# SPU_Rev_2_0.net
KiCad netlist of a schematic drawn in EAGLE
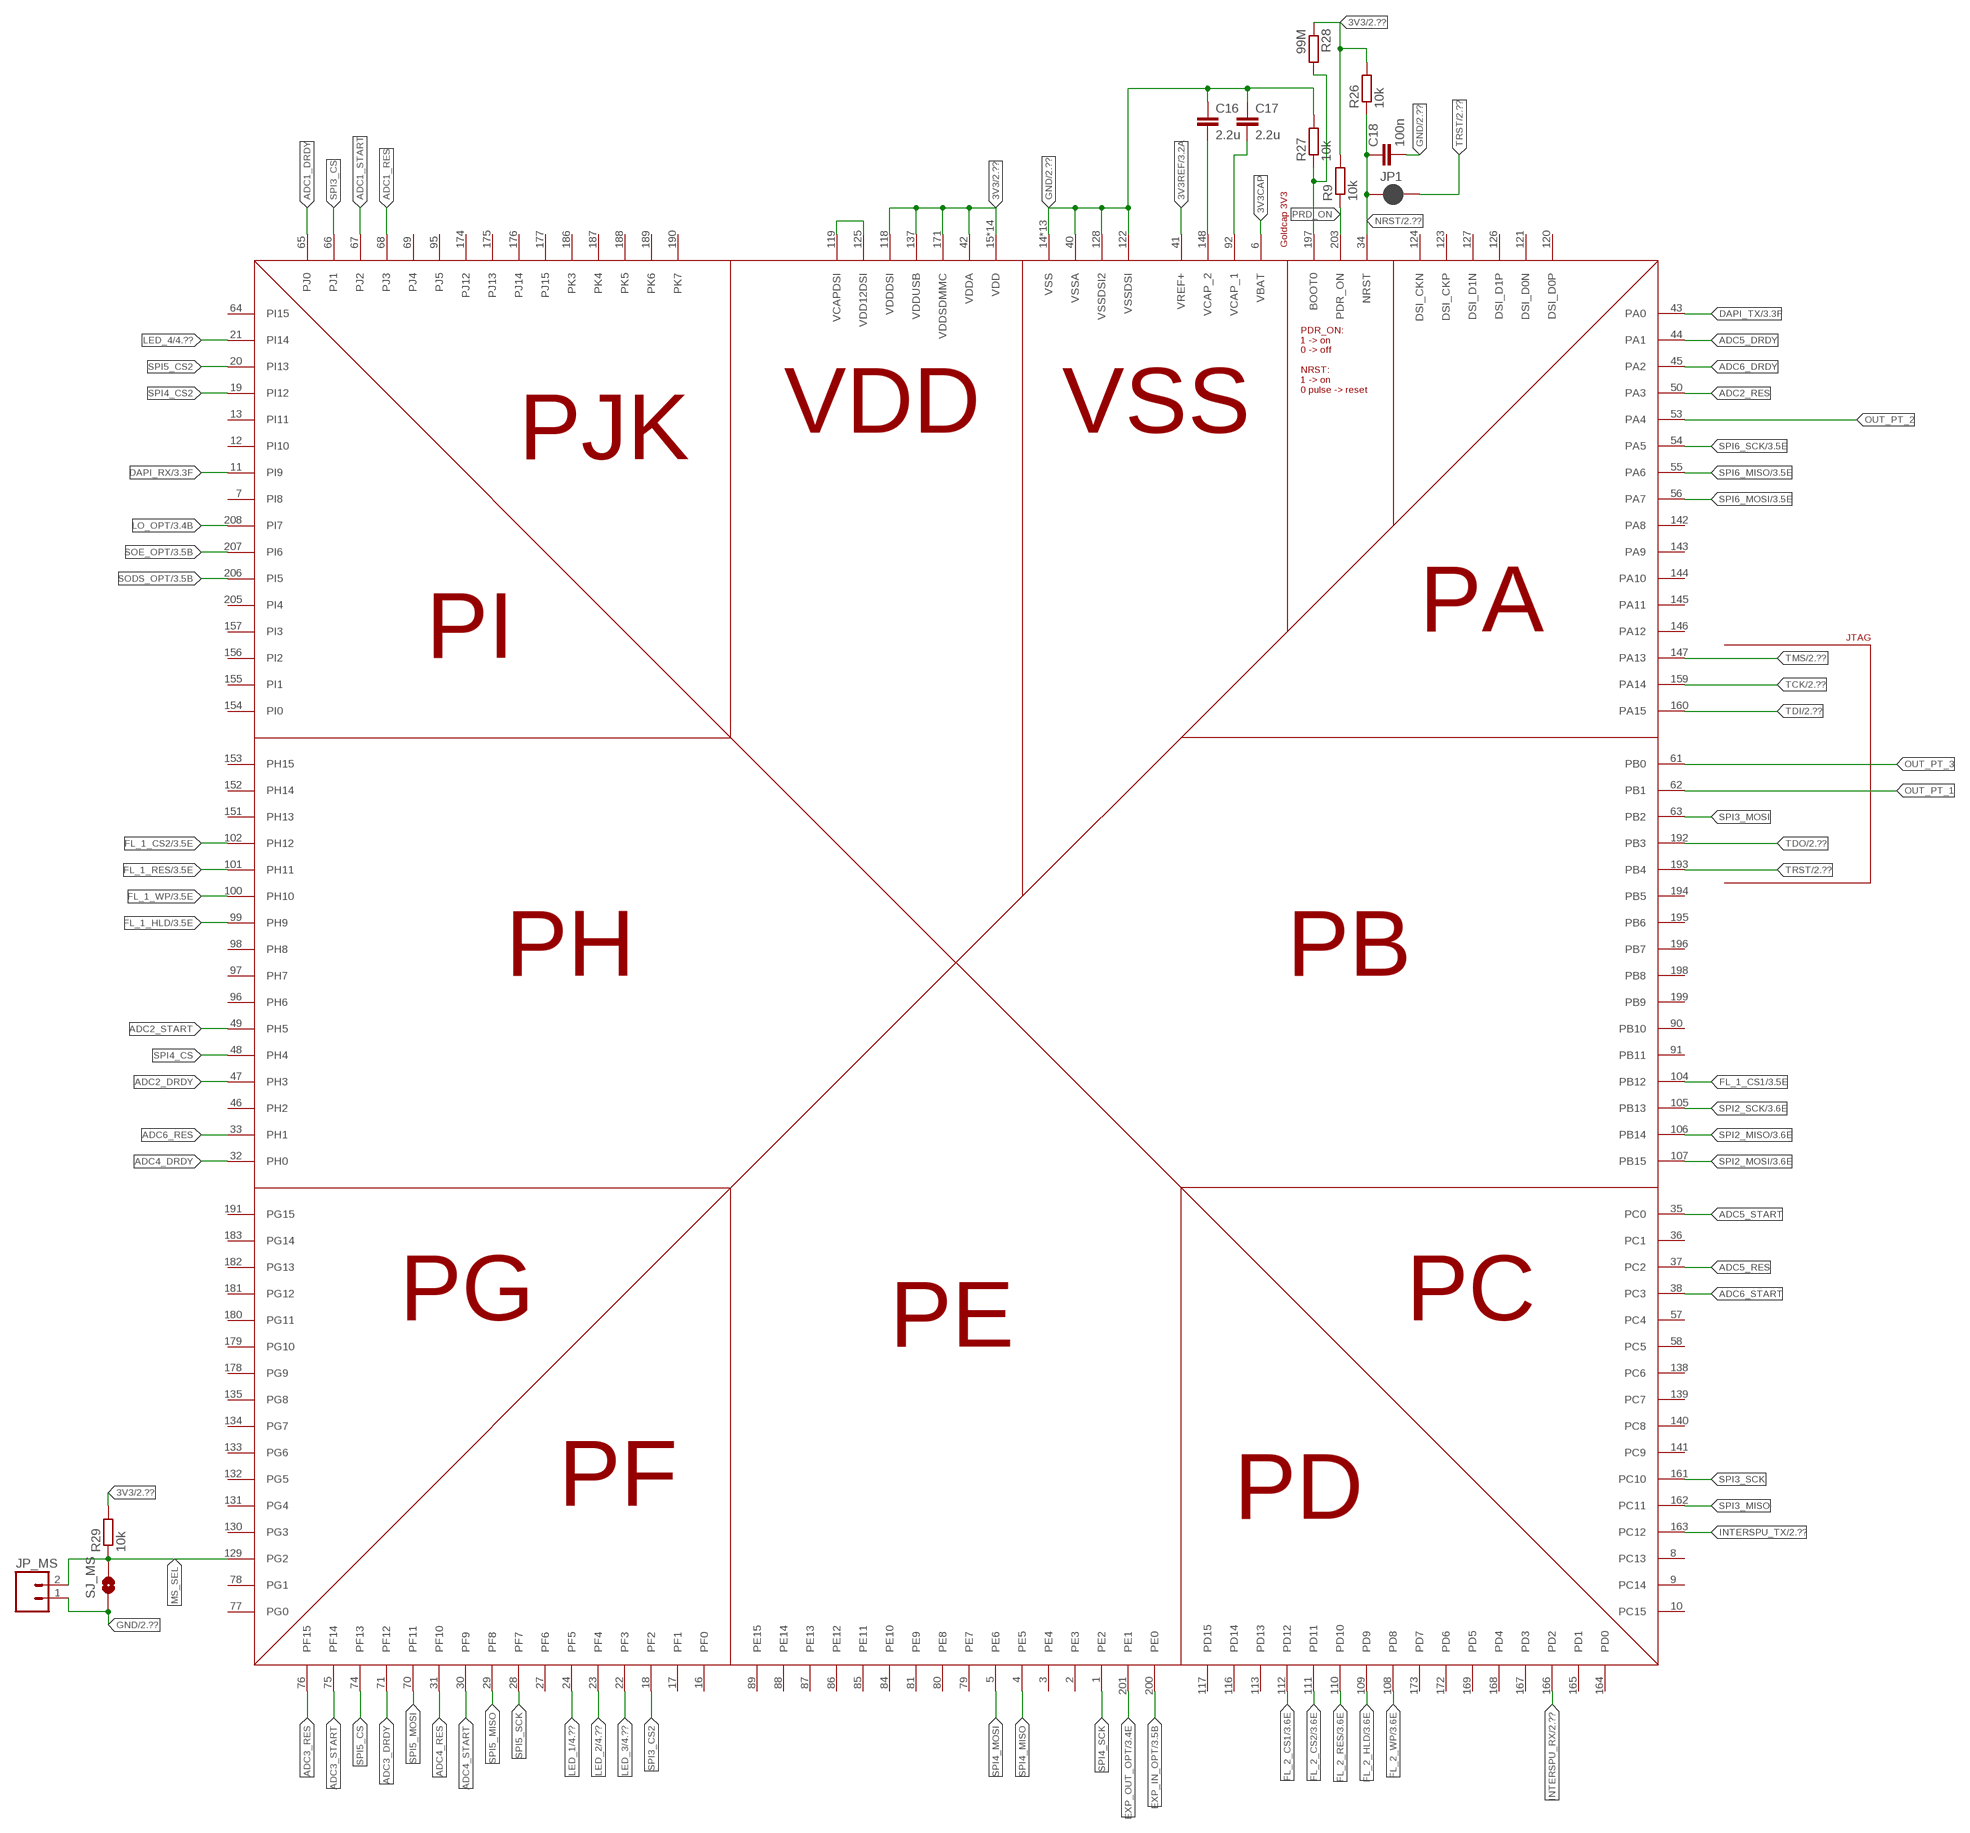
[diagram p0: schematic, sheet 1]
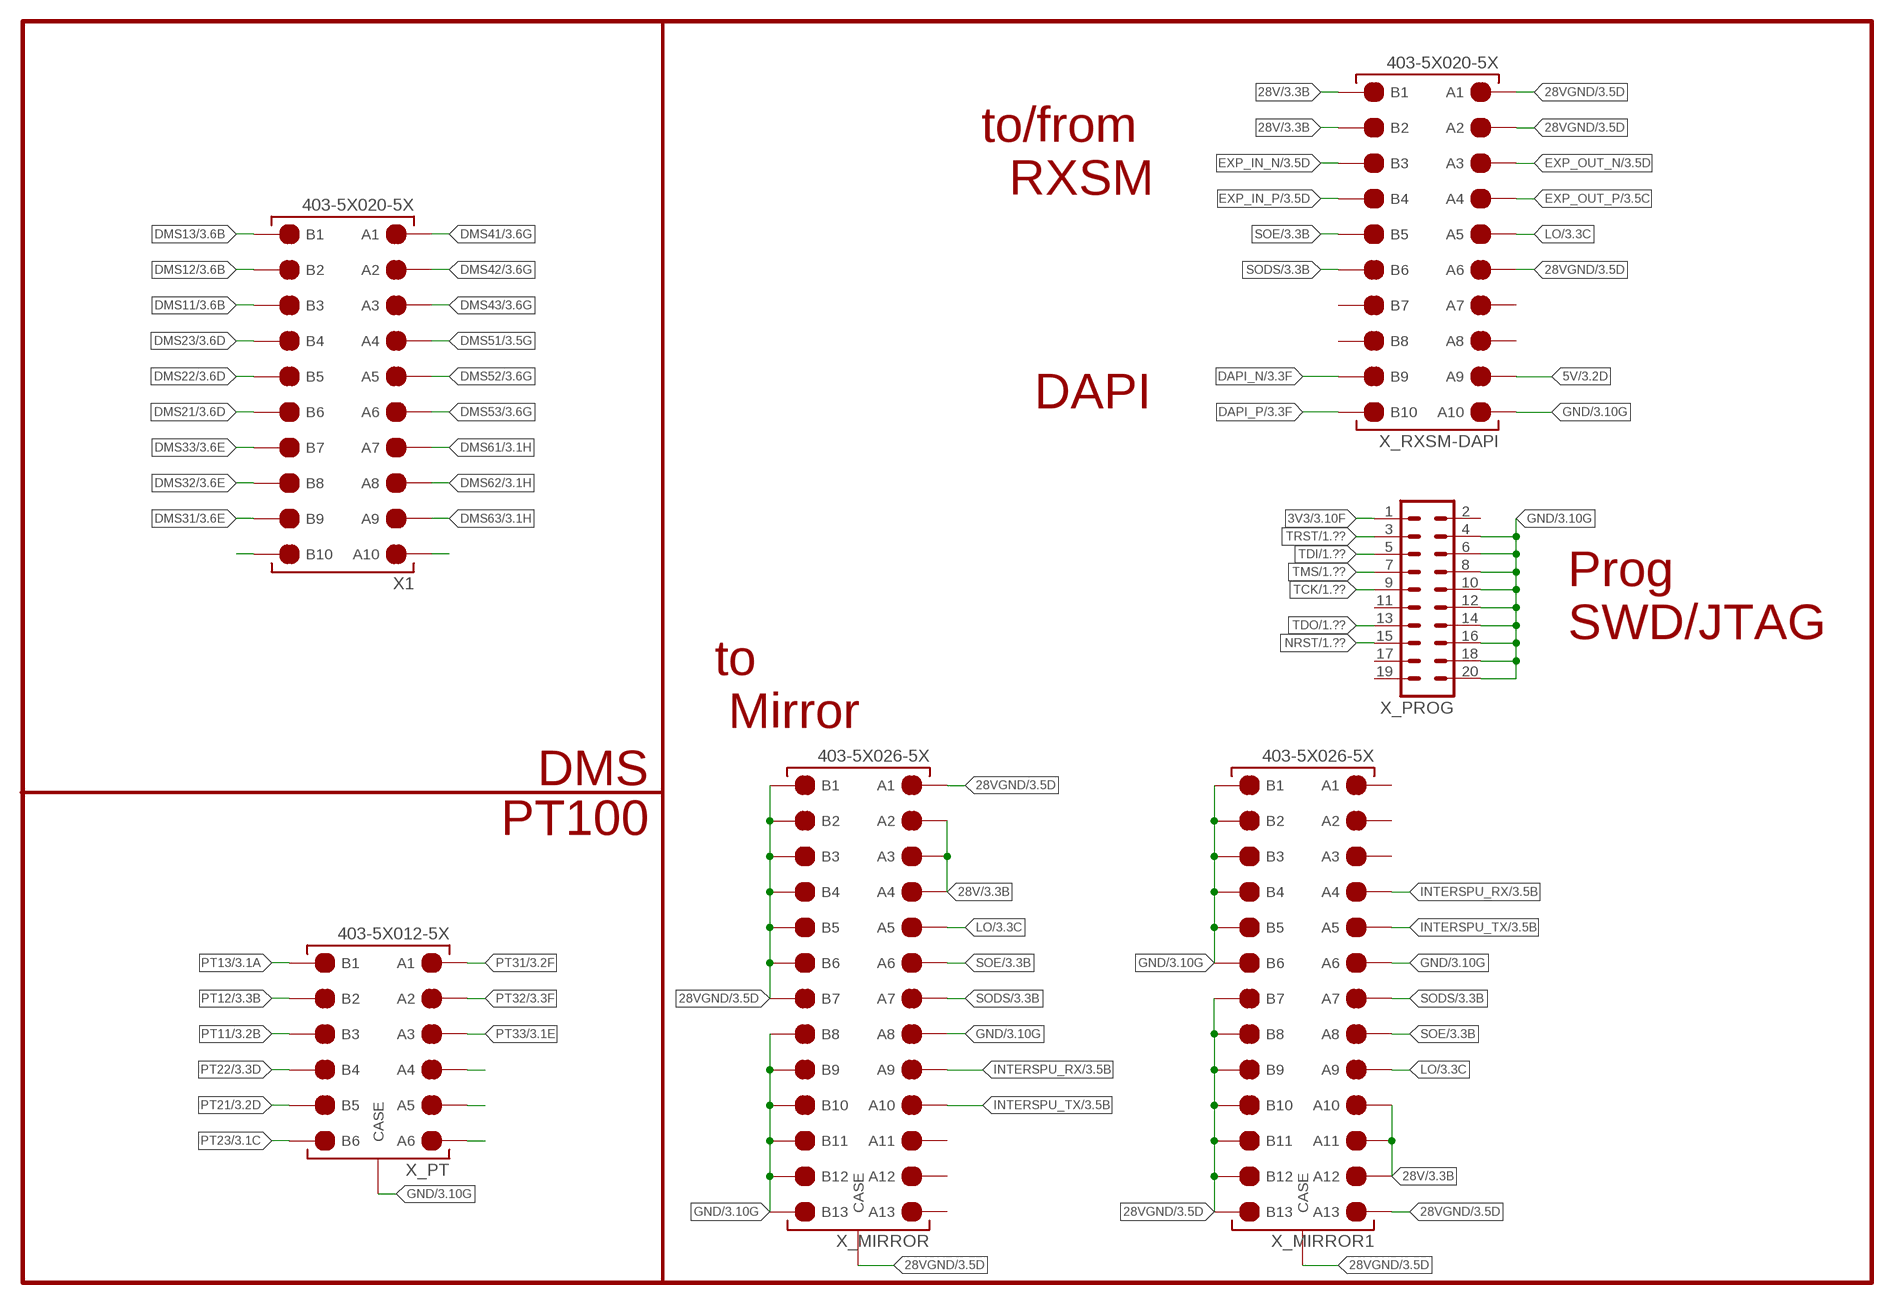
[diagram p1: schematic, sheet 2]
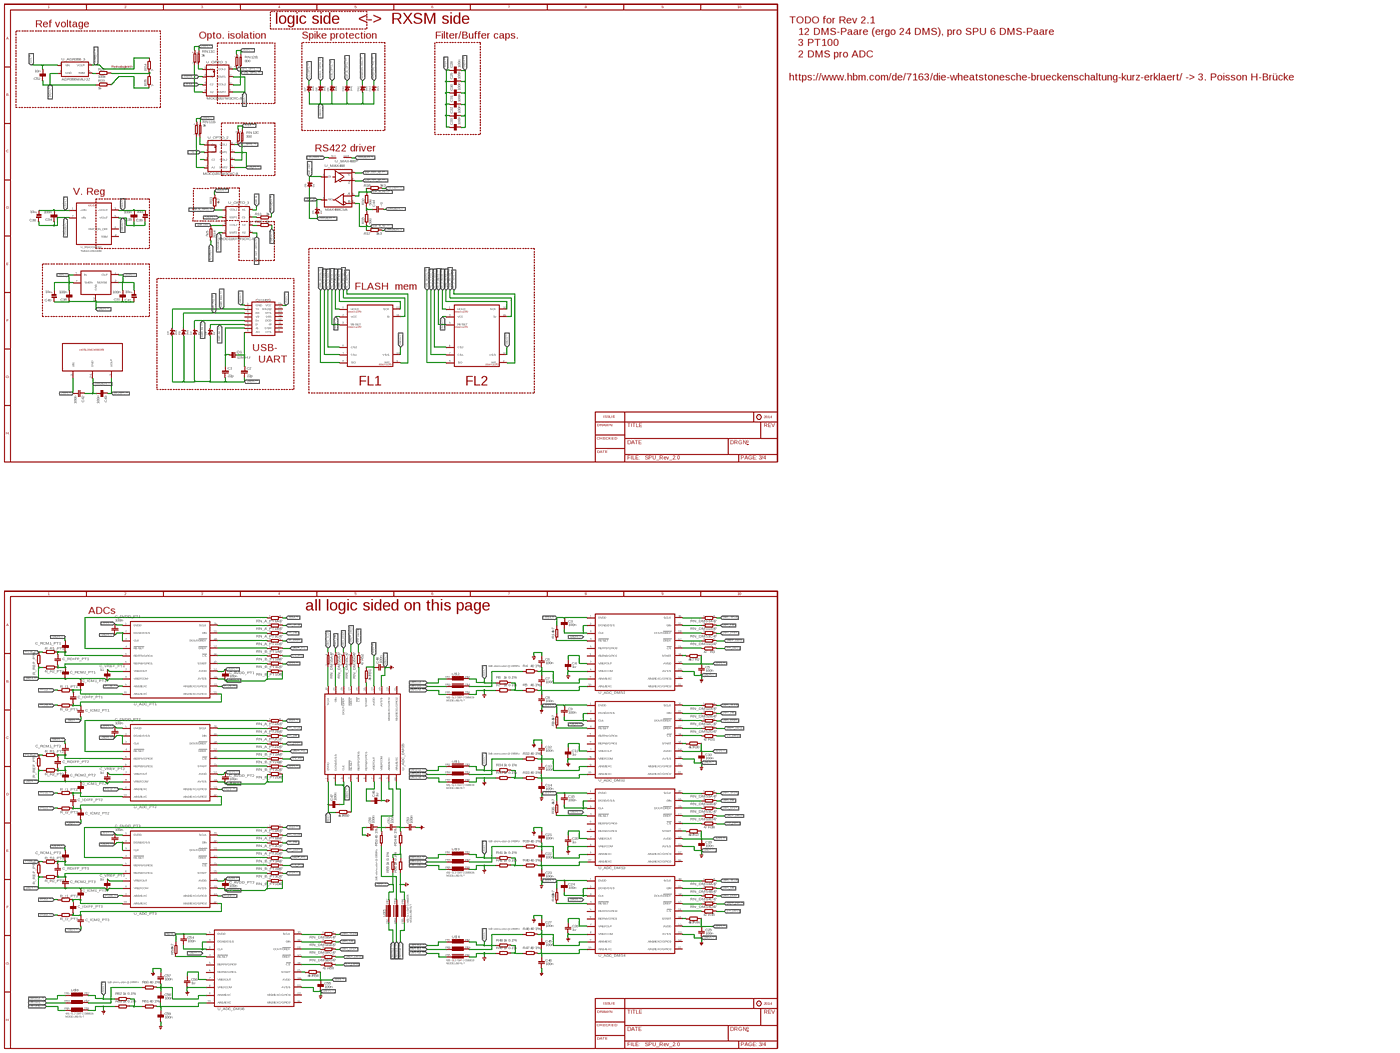
[diagram p2: schematic, sheet 3, overview]
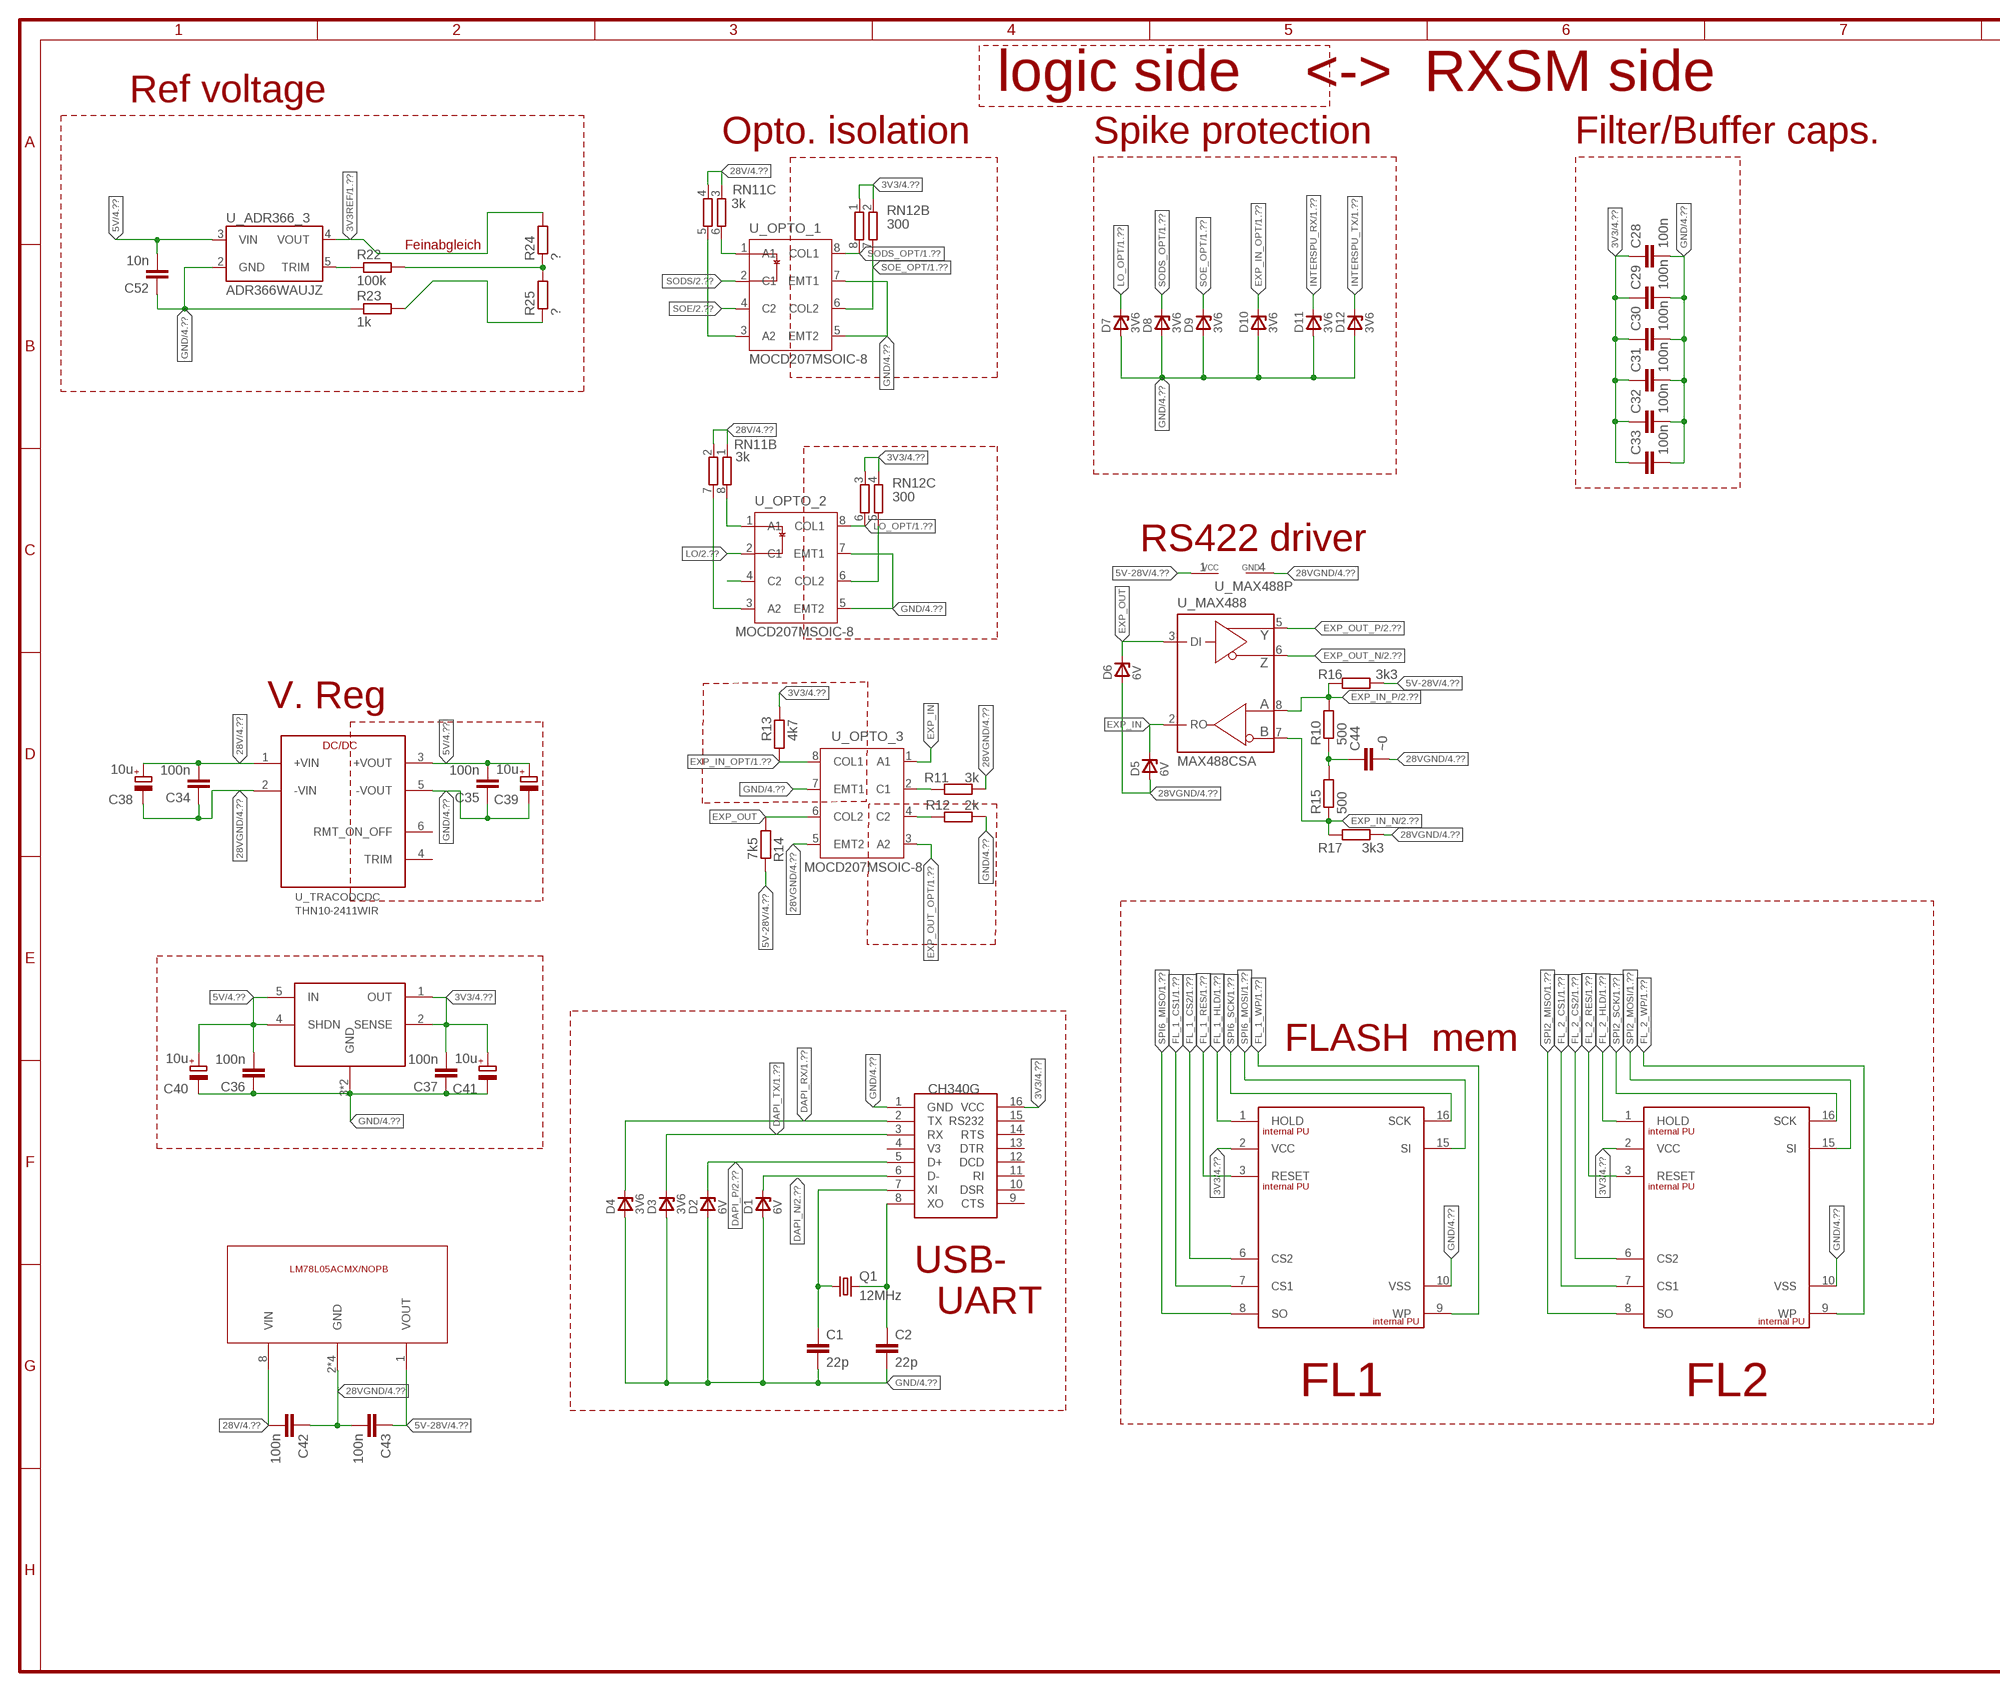
[diagram p3: schematic, sheet 3, part 1 of 5]
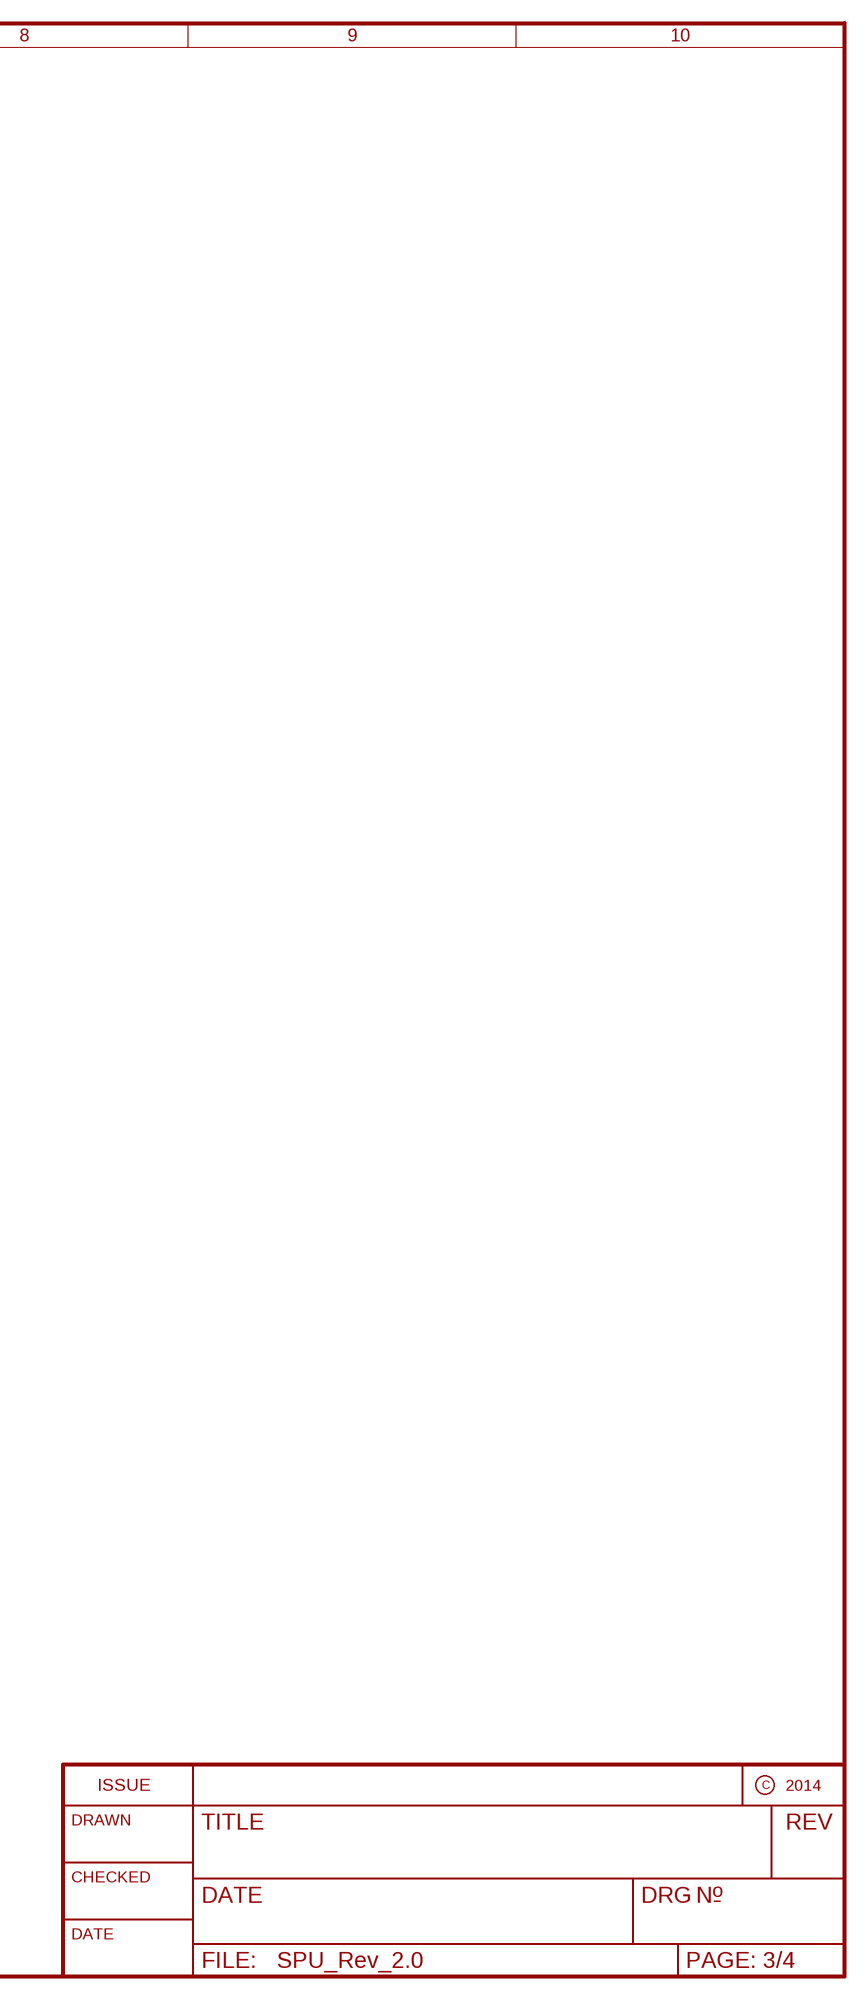
[diagram p4: schematic, sheet 3, part 2 of 5]
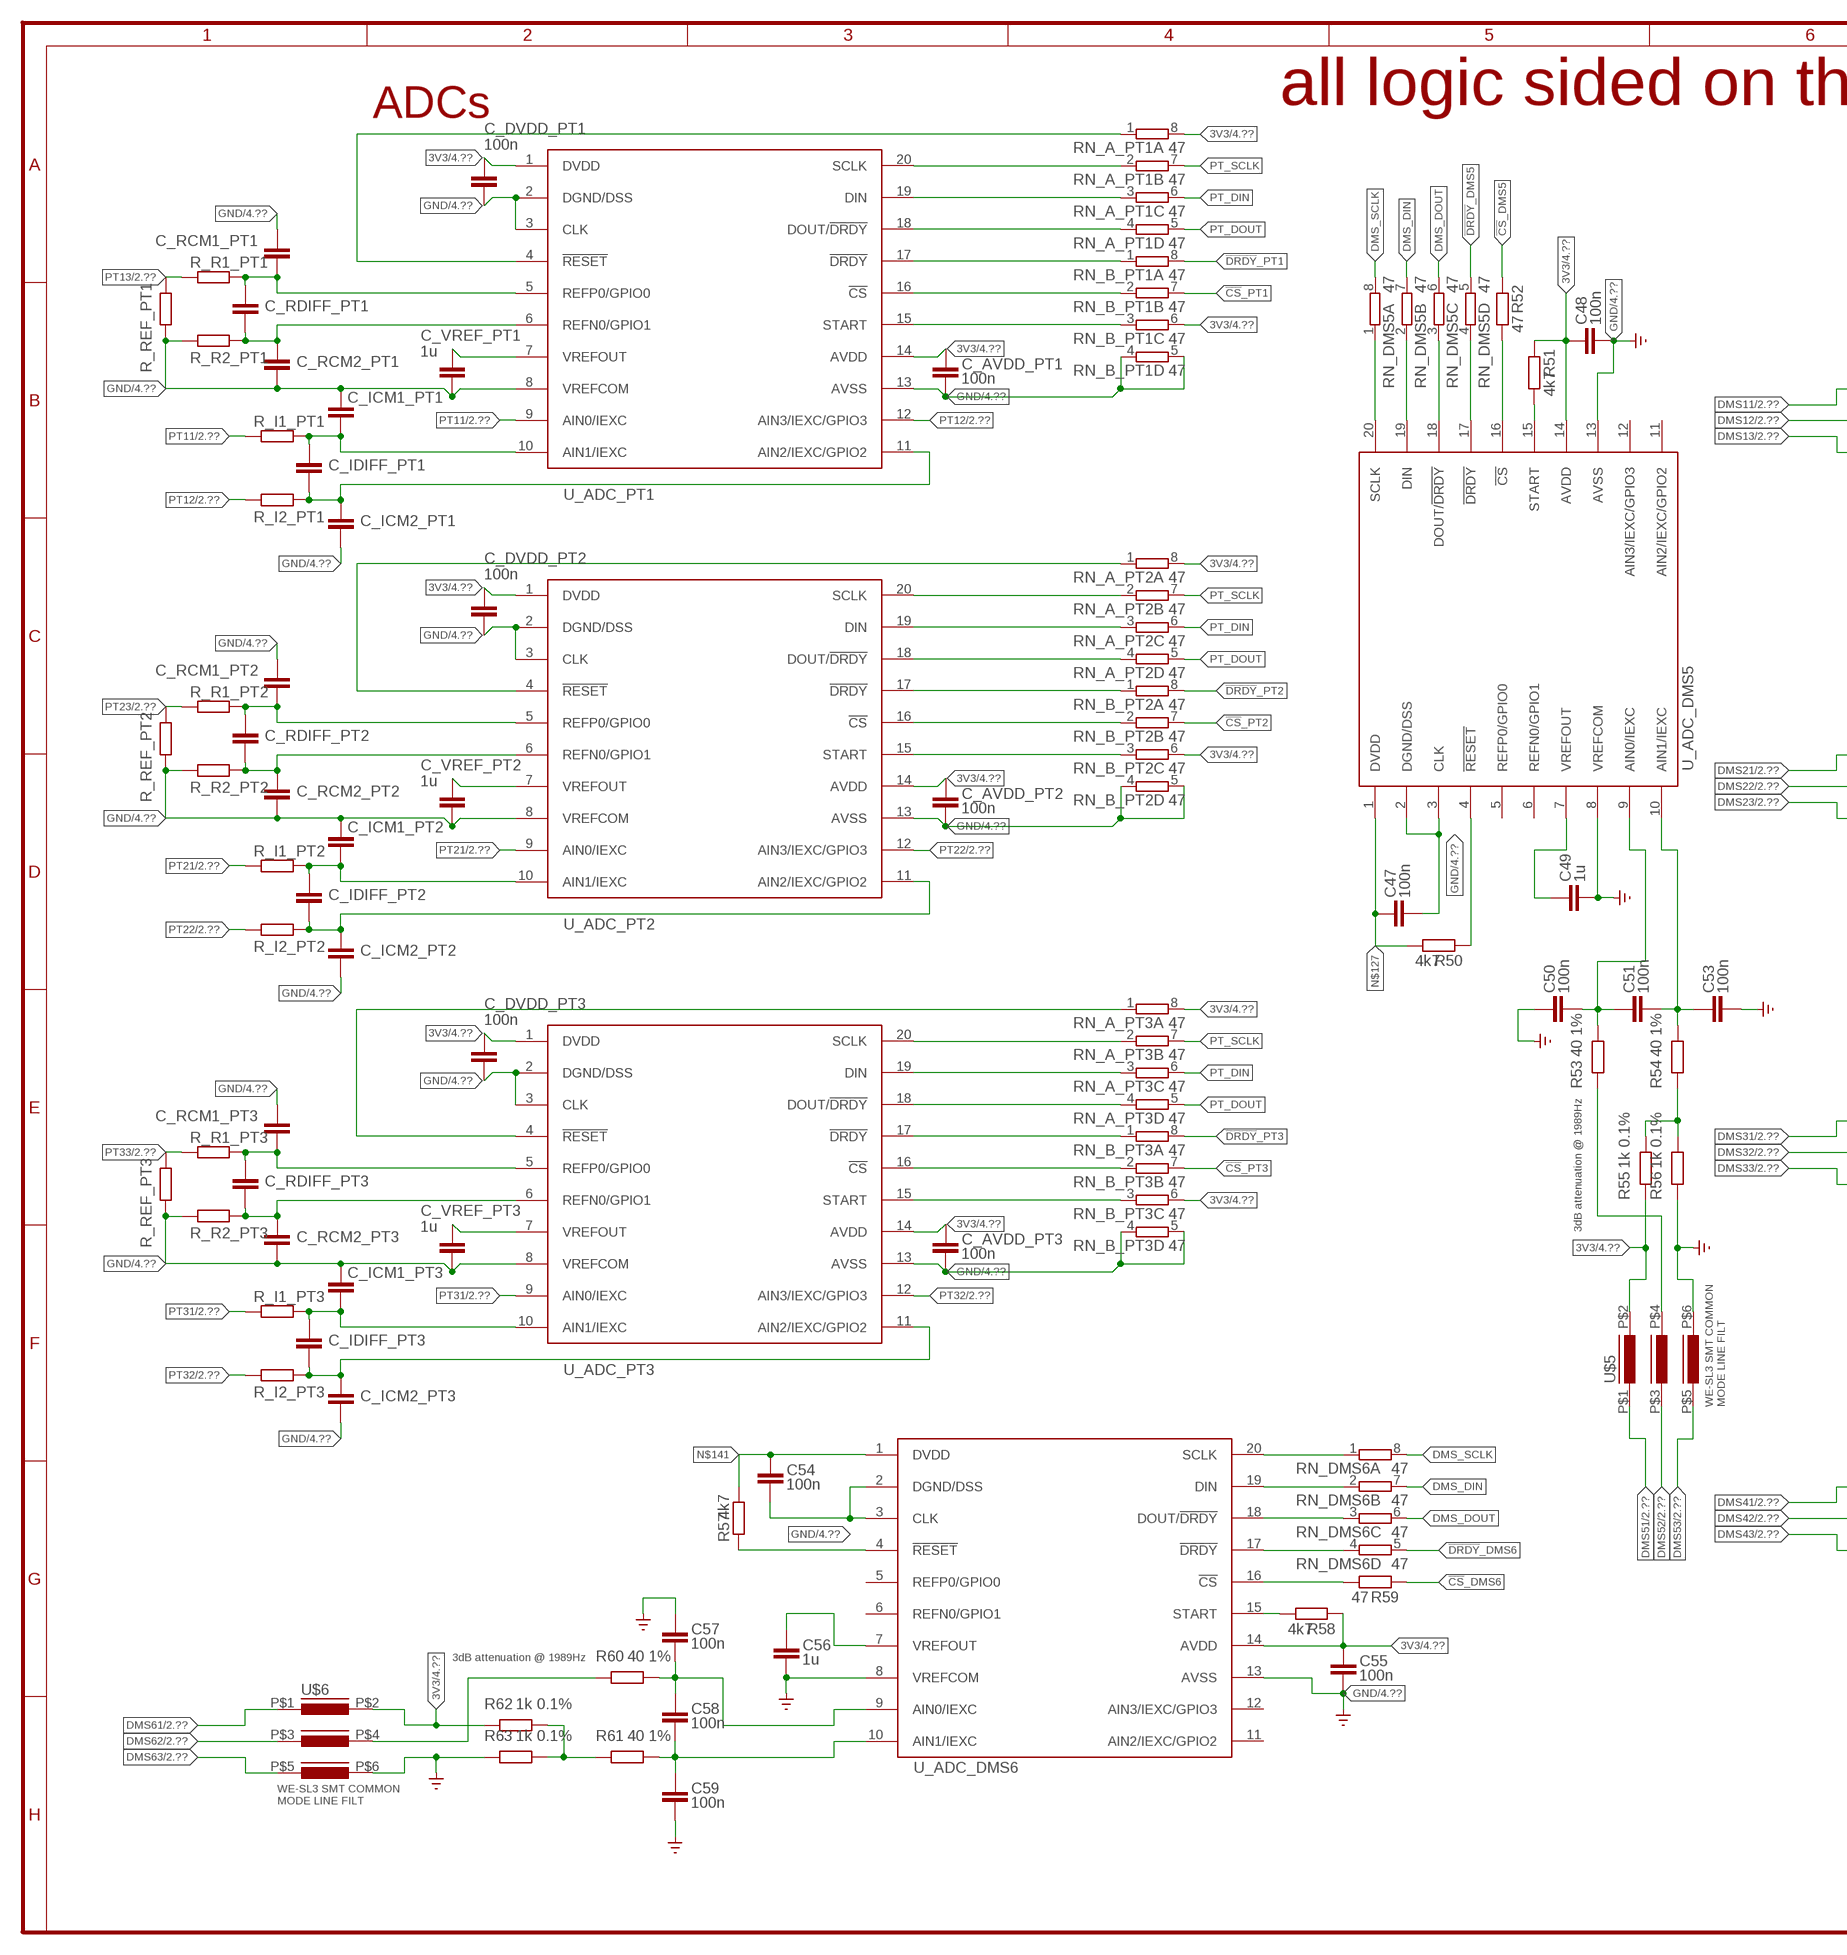
[diagram p5: schematic, sheet 3, part 3 of 5]
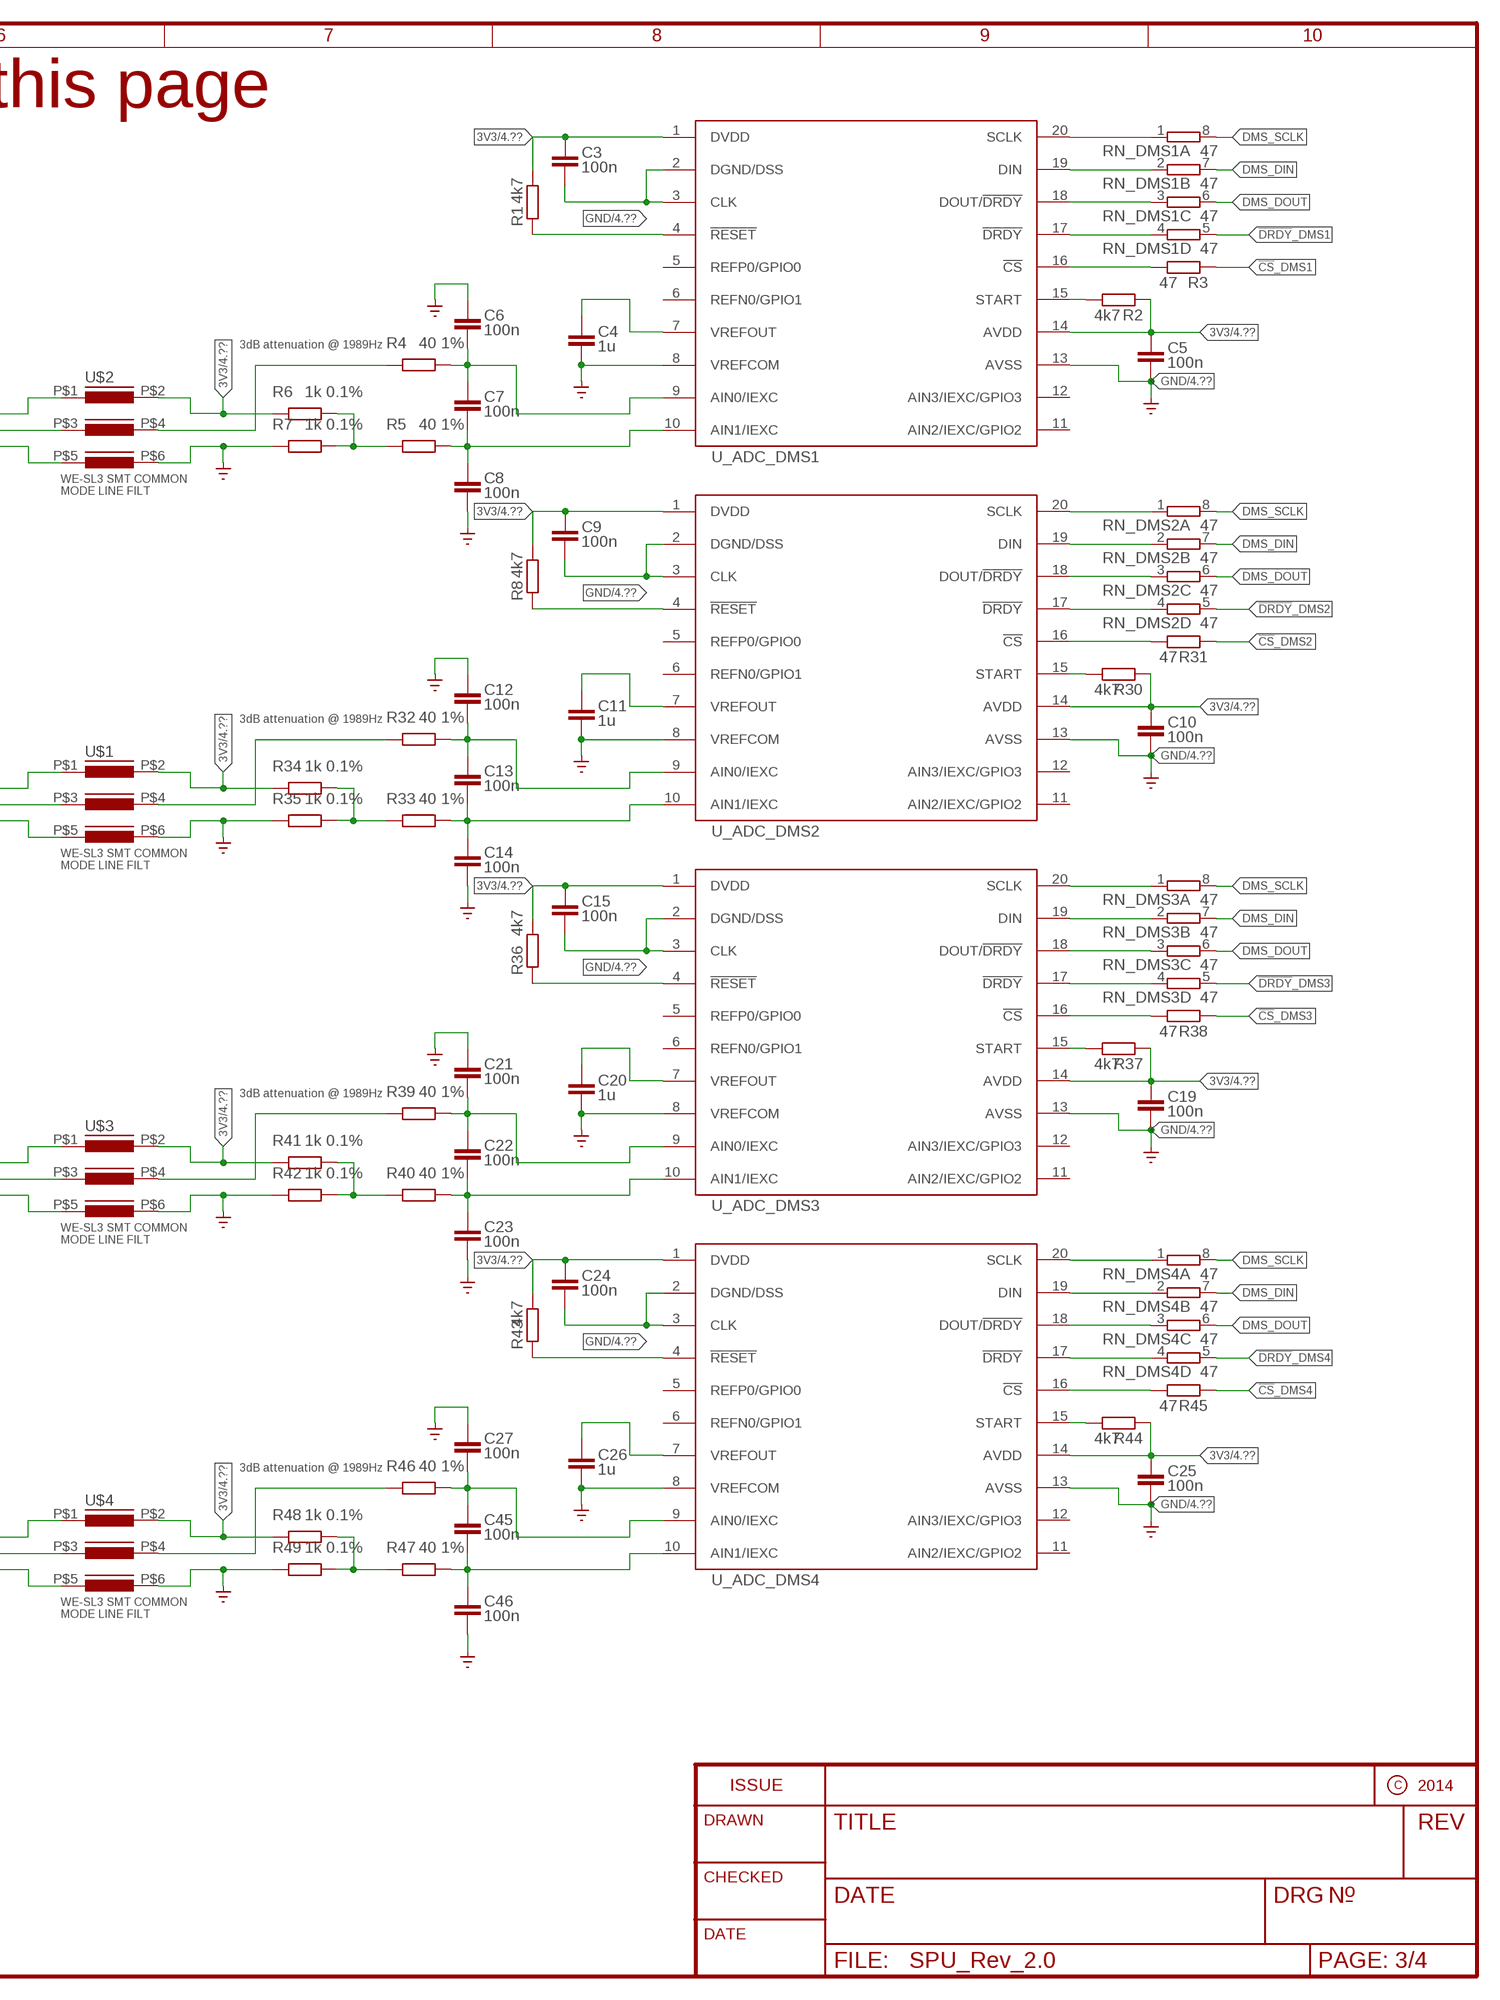
[diagram p6: schematic, sheet 3, part 4 of 5]
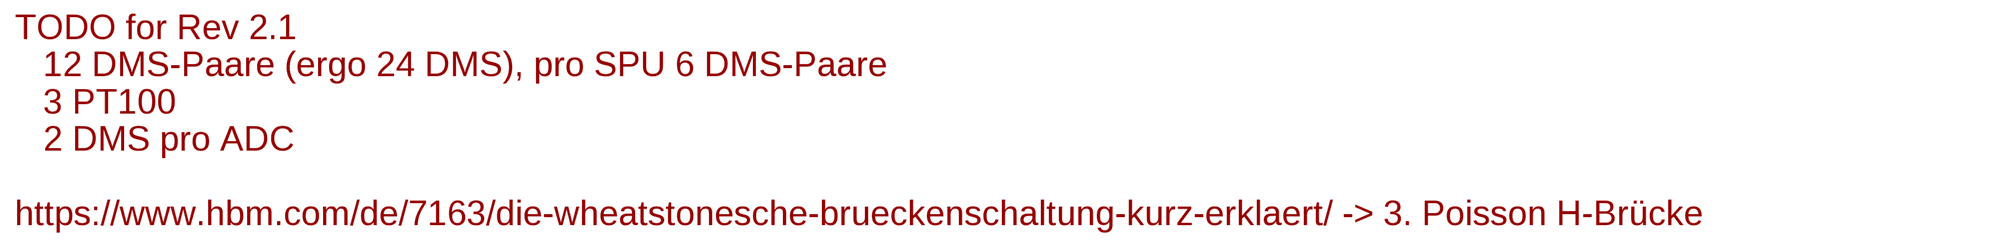
[diagram p7: schematic, sheet 3, part 5 of 5]
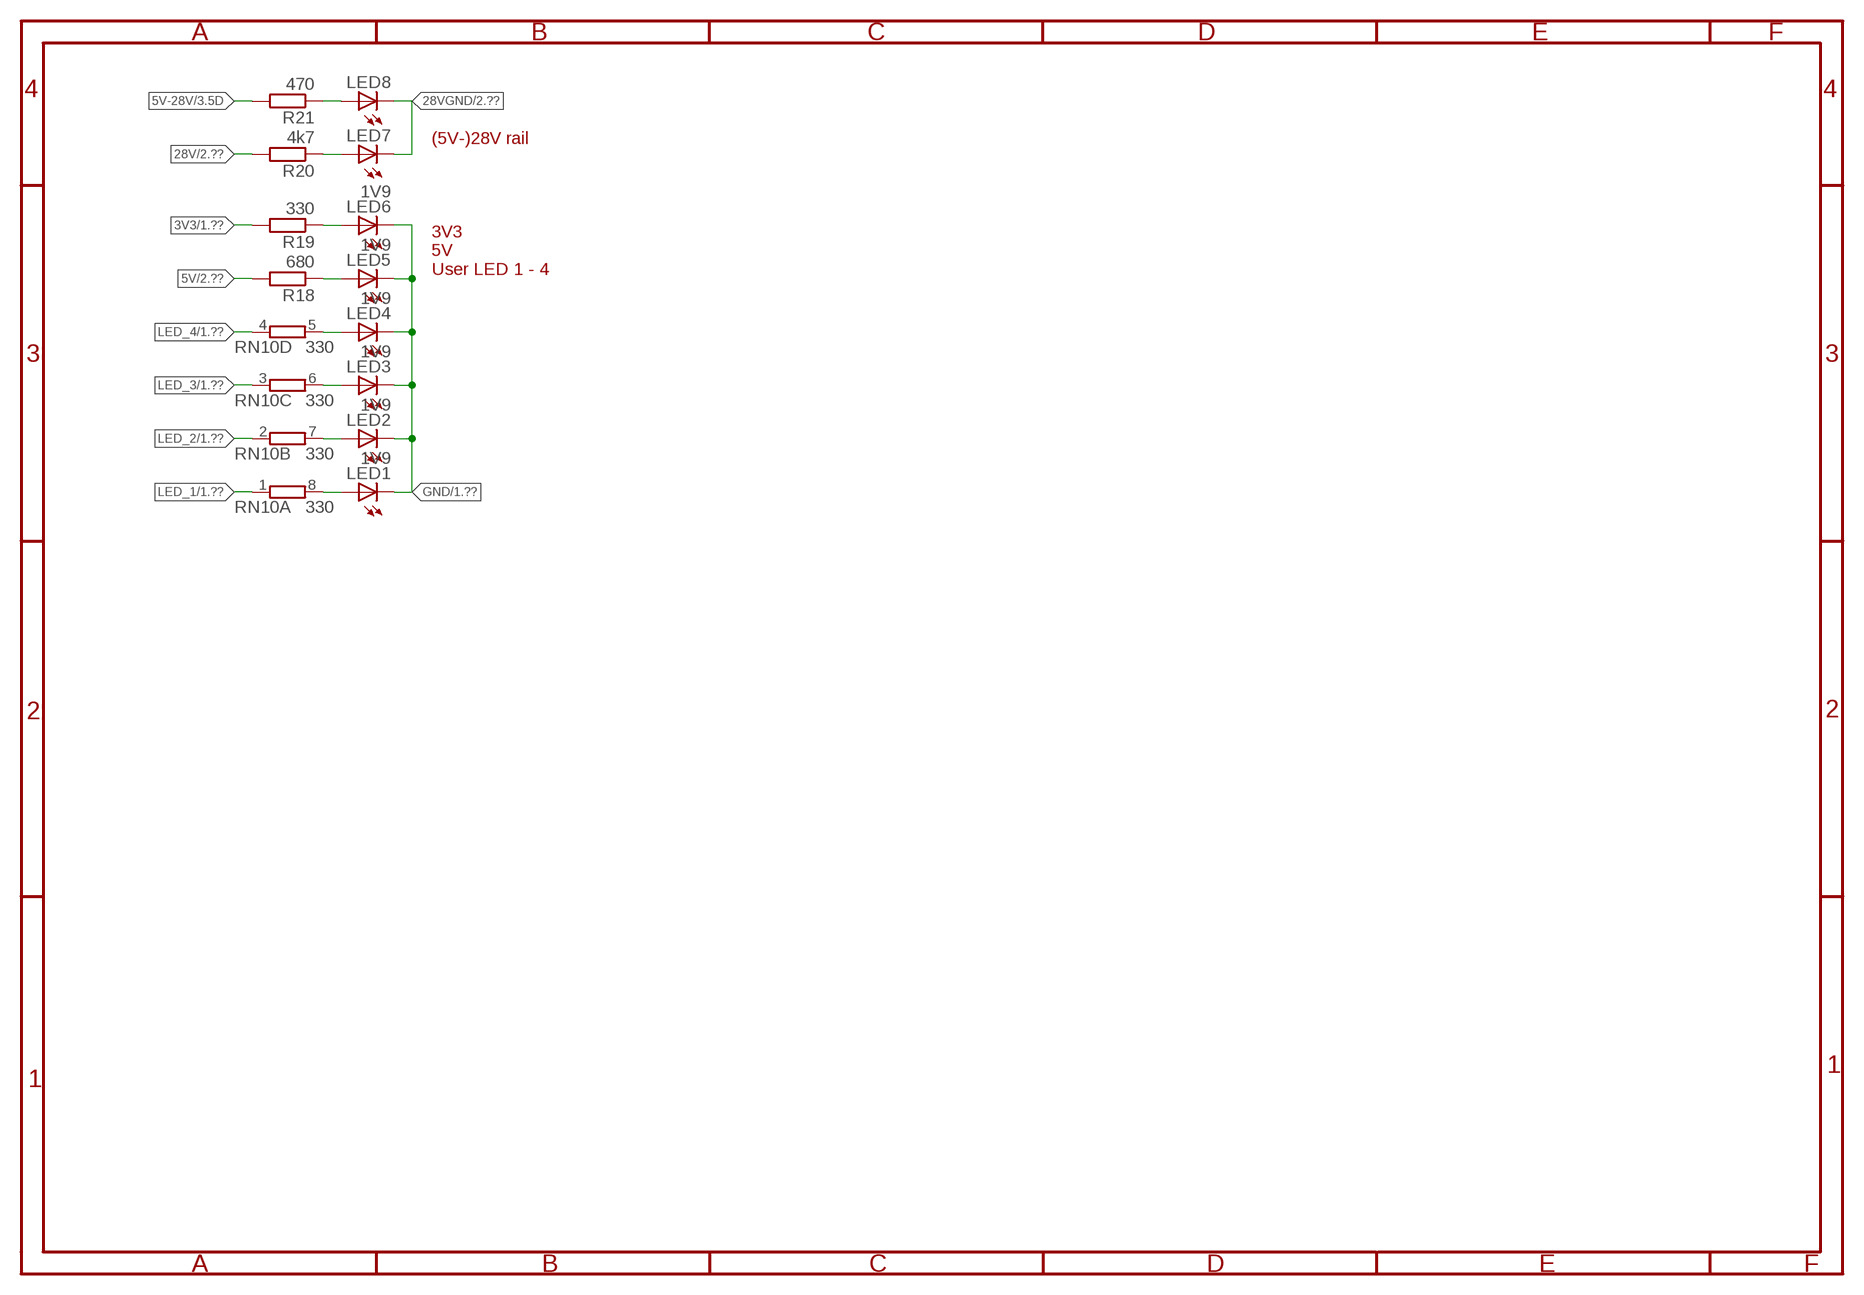
[diagram p8: schematic, sheet 4]

(export (version "E")
  (design (tool "Eeschema 10.0.6"))
  (components
    (comp (ref "X1")
      (value "403-5X020-5X")
      (footprint "eagle-import:403-5X020-5X")
      (libsource (lib "eagle-import") (part "403-5X020-5X"))
    )
    (comp (ref "X_MIRROR")
      (value "403-5X026-5X")
      (footprint "eagle-import:403-5X026-5X")
      (libsource (lib "eagle-import") (part "403-5X026-5X"))
    )
    (comp (ref "X_MIRROR1")
      (value "403-5X026-5X")
      (footprint "eagle-import:403-5X026-5X")
      (libsource (lib "eagle-import") (part "403-5X026-5X"))
    )
    (comp (ref "X_PROG")
      (value "MA10-2")
      (footprint "eagle-import:MA10-2")
      (libsource (lib "eagle-import") (part "MA10-2"))
    )
    (comp (ref "X_PT")
      (value "403-5X012-5X")
      (footprint "eagle-import:403-5X012-5X")
      (libsource (lib "eagle-import") (part "403-5X012-5X"))
    )
    (comp (ref "X_RXSM-DAPI")
      (value "403-5X020-5X")
      (footprint "eagle-import:403-5X020-5X")
      (libsource (lib "eagle-import") (part "403-5X020-5X"))
    )
    (comp (ref "C16")
      (value "2.2u")
      (footprint "eagle-import:C1206")
      (libsource (lib "eagle-import") (part "rcl_334_C-EUC1206"))
    )
    (comp (ref "C17")
      (value "2.2u")
      (footprint "eagle-import:C1206")
      (libsource (lib "eagle-import") (part "rcl_334_C-EUC1206"))
    )
    (comp (ref "C18")
      (value "100n")
      (footprint "eagle-import:0603-CAP")
      (libsource (lib "eagle-import") (part "CAP0603-CAP"))
    )
    (comp (ref "JP1")
      (value "JUMPER-SMT_2_NC_PASTE_SILK")
      (footprint "eagle-import:SMT-JUMPER_2_NC_PASTE_SILK")
      (libsource (lib "eagle-import") (part "JUMPER-SMT_2_NC_PASTE_SILK"))
    )
    (comp (ref "JP_MS")
      (value "M02PTH")
      (footprint "eagle-import:1X02")
      (libsource (lib "eagle-import") (part "M02PTH"))
    )
    (comp (ref "R9")
      (value "10k")
      (footprint "eagle-import:R0805")
      (libsource (lib "eagle-import") (part "rcl_334_R-EU_R0805"))
    )
    (comp (ref "R26")
      (value "10k")
      (footprint "eagle-import:R0805")
      (libsource (lib "eagle-import") (part "rcl_334_R-EU_R0805"))
    )
    (comp (ref "R27")
      (value "10k")
      (footprint "eagle-import:R0805")
      (libsource (lib "eagle-import") (part "rcl_334_R-EU_R0805"))
    )
    (comp (ref "R28")
      (value "99M")
      (footprint "eagle-import:R0805")
      (libsource (lib "eagle-import") (part "rcl_334_R-EU_R0805"))
    )
    (comp (ref "R29")
      (value "10k")
      (footprint "eagle-import:R0805")
      (libsource (lib "eagle-import") (part "rcl_334_R-EU_R0805"))
    )
    (comp (ref "SJ_MS")
      (value "SOLDERJUMPERNO")
      (footprint "eagle-import:SJ_2S-NO")
      (libsource (lib "eagle-import") (part "SOLDERJUMPERNO"))
    )
    (comp (ref "U_STM32F779")
      (value "STM32F77XXXLQFP208")
      (footprint "eagle-import:QFP50P3060X3060X385-208")
      (libsource (lib "eagle-import") (part "STM32F77XXXLQFP208"))
    )
    (comp (ref "LED1")
      (value "1V9")
      (footprint "eagle-import:CHIP-LED0805")
      (libsource (lib "eagle-import") (part "LEDCHIP-LED0805"))
    )
    (comp (ref "LED2")
      (value "1V9")
      (footprint "eagle-import:CHIP-LED0805")
      (libsource (lib "eagle-import") (part "LEDCHIP-LED0805"))
    )
    (comp (ref "LED3")
      (value "1V9")
      (footprint "eagle-import:CHIP-LED0805")
      (libsource (lib "eagle-import") (part "LEDCHIP-LED0805"))
    )
    (comp (ref "LED4")
      (value "1V9")
      (footprint "eagle-import:CHIP-LED0805")
      (libsource (lib "eagle-import") (part "LEDCHIP-LED0805"))
    )
    (comp (ref "LED5")
      (value "1V9")
      (footprint "eagle-import:CHIP-LED0805")
      (libsource (lib "eagle-import") (part "LEDCHIP-LED0805"))
    )
    (comp (ref "LED6")
      (value "1V9")
      (footprint "eagle-import:CHIP-LED0805")
      (libsource (lib "eagle-import") (part "LEDCHIP-LED0805"))
    )
    (comp (ref "LED7")
      (value "LEDCHIP-LED0805")
      (footprint "eagle-import:CHIP-LED0805")
      (libsource (lib "eagle-import") (part "LEDCHIP-LED0805"))
    )
    (comp (ref "LED8")
      (value "LEDCHIP-LED0805")
      (footprint "eagle-import:CHIP-LED0805")
      (libsource (lib "eagle-import") (part "LEDCHIP-LED0805"))
    )
    (comp (ref "R18")
      (value "680")
      (footprint "eagle-import:R0805")
      (libsource (lib "eagle-import") (part "rcl_334_R-EU_R0805"))
    )
    (comp (ref "R19")
      (value "330")
      (footprint "eagle-import:R0805")
      (libsource (lib "eagle-import") (part "rcl_334_R-EU_R0805"))
    )
    (comp (ref "R20")
      (value "4k7")
      (footprint "eagle-import:R0805")
      (libsource (lib "eagle-import") (part "rcl_334_R-EU_R0805"))
    )
    (comp (ref "R21")
      (value "470")
      (footprint "eagle-import:R0805")
      (libsource (lib "eagle-import") (part "rcl_334_R-EU_R0805"))
    )
    (comp (ref "RN10")
      (value "330")
      (footprint "eagle-import:EXBS8V")
      (libsource (lib "eagle-import") (part "4R-NEXBS8V"))
    )
    (comp (ref "C1")
      (value "22p")
      (footprint "eagle-import:C0603")
      (libsource (lib "eagle-import") (part "C-EUC0603"))
    )
    (comp (ref "C2")
      (value "22p")
      (footprint "eagle-import:C0603")
      (libsource (lib "eagle-import") (part "C-EUC0603"))
    )
    (comp (ref "C3")
      (value "100n")
      (footprint "eagle-import:C0603")
      (libsource (lib "eagle-import") (part "rcl_334_C-EUC0603"))
    )
    (comp (ref "C4")
      (value "1u")
      (footprint "eagle-import:C1206")
      (libsource (lib "eagle-import") (part "rcl_334_C-EUC1206"))
    )
    (comp (ref "C5")
      (value "100n")
      (footprint "eagle-import:C0603")
      (libsource (lib "eagle-import") (part "rcl_334_C-EUC0603"))
    )
    (comp (ref "C6")
      (value "100n")
      (footprint "eagle-import:C0603")
      (libsource (lib "eagle-import") (part "rcl_334_C-EUC0603"))
    )
    (comp (ref "C7")
      (value "100n")
      (footprint "eagle-import:C0603")
      (libsource (lib "eagle-import") (part "rcl_334_C-EUC0603"))
    )
    (comp (ref "C8")
      (value "100n")
      (footprint "eagle-import:C0603")
      (libsource (lib "eagle-import") (part "rcl_334_C-EUC0603"))
    )
    (comp (ref "C9")
      (value "100n")
      (footprint "eagle-import:C0603")
      (libsource (lib "eagle-import") (part "rcl_334_C-EUC0603"))
    )
    (comp (ref "C10")
      (value "100n")
      (footprint "eagle-import:C0603")
      (libsource (lib "eagle-import") (part "rcl_334_C-EUC0603"))
    )
    (comp (ref "C11")
      (value "1u")
      (footprint "eagle-import:C1206")
      (libsource (lib "eagle-import") (part "rcl_334_C-EUC1206"))
    )
    (comp (ref "C12")
      (value "100n")
      (footprint "eagle-import:C0603")
      (libsource (lib "eagle-import") (part "rcl_334_C-EUC0603"))
    )
    (comp (ref "C13")
      (value "100n")
      (footprint "eagle-import:C0603")
      (libsource (lib "eagle-import") (part "rcl_334_C-EUC0603"))
    )
    (comp (ref "C14")
      (value "100n")
      (footprint "eagle-import:C0603")
      (libsource (lib "eagle-import") (part "rcl_334_C-EUC0603"))
    )
    (comp (ref "C15")
      (value "100n")
      (footprint "eagle-import:C0603")
      (libsource (lib "eagle-import") (part "rcl_334_C-EUC0603"))
    )
    (comp (ref "C19")
      (value "100n")
      (footprint "eagle-import:C0603")
      (libsource (lib "eagle-import") (part "rcl_334_C-EUC0603"))
    )
    (comp (ref "C20")
      (value "1u")
      (footprint "eagle-import:C1206")
      (libsource (lib "eagle-import") (part "rcl_334_C-EUC1206"))
    )
    (comp (ref "C21")
      (value "100n")
      (footprint "eagle-import:C0603")
      (libsource (lib "eagle-import") (part "rcl_334_C-EUC0603"))
    )
    (comp (ref "C22")
      (value "100n")
      (footprint "eagle-import:C0603")
      (libsource (lib "eagle-import") (part "rcl_334_C-EUC0603"))
    )
    (comp (ref "C23")
      (value "100n")
      (footprint "eagle-import:C0603")
      (libsource (lib "eagle-import") (part "rcl_334_C-EUC0603"))
    )
    (comp (ref "C24")
      (value "100n")
      (footprint "eagle-import:C0603")
      (libsource (lib "eagle-import") (part "rcl_334_C-EUC0603"))
    )
    (comp (ref "C25")
      (value "100n")
      (footprint "eagle-import:C0603")
      (libsource (lib "eagle-import") (part "rcl_334_C-EUC0603"))
    )
    (comp (ref "C26")
      (value "1u")
      (footprint "eagle-import:C1206")
      (libsource (lib "eagle-import") (part "rcl_334_C-EUC1206"))
    )
    (comp (ref "C27")
      (value "100n")
      (footprint "eagle-import:C0603")
      (libsource (lib "eagle-import") (part "rcl_334_C-EUC0603"))
    )
    (comp (ref "C28")
      (value "100n")
      (footprint "eagle-import:C0805")
      (libsource (lib "eagle-import") (part "rcl_334_C-EUC0805"))
    )
    (comp (ref "C29")
      (value "100n")
      (footprint "eagle-import:C0805")
      (libsource (lib "eagle-import") (part "rcl_334_C-EUC0805"))
    )
    (comp (ref "C30")
      (value "100n")
      (footprint "eagle-import:C0805")
      (libsource (lib "eagle-import") (part "rcl_334_C-EUC0805"))
    )
    (comp (ref "C31")
      (value "100n")
      (footprint "eagle-import:C0805")
      (libsource (lib "eagle-import") (part "rcl_334_C-EUC0805"))
    )
    (comp (ref "C32")
      (value "100n")
      (footprint "eagle-import:C0805")
      (libsource (lib "eagle-import") (part "rcl_334_C-EUC0805"))
    )
    (comp (ref "C33")
      (value "100n")
      (footprint "eagle-import:C0805")
      (libsource (lib "eagle-import") (part "rcl_334_C-EUC0805"))
    )
    (comp (ref "C34")
      (value "100n")
      (footprint "eagle-import:C0805")
      (libsource (lib "eagle-import") (part "rcl_334_C-EUC0805"))
    )
    (comp (ref "C35")
      (value "100n")
      (footprint "eagle-import:C0805")
      (libsource (lib "eagle-import") (part "rcl_334_C-EUC0805"))
    )
    (comp (ref "C36")
      (value "100n")
      (footprint "eagle-import:C0805")
      (libsource (lib "eagle-import") (part "rcl_334_C-EUC0805"))
    )
    (comp (ref "C37")
      (value "100n")
      (footprint "eagle-import:C0805")
      (libsource (lib "eagle-import") (part "rcl_334_C-EUC0805"))
    )
    (comp (ref "C38")
      (value "10u")
      (footprint "eagle-import:E_7260-38W")
      (libsource (lib "eagle-import") (part "CPOL-EUE/7260-38W"))
    )
    (comp (ref "C39")
      (value "10u")
      (footprint "eagle-import:E_7260-38W")
      (libsource (lib "eagle-import") (part "CPOL-EUE/7260-38W"))
    )
    (comp (ref "C40")
      (value "10u")
      (footprint "eagle-import:E_7260-38W")
      (libsource (lib "eagle-import") (part "CPOL-EUE/7260-38W"))
    )
    (comp (ref "C41")
      (value "10u")
      (footprint "eagle-import:E_7260-38W")
      (libsource (lib "eagle-import") (part "CPOL-EUE/7260-38W"))
    )
    (comp (ref "C42")
      (value "100n")
      (footprint "eagle-import:C0805")
      (libsource (lib "eagle-import") (part "rcl_334_C-EUC0805"))
    )
    (comp (ref "C43")
      (value "100n")
      (footprint "eagle-import:C0805")
      (libsource (lib "eagle-import") (part "rcl_334_C-EUC0805"))
    )
    (comp (ref "C44")
      (value "~0")
      (footprint "eagle-import:C0805")
      (libsource (lib "eagle-import") (part "rcl_334_C-EUC0805"))
    )
    (comp (ref "C45")
      (value "100n")
      (footprint "eagle-import:C0603")
      (libsource (lib "eagle-import") (part "rcl_334_C-EUC0603"))
    )
    (comp (ref "C46")
      (value "100n")
      (footprint "eagle-import:C0603")
      (libsource (lib "eagle-import") (part "rcl_334_C-EUC0603"))
    )
    (comp (ref "C47")
      (value "100n")
      (footprint "eagle-import:C0603")
      (libsource (lib "eagle-import") (part "rcl_334_C-EUC0603"))
    )
    (comp (ref "C48")
      (value "100n")
      (footprint "eagle-import:C0603")
      (libsource (lib "eagle-import") (part "rcl_334_C-EUC0603"))
    )
    (comp (ref "C49")
      (value "1u")
      (footprint "eagle-import:C1206")
      (libsource (lib "eagle-import") (part "rcl_334_C-EUC1206"))
    )
    (comp (ref "C50")
      (value "100n")
      (footprint "eagle-import:C0603")
      (libsource (lib "eagle-import") (part "rcl_334_C-EUC0603"))
    )
    (comp (ref "C51")
      (value "100n")
      (footprint "eagle-import:C0603")
      (libsource (lib "eagle-import") (part "rcl_334_C-EUC0603"))
    )
    (comp (ref "C52")
      (value "10n")
      (footprint "eagle-import:C0805")
      (libsource (lib "eagle-import") (part "rcl_334_C-EUC0805"))
    )
    (comp (ref "C53")
      (value "100n")
      (footprint "eagle-import:C0603")
      (libsource (lib "eagle-import") (part "rcl_334_C-EUC0603"))
    )
    (comp (ref "C54")
      (value "100n")
      (footprint "eagle-import:C0603")
      (libsource (lib "eagle-import") (part "rcl_334_C-EUC0603"))
    )
    (comp (ref "C55")
      (value "100n")
      (footprint "eagle-import:C0603")
      (libsource (lib "eagle-import") (part "rcl_334_C-EUC0603"))
    )
    (comp (ref "C56")
      (value "1u")
      (footprint "eagle-import:C1206")
      (libsource (lib "eagle-import") (part "rcl_334_C-EUC1206"))
    )
    (comp (ref "C57")
      (value "100n")
      (footprint "eagle-import:C0603")
      (libsource (lib "eagle-import") (part "rcl_334_C-EUC0603"))
    )
    (comp (ref "C58")
      (value "100n")
      (footprint "eagle-import:C0603")
      (libsource (lib "eagle-import") (part "rcl_334_C-EUC0603"))
    )
    (comp (ref "C59")
      (value "100n")
      (footprint "eagle-import:C0603")
      (libsource (lib "eagle-import") (part "rcl_334_C-EUC0603"))
    )
    (comp (ref "C_AVDD_PT1")
      (value "100n")
      (footprint "eagle-import:C0603")
      (libsource (lib "eagle-import") (part "rcl_334_C-EUC0603"))
    )
    (comp (ref "C_AVDD_PT2")
      (value "100n")
      (footprint "eagle-import:C0603")
      (libsource (lib "eagle-import") (part "rcl_334_C-EUC0603"))
    )
    (comp (ref "C_AVDD_PT3")
      (value "100n")
      (footprint "eagle-import:C0603")
      (libsource (lib "eagle-import") (part "rcl_334_C-EUC0603"))
    )
    (comp (ref "C_DVDD_PT1")
      (value "100n")
      (footprint "eagle-import:C0603")
      (libsource (lib "eagle-import") (part "rcl_334_C-EUC0603"))
    )
    (comp (ref "C_DVDD_PT2")
      (value "100n")
      (footprint "eagle-import:C0603")
      (libsource (lib "eagle-import") (part "rcl_334_C-EUC0603"))
    )
    (comp (ref "C_DVDD_PT3")
      (value "100n")
      (footprint "eagle-import:C0603")
      (libsource (lib "eagle-import") (part "rcl_334_C-EUC0603"))
    )
    (comp (ref "C_ICM1_PT1")
      (value "C-EUC0603")
      (footprint "eagle-import:C0603")
      (libsource (lib "eagle-import") (part "rcl_334_C-EUC0603"))
    )
    (comp (ref "C_ICM1_PT2")
      (value "C-EUC0603")
      (footprint "eagle-import:C0603")
      (libsource (lib "eagle-import") (part "rcl_334_C-EUC0603"))
    )
    (comp (ref "C_ICM1_PT3")
      (value "C-EUC0603")
      (footprint "eagle-import:C0603")
      (libsource (lib "eagle-import") (part "rcl_334_C-EUC0603"))
    )
    (comp (ref "C_ICM2_PT1")
      (value "C-EUC0603")
      (footprint "eagle-import:C0603")
      (libsource (lib "eagle-import") (part "rcl_334_C-EUC0603"))
    )
    (comp (ref "C_ICM2_PT2")
      (value "C-EUC0603")
      (footprint "eagle-import:C0603")
      (libsource (lib "eagle-import") (part "rcl_334_C-EUC0603"))
    )
    (comp (ref "C_ICM2_PT3")
      (value "C-EUC0603")
      (footprint "eagle-import:C0603")
      (libsource (lib "eagle-import") (part "rcl_334_C-EUC0603"))
    )
    (comp (ref "C_IDIFF_PT1")
      (value "C-EUC0603")
      (footprint "eagle-import:C0603")
      (libsource (lib "eagle-import") (part "rcl_334_C-EUC0603"))
    )
    (comp (ref "C_IDIFF_PT2")
      (value "C-EUC0603")
      (footprint "eagle-import:C0603")
      (libsource (lib "eagle-import") (part "rcl_334_C-EUC0603"))
    )
    (comp (ref "C_IDIFF_PT3")
      (value "C-EUC0603")
      (footprint "eagle-import:C0603")
      (libsource (lib "eagle-import") (part "rcl_334_C-EUC0603"))
    )
    (comp (ref "C_RCM1_PT1")
      (value "C-EUC0603")
      (footprint "eagle-import:C0603")
      (libsource (lib "eagle-import") (part "rcl_334_C-EUC0603"))
    )
    (comp (ref "C_RCM1_PT2")
      (value "C-EUC0603")
      (footprint "eagle-import:C0603")
      (libsource (lib "eagle-import") (part "rcl_334_C-EUC0603"))
    )
    (comp (ref "C_RCM1_PT3")
      (value "C-EUC0603")
      (footprint "eagle-import:C0603")
      (libsource (lib "eagle-import") (part "rcl_334_C-EUC0603"))
    )
    (comp (ref "C_RCM2_PT1")
      (value "C-EUC0603")
      (footprint "eagle-import:C0603")
      (libsource (lib "eagle-import") (part "rcl_334_C-EUC0603"))
    )
    (comp (ref "C_RCM2_PT2")
      (value "C-EUC0603")
      (footprint "eagle-import:C0603")
      (libsource (lib "eagle-import") (part "rcl_334_C-EUC0603"))
    )
    (comp (ref "C_RCM2_PT3")
      (value "C-EUC0603")
      (footprint "eagle-import:C0603")
      (libsource (lib "eagle-import") (part "rcl_334_C-EUC0603"))
    )
    (comp (ref "C_RDIFF_PT1")
      (value "C-EUC0603")
      (footprint "eagle-import:C0603")
      (libsource (lib "eagle-import") (part "rcl_334_C-EUC0603"))
    )
    (comp (ref "C_RDIFF_PT2")
      (value "C-EUC0603")
      (footprint "eagle-import:C0603")
      (libsource (lib "eagle-import") (part "rcl_334_C-EUC0603"))
    )
    (comp (ref "C_RDIFF_PT3")
      (value "C-EUC0603")
      (footprint "eagle-import:C0603")
      (libsource (lib "eagle-import") (part "rcl_334_C-EUC0603"))
    )
    (comp (ref "C_VREF_PT1")
      (value "1u")
      (footprint "eagle-import:C0603")
      (libsource (lib "eagle-import") (part "rcl_334_C-EUC0603"))
    )
    (comp (ref "C_VREF_PT2")
      (value "1u")
      (footprint "eagle-import:C0603")
      (libsource (lib "eagle-import") (part "rcl_334_C-EUC0603"))
    )
    (comp (ref "C_VREF_PT3")
      (value "1u")
      (footprint "eagle-import:C0603")
      (libsource (lib "eagle-import") (part "rcl_334_C-EUC0603"))
    )
    (comp (ref "D1")
      (value "6V")
      (footprint "eagle-import:DMELF")
      (libsource (lib "eagle-import") (part "DZMELF"))
    )
    (comp (ref "D2")
      (value "6V")
      (footprint "eagle-import:DMELF")
      (libsource (lib "eagle-import") (part "DZMELF"))
    )
    (comp (ref "D3")
      (value "3V6")
      (footprint "eagle-import:DMELF")
      (libsource (lib "eagle-import") (part "DZMELF"))
    )
    (comp (ref "D4")
      (value "3V6")
      (footprint "eagle-import:DMELF")
      (libsource (lib "eagle-import") (part "DZMELF"))
    )
    (comp (ref "D5")
      (value "6V")
      (footprint "eagle-import:DMELF")
      (libsource (lib "eagle-import") (part "DZMELF"))
    )
    (comp (ref "D6")
      (value "6V")
      (footprint "eagle-import:DMELF")
      (libsource (lib "eagle-import") (part "DZMELF"))
    )
    (comp (ref "D7")
      (value "3V6")
      (footprint "eagle-import:DMELF")
      (libsource (lib "eagle-import") (part "DZMELF"))
    )
    (comp (ref "D8")
      (value "3V6")
      (footprint "eagle-import:DMELF")
      (libsource (lib "eagle-import") (part "DZMELF"))
    )
    (comp (ref "D9")
      (value "3V6")
      (footprint "eagle-import:DMELF")
      (libsource (lib "eagle-import") (part "DZMELF"))
    )
    (comp (ref "D10")
      (value "3V6")
      (footprint "eagle-import:DMELF")
      (libsource (lib "eagle-import") (part "DZMELF"))
    )
    (comp (ref "D11")
      (value "3V6")
      (footprint "eagle-import:DMELF")
      (libsource (lib "eagle-import") (part "DZMELF"))
    )
    (comp (ref "D12")
      (value "3V6")
      (footprint "eagle-import:DMELF")
      (libsource (lib "eagle-import") (part "DZMELF"))
    )
    (comp (ref "Q1")
      (value "12MHz")
      (footprint "eagle-import:SM49")
      (libsource (lib "eagle-import") (part "CRYSTALSM49"))
    )
    (comp (ref "R1")
      (value "4k7")
      (footprint "eagle-import:R0603")
      (libsource (lib "eagle-import") (part "R-EU_R0603"))
    )
    (comp (ref "R2")
      (value "4k7")
      (footprint "eagle-import:R0603")
      (libsource (lib "eagle-import") (part "R-EU_R0603"))
    )
    (comp (ref "R3")
      (value "47")
      (footprint "eagle-import:R0603")
      (libsource (lib "eagle-import") (part "R-EU_R0603"))
    )
    (comp (ref "R4")
      (value "40 1%")
      (footprint "eagle-import:R0805")
      (libsource (lib "eagle-import") (part "R-EU_R0805"))
    )
    (comp (ref "R5")
      (value "40 1%")
      (footprint "eagle-import:R0805")
      (libsource (lib "eagle-import") (part "R-EU_R0805"))
    )
    (comp (ref "R6")
      (value "1k 0.1%")
      (footprint "eagle-import:R0805")
      (libsource (lib "eagle-import") (part "R-EU_R0805"))
    )
    (comp (ref "R7")
      (value "1k 0.1%")
      (footprint "eagle-import:R0805")
      (libsource (lib "eagle-import") (part "R-EU_R0805"))
    )
    (comp (ref "R8")
      (value "4k7")
      (footprint "eagle-import:R0603")
      (libsource (lib "eagle-import") (part "R-EU_R0603"))
    )
    (comp (ref "R10")
      (value "500")
      (footprint "eagle-import:R0805")
      (libsource (lib "eagle-import") (part "rcl_R-EU_R0805"))
    )
    (comp (ref "R11")
      (value "3k")
      (footprint "eagle-import:R0805")
      (libsource (lib "eagle-import") (part "rcl_334_R-EU_R0805"))
    )
    (comp (ref "R12")
      (value "2k")
      (footprint "eagle-import:R0805")
      (libsource (lib "eagle-import") (part "rcl_334_R-EU_R0805"))
    )
    (comp (ref "R13")
      (value "4k7")
      (footprint "eagle-import:R0805")
      (libsource (lib "eagle-import") (part "rcl_334_R-EU_R0805"))
    )
    (comp (ref "R14")
      (value "7k5")
      (footprint "eagle-import:R0805")
      (libsource (lib "eagle-import") (part "rcl_334_R-EU_R0805"))
    )
    (comp (ref "R15")
      (value "500")
      (footprint "eagle-import:R0805")
      (libsource (lib "eagle-import") (part "rcl_R-EU_R0805"))
    )
    (comp (ref "R16")
      (value "3k3")
      (footprint "eagle-import:R0805")
      (libsource (lib "eagle-import") (part "rcl_R-EU_R0805"))
    )
    (comp (ref "R17")
      (value "3k3")
      (footprint "eagle-import:R0805")
      (libsource (lib "eagle-import") (part "rcl_R-EU_R0805"))
    )
    (comp (ref "R22")
      (value "100k")
      (footprint "eagle-import:R0805")
      (libsource (lib "eagle-import") (part "rcl_334_R-EU_R0805"))
    )
    (comp (ref "R23")
      (value "1k")
      (footprint "eagle-import:R0805")
      (libsource (lib "eagle-import") (part "rcl_334_R-EU_R0805"))
    )
    (comp (ref "R24")
      (value "?")
      (footprint "eagle-import:R0805")
      (libsource (lib "eagle-import") (part "rcl_334_R-EU_R0805"))
    )
    (comp (ref "R25")
      (value "?")
      (footprint "eagle-import:R0805")
      (libsource (lib "eagle-import") (part "rcl_334_R-EU_R0805"))
    )
    (comp (ref "R30")
      (value "4k7")
      (footprint "eagle-import:R0603")
      (libsource (lib "eagle-import") (part "R-EU_R0603"))
    )
    (comp (ref "R31")
      (value "47")
      (footprint "eagle-import:R0603")
      (libsource (lib "eagle-import") (part "R-EU_R0603"))
    )
    (comp (ref "R32")
      (value "40 1%")
      (footprint "eagle-import:R0805")
      (libsource (lib "eagle-import") (part "R-EU_R0805"))
    )
    (comp (ref "R33")
      (value "40 1%")
      (footprint "eagle-import:R0805")
      (libsource (lib "eagle-import") (part "R-EU_R0805"))
    )
    (comp (ref "R34")
      (value "1k 0.1%")
      (footprint "eagle-import:R0805")
      (libsource (lib "eagle-import") (part "R-EU_R0805"))
    )
    (comp (ref "R35")
      (value "1k 0.1%")
      (footprint "eagle-import:R0805")
      (libsource (lib "eagle-import") (part "R-EU_R0805"))
    )
    (comp (ref "R36")
      (value "4k7")
      (footprint "eagle-import:R0603")
      (libsource (lib "eagle-import") (part "R-EU_R0603"))
    )
    (comp (ref "R37")
      (value "4k7")
      (footprint "eagle-import:R0603")
      (libsource (lib "eagle-import") (part "R-EU_R0603"))
    )
    (comp (ref "R38")
      (value "47")
      (footprint "eagle-import:R0603")
      (libsource (lib "eagle-import") (part "R-EU_R0603"))
    )
    (comp (ref "R39")
      (value "40 1%")
      (footprint "eagle-import:R0805")
      (libsource (lib "eagle-import") (part "R-EU_R0805"))
    )
    (comp (ref "R40")
      (value "40 1%")
      (footprint "eagle-import:R0805")
      (libsource (lib "eagle-import") (part "R-EU_R0805"))
    )
    (comp (ref "R41")
      (value "1k 0.1%")
      (footprint "eagle-import:R0805")
      (libsource (lib "eagle-import") (part "R-EU_R0805"))
    )
    (comp (ref "R42")
      (value "1k 0.1%")
      (footprint "eagle-import:R0805")
      (libsource (lib "eagle-import") (part "R-EU_R0805"))
    )
    (comp (ref "R43")
      (value "4k7")
      (footprint "eagle-import:R0603")
      (libsource (lib "eagle-import") (part "R-EU_R0603"))
    )
    (comp (ref "R44")
      (value "4k7")
      (footprint "eagle-import:R0603")
      (libsource (lib "eagle-import") (part "R-EU_R0603"))
    )
    (comp (ref "R45")
      (value "47")
      (footprint "eagle-import:R0603")
      (libsource (lib "eagle-import") (part "R-EU_R0603"))
    )
    (comp (ref "R46")
      (value "40 1%")
      (footprint "eagle-import:R0805")
      (libsource (lib "eagle-import") (part "R-EU_R0805"))
    )
    (comp (ref "R47")
      (value "40 1%")
      (footprint "eagle-import:R0805")
      (libsource (lib "eagle-import") (part "R-EU_R0805"))
    )
    (comp (ref "R48")
      (value "1k 0.1%")
      (footprint "eagle-import:R0805")
      (libsource (lib "eagle-import") (part "R-EU_R0805"))
    )
    (comp (ref "R49")
      (value "1k 0.1%")
      (footprint "eagle-import:R0805")
      (libsource (lib "eagle-import") (part "R-EU_R0805"))
    )
    (comp (ref "R50")
      (value "4k7")
      (footprint "eagle-import:R0603")
      (libsource (lib "eagle-import") (part "R-EU_R0603"))
    )
    (comp (ref "R51")
      (value "4k7")
      (footprint "eagle-import:R0603")
      (libsource (lib "eagle-import") (part "R-EU_R0603"))
    )
    (comp (ref "R52")
      (value "47")
      (footprint "eagle-import:R0603")
      (libsource (lib "eagle-import") (part "R-EU_R0603"))
    )
    (comp (ref "R53")
      (value "40 1%")
      (footprint "eagle-import:R0805")
      (libsource (lib "eagle-import") (part "R-EU_R0805"))
    )
    (comp (ref "R54")
      (value "40 1%")
      (footprint "eagle-import:R0805")
      (libsource (lib "eagle-import") (part "R-EU_R0805"))
    )
    (comp (ref "R55")
      (value "1k 0.1%")
      (footprint "eagle-import:R0805")
      (libsource (lib "eagle-import") (part "R-EU_R0805"))
    )
    (comp (ref "R56")
      (value "1k 0.1%")
      (footprint "eagle-import:R0805")
      (libsource (lib "eagle-import") (part "R-EU_R0805"))
    )
    (comp (ref "R57")
      (value "4k7")
      (footprint "eagle-import:R0603")
      (libsource (lib "eagle-import") (part "R-EU_R0603"))
    )
    (comp (ref "R58")
      (value "4k7")
      (footprint "eagle-import:R0603")
      (libsource (lib "eagle-import") (part "R-EU_R0603"))
    )
    (comp (ref "R59")
      (value "47")
      (footprint "eagle-import:R0603")
      (libsource (lib "eagle-import") (part "R-EU_R0603"))
    )
    (comp (ref "R60")
      (value "40 1%")
      (footprint "eagle-import:R0805")
      (libsource (lib "eagle-import") (part "R-EU_R0805"))
    )
    (comp (ref "R61")
      (value "40 1%")
      (footprint "eagle-import:R0805")
      (libsource (lib "eagle-import") (part "R-EU_R0805"))
    )
    (comp (ref "R62")
      (value "1k 0.1%")
      (footprint "eagle-import:R0805")
      (libsource (lib "eagle-import") (part "R-EU_R0805"))
    )
    (comp (ref "R63")
      (value "1k 0.1%")
      (footprint "eagle-import:R0805")
      (libsource (lib "eagle-import") (part "R-EU_R0805"))
    )
    (comp (ref "RN11")
      (value "3k")
      (footprint "eagle-import:EXBS8V")
      (libsource (lib "eagle-import") (part "4R-NEXBS8V"))
    )
    (comp (ref "RN12")
      (value "300")
      (footprint "eagle-import:EXBS8V")
      (libsource (lib "eagle-import") (part "4R-NEXBS8V"))
    )
    (comp (ref "RN_A_PT1")
      (value "47")
      (footprint "eagle-import:0603-ARC")
      (libsource (lib "eagle-import") (part "4R-N0603-ARC"))
    )
    (comp (ref "RN_A_PT2")
      (value "47")
      (footprint "eagle-import:0603-ARC")
      (libsource (lib "eagle-import") (part "4R-N0603-ARC"))
    )
    (comp (ref "RN_A_PT3")
      (value "47")
      (footprint "eagle-import:0603-ARC")
      (libsource (lib "eagle-import") (part "4R-N0603-ARC"))
    )
    (comp (ref "RN_B_PT1")
      (value "47")
      (footprint "eagle-import:0603-ARC")
      (libsource (lib "eagle-import") (part "4R-N0603-ARC"))
    )
    (comp (ref "RN_B_PT2")
      (value "47")
      (footprint "eagle-import:0603-ARC")
      (libsource (lib "eagle-import") (part "4R-N0603-ARC"))
    )
    (comp (ref "RN_B_PT3")
      (value "47")
      (footprint "eagle-import:0603-ARC")
      (libsource (lib "eagle-import") (part "4R-N0603-ARC"))
    )
    (comp (ref "RN_DMS1")
      (value "47")
      (footprint "eagle-import:0603-ARC")
      (libsource (lib "eagle-import") (part "4R-N0603-ARC"))
    )
    (comp (ref "RN_DMS2")
      (value "47")
      (footprint "eagle-import:0603-ARC")
      (libsource (lib "eagle-import") (part "4R-N0603-ARC"))
    )
    (comp (ref "RN_DMS3")
      (value "47")
      (footprint "eagle-import:0603-ARC")
      (libsource (lib "eagle-import") (part "4R-N0603-ARC"))
    )
    (comp (ref "RN_DMS4")
      (value "47")
      (footprint "eagle-import:0603-ARC")
      (libsource (lib "eagle-import") (part "4R-N0603-ARC"))
    )
    (comp (ref "RN_DMS5")
      (value "47")
      (footprint "eagle-import:0603-ARC")
      (libsource (lib "eagle-import") (part "4R-N0603-ARC"))
    )
    (comp (ref "RN_DMS6")
      (value "47")
      (footprint "eagle-import:0603-ARC")
      (libsource (lib "eagle-import") (part "4R-N0603-ARC"))
    )
    (comp (ref "R_I1_PT1")
      (value "R-EU_R0603")
      (footprint "eagle-import:R0603")
      (libsource (lib "eagle-import") (part "R-EU_R0603"))
    )
    (comp (ref "R_I1_PT2")
      (value "R-EU_R0603")
      (footprint "eagle-import:R0603")
      (libsource (lib "eagle-import") (part "R-EU_R0603"))
    )
    (comp (ref "R_I1_PT3")
      (value "R-EU_R0603")
      (footprint "eagle-import:R0603")
      (libsource (lib "eagle-import") (part "R-EU_R0603"))
    )
    (comp (ref "R_I2_PT1")
      (value "R-EU_R0603")
      (footprint "eagle-import:R0603")
      (libsource (lib "eagle-import") (part "R-EU_R0603"))
    )
    (comp (ref "R_I2_PT2")
      (value "R-EU_R0603")
      (footprint "eagle-import:R0603")
      (libsource (lib "eagle-import") (part "R-EU_R0603"))
    )
    (comp (ref "R_I2_PT3")
      (value "R-EU_R0603")
      (footprint "eagle-import:R0603")
      (libsource (lib "eagle-import") (part "R-EU_R0603"))
    )
    (comp (ref "R_R1_PT1")
      (value "R-EU_R0603")
      (footprint "eagle-import:R0603")
      (libsource (lib "eagle-import") (part "R-EU_R0603"))
    )
    (comp (ref "R_R1_PT2")
      (value "R-EU_R0603")
      (footprint "eagle-import:R0603")
      (libsource (lib "eagle-import") (part "R-EU_R0603"))
    )
    (comp (ref "R_R1_PT3")
      (value "R-EU_R0603")
      (footprint "eagle-import:R0603")
      (libsource (lib "eagle-import") (part "R-EU_R0603"))
    )
    (comp (ref "R_R2_PT1")
      (value "R-EU_R0603")
      (footprint "eagle-import:R0603")
      (libsource (lib "eagle-import") (part "R-EU_R0603"))
    )
    (comp (ref "R_R2_PT2")
      (value "R-EU_R0603")
      (footprint "eagle-import:R0603")
      (libsource (lib "eagle-import") (part "R-EU_R0603"))
    )
    (comp (ref "R_R2_PT3")
      (value "R-EU_R0603")
      (footprint "eagle-import:R0603")
      (libsource (lib "eagle-import") (part "R-EU_R0603"))
    )
    (comp (ref "R_REF_PT1")
      (value "R-EU_R0603")
      (footprint "eagle-import:R0603")
      (libsource (lib "eagle-import") (part "R-EU_R0603"))
    )
    (comp (ref "R_REF_PT2")
      (value "R-EU_R0603")
      (footprint "eagle-import:R0603")
      (libsource (lib "eagle-import") (part "R-EU_R0603"))
    )
    (comp (ref "R_REF_PT3")
      (value "R-EU_R0603")
      (footprint "eagle-import:R0603")
      (libsource (lib "eagle-import") (part "R-EU_R0603"))
    )
    (comp (ref "U$1")
      (value "COMMON_MODE_CHOKE")
      (footprint "eagle-import:COMMON_MODE_CHOKE")
      (libsource (lib "eagle-import") (part "COMMON_MODE_CHOKE"))
    )
    (comp (ref "U$2")
      (value "COMMON_MODE_CHOKE")
      (footprint "eagle-import:COMMON_MODE_CHOKE")
      (libsource (lib "eagle-import") (part "COMMON_MODE_CHOKE"))
    )
    (comp (ref "U$3")
      (value "COMMON_MODE_CHOKE")
      (footprint "eagle-import:COMMON_MODE_CHOKE")
      (libsource (lib "eagle-import") (part "COMMON_MODE_CHOKE"))
    )
    (comp (ref "U$4")
      (value "COMMON_MODE_CHOKE")
      (footprint "eagle-import:COMMON_MODE_CHOKE")
      (libsource (lib "eagle-import") (part "COMMON_MODE_CHOKE"))
    )
    (comp (ref "U$5")
      (value "COMMON_MODE_CHOKE")
      (footprint "eagle-import:COMMON_MODE_CHOKE")
      (libsource (lib "eagle-import") (part "COMMON_MODE_CHOKE"))
    )
    (comp (ref "U$6")
      (value "COMMON_MODE_CHOKE")
      (footprint "eagle-import:COMMON_MODE_CHOKE")
      (libsource (lib "eagle-import") (part "COMMON_MODE_CHOKE"))
    )
    (comp (ref "U_7805")
      (value "LM78L05ACMX/NOPB")
      (footprint "eagle-import:SOIC8")
      (libsource (lib "eagle-import") (part "LM78L05ACMX/NOPB"))
    )
    (comp (ref "U_ADC_DMS1")
      (value "ADS1147TSSOP20")
      (footprint "eagle-import:TSSOP20")
      (libsource (lib "eagle-import") (part "ADS1147TSSOP20"))
    )
    (comp (ref "U_ADC_DMS2")
      (value "ADS1147TSSOP20")
      (footprint "eagle-import:TSSOP20")
      (libsource (lib "eagle-import") (part "ADS1147TSSOP20"))
    )
    (comp (ref "U_ADC_DMS3")
      (value "ADS1147TSSOP20")
      (footprint "eagle-import:TSSOP20")
      (libsource (lib "eagle-import") (part "ADS1147TSSOP20"))
    )
    (comp (ref "U_ADC_DMS4")
      (value "ADS1147TSSOP20")
      (footprint "eagle-import:TSSOP20")
      (libsource (lib "eagle-import") (part "ADS1147TSSOP20"))
    )
    (comp (ref "U_ADC_DMS5")
      (value "ADS1147TSSOP20")
      (footprint "eagle-import:TSSOP20")
      (libsource (lib "eagle-import") (part "ADS1147TSSOP20"))
    )
    (comp (ref "U_ADC_DMS6")
      (value "ADS1147TSSOP20")
      (footprint "eagle-import:TSSOP20")
      (libsource (lib "eagle-import") (part "ADS1147TSSOP20"))
    )
    (comp (ref "U_ADC_PT1")
      (value "ADS1147TSSOP20")
      (footprint "eagle-import:TSSOP20")
      (libsource (lib "eagle-import") (part "ADS1147TSSOP20"))
    )
    (comp (ref "U_ADC_PT2")
      (value "ADS1147TSSOP20")
      (footprint "eagle-import:TSSOP20")
      (libsource (lib "eagle-import") (part "ADS1147TSSOP20"))
    )
    (comp (ref "U_ADC_PT3")
      (value "ADS1147TSSOP20")
      (footprint "eagle-import:TSSOP20")
      (libsource (lib "eagle-import") (part "ADS1147TSSOP20"))
    )
    (comp (ref "U_ADR366_3")
      (value "ADR366WAUJZ")
      (footprint "eagle-import:SOT23-5")
      (libsource (lib "eagle-import") (part "ADR36UJZ_"))
    )
    (comp (ref "U_CH340G")
      (value "CH340G")
      (footprint "eagle-import:SOIC16")
      (libsource (lib "eagle-import") (part "CH340G"))
    )
    (comp (ref "U_LT1528")
      (value "LT1528")
      (footprint "eagle-import:Q5-DD")
      (libsource (lib "eagle-import") (part "LT1528"))
    )
    (comp (ref "U_MAX488")
      (value "MAX488CSA")
      (footprint "eagle-import:SO08")
      (fields (field (name "MF") "MAXIM"))
      (libsource (lib "eagle-import") (part "MAX488CSA"))
    )
    (comp (ref "U_OPTO_1")
      (value "MOCD207MSOIC-8")
      (footprint "eagle-import:SOIC127P594X363-8N")
      (fields (field (name "MANUFACTURER") "ON Semiconductor") (field (name "MPN") "MOCD207M"))
      (libsource (lib "eagle-import") (part "MOCD207MSOIC-8"))
    )
    (comp (ref "U_OPTO_2")
      (value "MOCD207MSOIC-8")
      (footprint "eagle-import:SOIC127P594X363-8N")
      (fields (field (name "MANUFACTURER") "ON Semiconductor") (field (name "MPN") "MOCD207M"))
      (libsource (lib "eagle-import") (part "MOCD207MSOIC-8"))
    )
    (comp (ref "U_OPTO_3")
      (value "MOCD207MSOIC-8")
      (footprint "eagle-import:SOIC127P594X363-8N")
      (fields (field (name "MANUFACTURER") "ON Semiconductor") (field (name "MPN") "MOCD207M"))
      (libsource (lib "eagle-import") (part "MOCD207MSOIC-8"))
    )
    (comp (ref "U_S70FL01GS_1")
      (value "S70FL01GS")
      (footprint "eagle-import:SO16")
      (libsource (lib "eagle-import") (part "S70FL01GS"))
    )
    (comp (ref "U_S70FL01GS_2")
      (value "S70FL01GS")
      (footprint "eagle-import:SO16")
      (libsource (lib "eagle-import") (part "S70FL01GS"))
    )
    (comp (ref "U_TRACODCDC")
      (value "THN10-2411WIR")
      (footprint "eagle-import:THL_20WI_SERIES")
      (libsource (lib "eagle-import") (part "THL_20WI_SERIES"))
    )
  )
  (nets
    (net (code "1") (name "3V3") (class "Default")
      (node (ref "C10") (pin "1") (pinfunction "1_1") (pintype "passive"))
      (node (ref "C15") (pin "1") (pinfunction "1_1") (pintype "passive"))
      (node (ref "C19") (pin "1") (pinfunction "1_1") (pintype "passive"))
      (node (ref "C24") (pin "1") (pinfunction "1_1") (pintype "passive"))
      (node (ref "C25") (pin "1") (pinfunction "1_1") (pintype "passive"))
      (node (ref "C28") (pin "1") (pinfunction "1_1") (pintype "passive"))
      (node (ref "C29") (pin "1") (pinfunction "1_1") (pintype "passive"))
      (node (ref "C3") (pin "1") (pinfunction "1_1") (pintype "passive"))
      (node (ref "C30") (pin "1") (pinfunction "1_1") (pintype "passive"))
      (node (ref "C31") (pin "1") (pinfunction "1_1") (pintype "passive"))
      (node (ref "C32") (pin "1") (pinfunction "1_1") (pintype "passive"))
      (node (ref "C33") (pin "1") (pinfunction "1_1") (pintype "passive"))
      (node (ref "C37") (pin "2") (pinfunction "2_2") (pintype "passive"))
      (node (ref "C41") (pin "+") (pinfunction "+_+") (pintype "passive"))
      (node (ref "C48") (pin "1") (pinfunction "1_1") (pintype "passive"))
      (node (ref "C5") (pin "1") (pinfunction "1_1") (pintype "passive"))
      (node (ref "C55") (pin "1") (pinfunction "1_1") (pintype "passive"))
      (node (ref "C9") (pin "1") (pinfunction "1_1") (pintype "passive"))
      (node (ref "C_AVDD_PT1") (pin "1") (pinfunction "1_1") (pintype "passive"))
      (node (ref "C_AVDD_PT2") (pin "1") (pinfunction "1_1") (pintype "passive"))
      (node (ref "C_AVDD_PT3") (pin "1") (pinfunction "1_1") (pintype "passive"))
      (node (ref "C_DVDD_PT1") (pin "1") (pinfunction "1_1") (pintype "passive"))
      (node (ref "C_DVDD_PT2") (pin "1") (pinfunction "1_1") (pintype "passive"))
      (node (ref "C_DVDD_PT3") (pin "1") (pinfunction "1_1") (pintype "passive"))
      (node (ref "R1") (pin "1") (pinfunction "1_1") (pintype "passive"))
      (node (ref "R13") (pin "2") (pinfunction "2_2") (pintype "passive"))
      (node (ref "R19") (pin "2") (pinfunction "2_2") (pintype "passive"))
      (node (ref "R2") (pin "2") (pinfunction "2_2") (pintype "passive"))
      (node (ref "R26") (pin "2") (pinfunction "2_2") (pintype "passive"))
      (node (ref "R28") (pin "1") (pinfunction "1_1") (pintype "passive"))
      (node (ref "R29") (pin "2") (pinfunction "2_2") (pintype "passive"))
      (node (ref "R30") (pin "2") (pinfunction "2_2") (pintype "passive"))
      (node (ref "R34") (pin "2") (pinfunction "2_2") (pintype "passive"))
      (node (ref "R36") (pin "1") (pinfunction "1_1") (pintype "passive"))
      (node (ref "R37") (pin "2") (pinfunction "2_2") (pintype "passive"))
      (node (ref "R41") (pin "2") (pinfunction "2_2") (pintype "passive"))
      (node (ref "R43") (pin "1") (pinfunction "1_1") (pintype "passive"))
      (node (ref "R44") (pin "2") (pinfunction "2_2") (pintype "passive"))
      (node (ref "R48") (pin "2") (pinfunction "2_2") (pintype "passive"))
      (node (ref "R51") (pin "2") (pinfunction "2_2") (pintype "passive"))
      (node (ref "R55") (pin "2") (pinfunction "2_2") (pintype "passive"))
      (node (ref "R58") (pin "2") (pinfunction "2_2") (pintype "passive"))
      (node (ref "R6") (pin "2") (pinfunction "2_2") (pintype "passive"))
      (node (ref "R62") (pin "2") (pinfunction "2_2") (pintype "passive"))
      (node (ref "R8") (pin "1") (pinfunction "1_1") (pintype "passive"))
      (node (ref "R9") (pin "2") (pinfunction "2_2") (pintype "passive"))
      (node (ref "RN12") (pin "1") (pinfunction "1_1") (pintype "passive"))
      (node (ref "RN12") (pin "2") (pinfunction "1_2") (pintype "passive"))
      (node (ref "RN12") (pin "3") (pinfunction "1_3") (pintype "passive"))
      (node (ref "RN12") (pin "4") (pinfunction "1_4") (pintype "passive"))
      (node (ref "RN_A_PT1") (pin "8") (pinfunction "2_8") (pintype "passive"))
      (node (ref "RN_A_PT2") (pin "8") (pinfunction "2_8") (pintype "passive"))
      (node (ref "RN_A_PT3") (pin "8") (pinfunction "2_8") (pintype "passive"))
      (node (ref "RN_B_PT1") (pin "6") (pinfunction "2_6") (pintype "passive"))
      (node (ref "RN_B_PT2") (pin "6") (pinfunction "2_6") (pintype "passive"))
      (node (ref "RN_B_PT3") (pin "6") (pinfunction "2_6") (pintype "passive"))
      (node (ref "U$1") (pin "P$2") (pinfunction "2_P$2") (pintype "passive"))
      (node (ref "U$2") (pin "P$2") (pinfunction "2_P$2") (pintype "passive"))
      (node (ref "U$3") (pin "P$2") (pinfunction "2_P$2") (pintype "passive"))
      (node (ref "U$4") (pin "P$2") (pinfunction "2_P$2") (pintype "passive"))
      (node (ref "U$5") (pin "P$2") (pinfunction "2_P$2") (pintype "passive"))
      (node (ref "U$6") (pin "P$2") (pinfunction "2_P$2") (pintype "passive"))
      (node (ref "U_ADC_DMS1") (pin "1") (pinfunction "DVDD_1") (pintype "bidirectional"))
      (node (ref "U_ADC_DMS1") (pin "14") (pinfunction "AVDD_14") (pintype "bidirectional"))
      (node (ref "U_ADC_DMS2") (pin "1") (pinfunction "DVDD_1") (pintype "bidirectional"))
      (node (ref "U_ADC_DMS2") (pin "14") (pinfunction "AVDD_14") (pintype "bidirectional"))
      (node (ref "U_ADC_DMS3") (pin "1") (pinfunction "DVDD_1") (pintype "bidirectional"))
      (node (ref "U_ADC_DMS3") (pin "14") (pinfunction "AVDD_14") (pintype "bidirectional"))
      (node (ref "U_ADC_DMS4") (pin "1") (pinfunction "DVDD_1") (pintype "bidirectional"))
      (node (ref "U_ADC_DMS4") (pin "14") (pinfunction "AVDD_14") (pintype "bidirectional"))
      (node (ref "U_ADC_DMS5") (pin "14") (pinfunction "AVDD_14") (pintype "bidirectional"))
      (node (ref "U_ADC_DMS6") (pin "14") (pinfunction "AVDD_14") (pintype "bidirectional"))
      (node (ref "U_ADC_PT1") (pin "1") (pinfunction "DVDD_1") (pintype "bidirectional"))
      (node (ref "U_ADC_PT1") (pin "14") (pinfunction "AVDD_14") (pintype "bidirectional"))
      (node (ref "U_ADC_PT2") (pin "1") (pinfunction "DVDD_1") (pintype "bidirectional"))
      (node (ref "U_ADC_PT2") (pin "14") (pinfunction "AVDD_14") (pintype "bidirectional"))
      (node (ref "U_ADC_PT3") (pin "1") (pinfunction "DVDD_1") (pintype "bidirectional"))
      (node (ref "U_ADC_PT3") (pin "14") (pinfunction "AVDD_14") (pintype "bidirectional"))
      (node (ref "U_CH340G") (pin "16") (pinfunction "VCC_16") (pintype "bidirectional"))
      (node (ref "U_LT1528") (pin "1") (pinfunction "OUT_1") (pintype "bidirectional"))
      (node (ref "U_LT1528") (pin "2") (pinfunction "SENSE_2") (pintype "bidirectional"))
      (node (ref "U_S70FL01GS_1") (pin "2") (pinfunction "VCC_2") (pintype "bidirectional"))
      (node (ref "U_S70FL01GS_2") (pin "2") (pinfunction "VCC_2") (pintype "bidirectional"))
      (node (ref "U_STM32F779") (pin "103") (pinfunction "VDD_103") (pintype "bidirectional"))
      (node (ref "U_STM32F779") (pin "115") (pinfunction "VDD_115") (pintype "bidirectional"))
      (node (ref "U_STM32F779") (pin "118") (pinfunction "VDDDSI_118") (pintype "bidirectional"))
      (node (ref "U_STM32F779") (pin "137") (pinfunction "VDDUSB_137") (pintype "bidirectional"))
      (node (ref "U_STM32F779") (pin "15") (pinfunction "VDD_15") (pintype "bidirectional"))
      (node (ref "U_STM32F779") (pin "150") (pinfunction "VDD_150") (pintype "bidirectional"))
      (node (ref "U_STM32F779") (pin "158") (pinfunction "VDD_158") (pintype "bidirectional"))
      (node (ref "U_STM32F779") (pin "171") (pinfunction "VDDSDMMC_171") (pintype "bidirectional"))
      (node (ref "U_STM32F779") (pin "185") (pinfunction "VDD_185") (pintype "bidirectional"))
      (node (ref "U_STM32F779") (pin "204") (pinfunction "VDD_204") (pintype "bidirectional"))
      (node (ref "U_STM32F779") (pin "26") (pinfunction "VDD_26") (pintype "bidirectional"))
      (node (ref "U_STM32F779") (pin "39") (pinfunction "VDD_39") (pintype "bidirectional"))
      (node (ref "U_STM32F779") (pin "42") (pinfunction "VDDA_42") (pintype "bidirectional"))
      (node (ref "U_STM32F779") (pin "52") (pinfunction "VDD_52") (pintype "bidirectional"))
      (node (ref "U_STM32F779") (pin "59") (pinfunction "VDD_59") (pintype "bidirectional"))
      (node (ref "U_STM32F779") (pin "73") (pinfunction "VDD_73") (pintype "bidirectional"))
      (node (ref "U_STM32F779") (pin "83") (pinfunction "VDD_83") (pintype "bidirectional"))
      (node (ref "U_STM32F779") (pin "94") (pinfunction "VDD_94") (pintype "bidirectional"))
      (node (ref "X_PROG") (pin "1") (pinfunction "1_1") (pintype "passive"))
    )
    (net (code "2") (name "3V3CAP") (class "Default")
      (node (ref "U_STM32F779") (pin "6") (pinfunction "VBAT_6") (pintype "bidirectional"))
    )
    (net (code "3") (name "3V3REF") (class "Default")
      (node (ref "R24") (pin "2") (pinfunction "2_2") (pintype "passive"))
      (node (ref "U_ADR366_3") (pin "4") (pinfunction "VOUT_4") (pintype "power_in"))
      (node (ref "U_STM32F779") (pin "41") (pinfunction "VREF+_41") (pintype "bidirectional"))
    )
    (net (code "4") (name "5V") (class "Default")
      (node (ref "C35") (pin "2") (pinfunction "2_2") (pintype "passive"))
      (node (ref "C36") (pin "2") (pinfunction "2_2") (pintype "passive"))
      (node (ref "C39") (pin "+") (pinfunction "+_+") (pintype "passive"))
      (node (ref "C40") (pin "+") (pinfunction "+_+") (pintype "passive"))
      (node (ref "C52") (pin "2") (pinfunction "2_2") (pintype "passive"))
      (node (ref "R18") (pin "2") (pinfunction "2_2") (pintype "passive"))
      (node (ref "U_ADR366_3") (pin "3") (pinfunction "VIN_3") (pintype "power_in"))
      (node (ref "U_LT1528") (pin "4") (pinfunction "SHDN_4") (pintype "bidirectional"))
      (node (ref "U_LT1528") (pin "5") (pinfunction "IN_5") (pintype "bidirectional"))
      (node (ref "U_TRACODCDC") (pin "3") (pinfunction "+VOUT_3") (pintype "passive"))
      (node (ref "X_RXSM-DAPI") (pin "P$A9") (pinfunction "A9_P$A9") (pintype "passive"))
    )
    (net (code "5") (name "5V-28V") (class "Default")
      (node (ref "C43") (pin "1") (pinfunction "1_1") (pintype "passive"))
      (node (ref "R14") (pin "2") (pinfunction "2_2") (pintype "passive"))
      (node (ref "R16") (pin "1") (pinfunction "1_1") (pintype "passive"))
      (node (ref "R21") (pin "2") (pinfunction "2_2") (pintype "passive"))
      (node (ref "U_7805") (pin "1") (pinfunction "VOUT_1") (pintype "bidirectional"))
      (node (ref "U_MAX488") (pin "1") (pinfunction "VCC_1") (pintype "power_in"))
    )
    (net (code "6") (name "28V") (class "Default")
      (node (ref "C34") (pin "2") (pinfunction "2_2") (pintype "passive"))
      (node (ref "C38") (pin "+") (pinfunction "+_+") (pintype "passive"))
      (node (ref "C42") (pin "2") (pinfunction "2_2") (pintype "passive"))
      (node (ref "R20") (pin "2") (pinfunction "2_2") (pintype "passive"))
      (node (ref "RN11") (pin "1") (pinfunction "1_1") (pintype "passive"))
      (node (ref "RN11") (pin "2") (pinfunction "1_2") (pintype "passive"))
      (node (ref "RN11") (pin "3") (pinfunction "1_3") (pintype "passive"))
      (node (ref "RN11") (pin "4") (pinfunction "1_4") (pintype "passive"))
      (node (ref "U_7805") (pin "8") (pinfunction "VIN_8") (pintype "bidirectional"))
      (node (ref "U_TRACODCDC") (pin "1") (pinfunction "+VIN_1") (pintype "input"))
      (node (ref "X_MIRROR") (pin "P$A2") (pinfunction "A2_P$A2") (pintype "passive"))
      (node (ref "X_MIRROR") (pin "P$A3") (pinfunction "A3_P$A3") (pintype "passive"))
      (node (ref "X_MIRROR") (pin "P$A4") (pinfunction "A4_P$A4") (pintype "passive"))
      (node (ref "X_MIRROR1") (pin "P$A10") (pinfunction "A10_P$A10") (pintype "passive"))
      (node (ref "X_MIRROR1") (pin "P$A11") (pinfunction "A11_P$A11") (pintype "passive"))
      (node (ref "X_MIRROR1") (pin "P$A12") (pinfunction "A12_P$A12") (pintype "passive"))
      (node (ref "X_RXSM-DAPI") (pin "P$B1") (pinfunction "B1_P$B1") (pintype "passive"))
      (node (ref "X_RXSM-DAPI") (pin "P$B2") (pinfunction "B2_P$B2") (pintype "passive"))
    )
    (net (code "7") (name "28VGND") (class "Default")
      (node (ref "C34") (pin "1") (pinfunction "1_1") (pintype "passive"))
      (node (ref "C38") (pin "-") (pinfunction "-_-") (pintype "passive"))
      (node (ref "C42") (pin "1") (pinfunction "1_1") (pintype "passive"))
      (node (ref "C43") (pin "2") (pinfunction "2_2") (pintype "passive"))
      (node (ref "C44") (pin "2") (pinfunction "2_2") (pintype "passive"))
      (node (ref "D5") (pin "A") (pinfunction "A_A") (pintype "passive"))
      (node (ref "D6") (pin "A") (pinfunction "A_A") (pintype "passive"))
      (node (ref "LED7") (pin "C") (pinfunction "C_C") (pintype "passive"))
      (node (ref "LED8") (pin "C") (pinfunction "C_C") (pintype "passive"))
      (node (ref "R11") (pin "1") (pinfunction "1_1") (pintype "passive"))
      (node (ref "R17") (pin "1") (pinfunction "1_1") (pintype "passive"))
      (node (ref "U_7805") (pin "2") (pinfunction "GND_2") (pintype "bidirectional"))
      (node (ref "U_7805") (pin "3") (pinfunction "GND_3") (pintype "bidirectional"))
      (node (ref "U_7805") (pin "6") (pinfunction "GND_6") (pintype "bidirectional"))
      (node (ref "U_7805") (pin "7") (pinfunction "GND_7") (pintype "bidirectional"))
      (node (ref "U_MAX488") (pin "4") (pinfunction "GND_4") (pintype "power_in"))
      (node (ref "U_OPTO_3") (pin "5") (pinfunction "EMT2_5") (pintype "output"))
      (node (ref "U_TRACODCDC") (pin "2") (pinfunction "-VIN_2") (pintype "input"))
      (node (ref "X_MIRROR") (pin "P$A1") (pinfunction "A1_P$A1") (pintype "passive"))
      (node (ref "X_MIRROR") (pin "P$B1") (pinfunction "B1_P$B1") (pintype "passive"))
      (node (ref "X_MIRROR") (pin "P$B2") (pinfunction "B2_P$B2") (pintype "passive"))
      (node (ref "X_MIRROR") (pin "P$B3") (pinfunction "B3_P$B3") (pintype "passive"))
      (node (ref "X_MIRROR") (pin "P$B4") (pinfunction "B4_P$B4") (pintype "passive"))
      (node (ref "X_MIRROR") (pin "P$B5") (pinfunction "B5_P$B5") (pintype "passive"))
      (node (ref "X_MIRROR") (pin "P$B6") (pinfunction "B6_P$B6") (pintype "passive"))
      (node (ref "X_MIRROR") (pin "P$B7") (pinfunction "B7_P$B7") (pintype "passive"))
      (node (ref "X_MIRROR") (pin "P$BL1") (pinfunction "CASE_P$BL1") (pintype "passive"))
      (node (ref "X_MIRROR") (pin "P$BL2") (pinfunction "CASE_P$BL2") (pintype "passive"))
      (node (ref "X_MIRROR") (pin "P$BL3") (pinfunction "CASE_P$BL3") (pintype "passive"))
      (node (ref "X_MIRROR") (pin "P$BL4") (pinfunction "CASE_P$BL4") (pintype "passive"))
      (node (ref "X_MIRROR1") (pin "P$A13") (pinfunction "A13_P$A13") (pintype "passive"))
      (node (ref "X_MIRROR1") (pin "P$B10") (pinfunction "B10_P$B10") (pintype "passive"))
      (node (ref "X_MIRROR1") (pin "P$B11") (pinfunction "B11_P$B11") (pintype "passive"))
      (node (ref "X_MIRROR1") (pin "P$B12") (pinfunction "B12_P$B12") (pintype "passive"))
      (node (ref "X_MIRROR1") (pin "P$B13") (pinfunction "B13_P$B13") (pintype "passive"))
      (node (ref "X_MIRROR1") (pin "P$B7") (pinfunction "B7_P$B7") (pintype "passive"))
      (node (ref "X_MIRROR1") (pin "P$B8") (pinfunction "B8_P$B8") (pintype "passive"))
      (node (ref "X_MIRROR1") (pin "P$B9") (pinfunction "B9_P$B9") (pintype "passive"))
      (node (ref "X_MIRROR1") (pin "P$BL1") (pinfunction "CASE_P$BL1") (pintype "passive"))
      (node (ref "X_MIRROR1") (pin "P$BL2") (pinfunction "CASE_P$BL2") (pintype "passive"))
      (node (ref "X_MIRROR1") (pin "P$BL3") (pinfunction "CASE_P$BL3") (pintype "passive"))
      (node (ref "X_MIRROR1") (pin "P$BL4") (pinfunction "CASE_P$BL4") (pintype "passive"))
      (node (ref "X_RXSM-DAPI") (pin "P$A1") (pinfunction "A1_P$A1") (pintype "passive"))
      (node (ref "X_RXSM-DAPI") (pin "P$A2") (pinfunction "A2_P$A2") (pintype "passive"))
      (node (ref "X_RXSM-DAPI") (pin "P$A6") (pinfunction "A6_P$A6") (pintype "passive"))
    )
    (net (code "8") (name "ADC1_DRDY") (class "Default")
      (node (ref "U_STM32F779") (pin "65") (pinfunction "PJ0_65") (pintype "bidirectional"))
    )
    (net (code "9") (name "ADC1_RES") (class "Default")
      (node (ref "U_STM32F779") (pin "68") (pinfunction "PJ3_68") (pintype "bidirectional"))
    )
    (net (code "10") (name "ADC1_START") (class "Default")
      (node (ref "U_STM32F779") (pin "67") (pinfunction "PJ2_67") (pintype "bidirectional"))
    )
    (net (code "11") (name "ADC2_DRDY") (class "Default")
      (node (ref "U_STM32F779") (pin "47") (pinfunction "PH3_47") (pintype "bidirectional"))
    )
    (net (code "12") (name "ADC2_RES") (class "Default")
      (node (ref "U_STM32F779") (pin "50") (pinfunction "PA3_50") (pintype "bidirectional"))
    )
    (net (code "13") (name "ADC2_START") (class "Default")
      (node (ref "U_STM32F779") (pin "49") (pinfunction "PH5_49") (pintype "bidirectional"))
    )
    (net (code "14") (name "ADC3_DRDY") (class "Default")
      (node (ref "U_STM32F779") (pin "71") (pinfunction "PF12_71") (pintype "bidirectional"))
    )
    (net (code "15") (name "ADC3_RES") (class "Default")
      (node (ref "U_STM32F779") (pin "76") (pinfunction "PF15_76") (pintype "bidirectional"))
    )
    (net (code "16") (name "ADC3_START") (class "Default")
      (node (ref "U_STM32F779") (pin "75") (pinfunction "PF14_75") (pintype "bidirectional"))
    )
    (net (code "17") (name "ADC4_DRDY") (class "Default")
      (node (ref "U_STM32F779") (pin "32") (pinfunction "PH0_32") (pintype "bidirectional"))
    )
    (net (code "18") (name "ADC4_RES") (class "Default")
      (node (ref "U_STM32F779") (pin "31") (pinfunction "PF10_31") (pintype "bidirectional"))
    )
    (net (code "19") (name "ADC4_START") (class "Default")
      (node (ref "U_STM32F779") (pin "30") (pinfunction "PF9_30") (pintype "bidirectional"))
    )
    (net (code "20") (name "ADC5_DRDY") (class "Default")
      (node (ref "U_STM32F779") (pin "44") (pinfunction "PA1_44") (pintype "bidirectional"))
    )
    (net (code "21") (name "ADC5_RES") (class "Default")
      (node (ref "U_STM32F779") (pin "37") (pinfunction "PC2_37") (pintype "bidirectional"))
    )
    (net (code "22") (name "ADC5_START") (class "Default")
      (node (ref "U_STM32F779") (pin "35") (pinfunction "PC0_35") (pintype "bidirectional"))
    )
    (net (code "23") (name "ADC6_DRDY") (class "Default")
      (node (ref "U_STM32F779") (pin "45") (pinfunction "PA2_45") (pintype "bidirectional"))
    )
    (net (code "24") (name "ADC6_RES") (class "Default")
      (node (ref "U_STM32F779") (pin "33") (pinfunction "PH1_33") (pintype "bidirectional"))
    )
    (net (code "25") (name "ADC6_START") (class "Default")
      (node (ref "U_STM32F779") (pin "38") (pinfunction "PC3_38") (pintype "bidirectional"))
    )
    (net (code "26") (name "DAPI_N") (class "Default")
      (node (ref "D1") (pin "C") (pinfunction "C_C") (pintype "passive"))
      (node (ref "U_CH340G") (pin "6") (pinfunction "D-_6") (pintype "bidirectional"))
      (node (ref "X_RXSM-DAPI") (pin "P$B9") (pinfunction "B9_P$B9") (pintype "passive"))
    )
    (net (code "27") (name "DAPI_P") (class "Default")
      (node (ref "D2") (pin "C") (pinfunction "C_C") (pintype "passive"))
      (node (ref "U_CH340G") (pin "5") (pinfunction "D+_5") (pintype "bidirectional"))
      (node (ref "X_RXSM-DAPI") (pin "P$B10") (pinfunction "B10_P$B10") (pintype "passive"))
    )
    (net (code "28") (name "DAPI_RX") (class "Default")
      (node (ref "D4") (pin "C") (pinfunction "C_C") (pintype "passive"))
      (node (ref "U_CH340G") (pin "2") (pinfunction "TX_2") (pintype "bidirectional"))
      (node (ref "U_STM32F779") (pin "11") (pinfunction "PI9_11") (pintype "bidirectional"))
    )
    (net (code "29") (name "DAPI_TX") (class "Default")
      (node (ref "D3") (pin "C") (pinfunction "C_C") (pintype "passive"))
      (node (ref "U_CH340G") (pin "3") (pinfunction "RX_3") (pintype "bidirectional"))
      (node (ref "U_STM32F779") (pin "43") (pinfunction "PA0_43") (pintype "bidirectional"))
    )
    (net (code "30") (name "DMS11") (class "Default")
      (node (ref "U$2") (pin "P$1") (pinfunction "1_P$1") (pintype "passive"))
      (node (ref "X1") (pin "P$B3") (pinfunction "B3_P$B3") (pintype "passive"))
    )
    (net (code "31") (name "DMS12") (class "Default")
      (node (ref "U$2") (pin "P$3") (pinfunction "3_P$3") (pintype "passive"))
      (node (ref "X1") (pin "P$B2") (pinfunction "B2_P$B2") (pintype "passive"))
    )
    (net (code "32") (name "DMS13") (class "Default")
      (node (ref "U$2") (pin "P$5") (pinfunction "5_P$5") (pintype "passive"))
      (node (ref "X1") (pin "P$B1") (pinfunction "B1_P$B1") (pintype "passive"))
    )
    (net (code "33") (name "DMS21") (class "Default")
      (node (ref "U$1") (pin "P$1") (pinfunction "1_P$1") (pintype "passive"))
      (node (ref "X1") (pin "P$B6") (pinfunction "B6_P$B6") (pintype "passive"))
    )
    (net (code "34") (name "DMS22") (class "Default")
      (node (ref "U$1") (pin "P$3") (pinfunction "3_P$3") (pintype "passive"))
      (node (ref "X1") (pin "P$B5") (pinfunction "B5_P$B5") (pintype "passive"))
    )
    (net (code "35") (name "DMS23") (class "Default")
      (node (ref "U$1") (pin "P$5") (pinfunction "5_P$5") (pintype "passive"))
      (node (ref "X1") (pin "P$B4") (pinfunction "B4_P$B4") (pintype "passive"))
    )
    (net (code "36") (name "DMS31") (class "Default")
      (node (ref "U$3") (pin "P$1") (pinfunction "1_P$1") (pintype "passive"))
      (node (ref "X1") (pin "P$B9") (pinfunction "B9_P$B9") (pintype "passive"))
    )
    (net (code "37") (name "DMS32") (class "Default")
      (node (ref "U$3") (pin "P$3") (pinfunction "3_P$3") (pintype "passive"))
      (node (ref "X1") (pin "P$B8") (pinfunction "B8_P$B8") (pintype "passive"))
    )
    (net (code "38") (name "DMS33") (class "Default")
      (node (ref "U$3") (pin "P$5") (pinfunction "5_P$5") (pintype "passive"))
      (node (ref "X1") (pin "P$B7") (pinfunction "B7_P$B7") (pintype "passive"))
    )
    (net (code "39") (name "DMS41") (class "Default")
      (node (ref "U$4") (pin "P$1") (pinfunction "1_P$1") (pintype "passive"))
      (node (ref "X1") (pin "P$A1") (pinfunction "A1_P$A1") (pintype "passive"))
    )
    (net (code "40") (name "DMS42") (class "Default")
      (node (ref "U$4") (pin "P$3") (pinfunction "3_P$3") (pintype "passive"))
      (node (ref "X1") (pin "P$A2") (pinfunction "A2_P$A2") (pintype "passive"))
    )
    (net (code "41") (name "DMS43") (class "Default")
      (node (ref "U$4") (pin "P$5") (pinfunction "5_P$5") (pintype "passive"))
      (node (ref "X1") (pin "P$A3") (pinfunction "A3_P$A3") (pintype "passive"))
    )
    (net (code "42") (name "DMS51") (class "Default")
      (node (ref "U$5") (pin "P$1") (pinfunction "1_P$1") (pintype "passive"))
      (node (ref "X1") (pin "P$A4") (pinfunction "A4_P$A4") (pintype "passive"))
    )
    (net (code "43") (name "DMS52") (class "Default")
      (node (ref "U$5") (pin "P$3") (pinfunction "3_P$3") (pintype "passive"))
      (node (ref "X1") (pin "P$A5") (pinfunction "A5_P$A5") (pintype "passive"))
    )
    (net (code "44") (name "DMS53") (class "Default")
      (node (ref "U$5") (pin "P$5") (pinfunction "5_P$5") (pintype "passive"))
      (node (ref "X1") (pin "P$A6") (pinfunction "A6_P$A6") (pintype "passive"))
    )
    (net (code "45") (name "DMS61") (class "Default")
      (node (ref "U$6") (pin "P$1") (pinfunction "1_P$1") (pintype "passive"))
      (node (ref "X1") (pin "P$A7") (pinfunction "A7_P$A7") (pintype "passive"))
    )
    (net (code "46") (name "DMS62") (class "Default")
      (node (ref "U$6") (pin "P$3") (pinfunction "3_P$3") (pintype "passive"))
      (node (ref "X1") (pin "P$A8") (pinfunction "A8_P$A8") (pintype "passive"))
    )
    (net (code "47") (name "DMS63") (class "Default")
      (node (ref "U$6") (pin "P$5") (pinfunction "5_P$5") (pintype "passive"))
      (node (ref "X1") (pin "P$A9") (pinfunction "A9_P$A9") (pintype "passive"))
    )
    (net (code "48") (name "DMS_DIN") (class "Default")
      (node (ref "RN_DMS1") (pin "7") (pinfunction "2_7") (pintype "passive"))
      (node (ref "RN_DMS2") (pin "7") (pinfunction "2_7") (pintype "passive"))
      (node (ref "RN_DMS3") (pin "7") (pinfunction "2_7") (pintype "passive"))
      (node (ref "RN_DMS4") (pin "7") (pinfunction "2_7") (pintype "passive"))
      (node (ref "RN_DMS5") (pin "7") (pinfunction "2_7") (pintype "passive"))
      (node (ref "RN_DMS6") (pin "7") (pinfunction "2_7") (pintype "passive"))
    )
    (net (code "49") (name "DMS_DOUT") (class "Default")
      (node (ref "RN_DMS1") (pin "6") (pinfunction "2_6") (pintype "passive"))
      (node (ref "RN_DMS2") (pin "6") (pinfunction "2_6") (pintype "passive"))
      (node (ref "RN_DMS3") (pin "6") (pinfunction "2_6") (pintype "passive"))
      (node (ref "RN_DMS4") (pin "6") (pinfunction "2_6") (pintype "passive"))
      (node (ref "RN_DMS5") (pin "6") (pinfunction "2_6") (pintype "passive"))
      (node (ref "RN_DMS6") (pin "6") (pinfunction "2_6") (pintype "passive"))
    )
    (net (code "50") (name "DMS_SCLK") (class "Default")
      (node (ref "RN_DMS1") (pin "8") (pinfunction "2_8") (pintype "passive"))
      (node (ref "RN_DMS2") (pin "8") (pinfunction "2_8") (pintype "passive"))
      (node (ref "RN_DMS3") (pin "8") (pinfunction "2_8") (pintype "passive"))
      (node (ref "RN_DMS4") (pin "8") (pinfunction "2_8") (pintype "passive"))
      (node (ref "RN_DMS5") (pin "8") (pinfunction "2_8") (pintype "passive"))
      (node (ref "RN_DMS6") (pin "8") (pinfunction "2_8") (pintype "passive"))
    )
    (net (code "51") (name "EXP_IN") (class "Default")
      (node (ref "D5") (pin "C") (pinfunction "C_C") (pintype "passive"))
      (node (ref "U_MAX488") (pin "2") (pinfunction "RO_2") (pintype "output"))
      (node (ref "U_OPTO_3") (pin "1") (pinfunction "A1_1") (pintype "bidirectional"))
    )
    (net (code "52") (name "EXP_IN_N") (class "Default")
      (node (ref "R15") (pin "1") (pinfunction "1_1") (pintype "passive"))
      (node (ref "R17") (pin "2") (pinfunction "2_2") (pintype "passive"))
      (node (ref "U_MAX488") (pin "7") (pinfunction "B_7") (pintype "input"))
      (node (ref "X_RXSM-DAPI") (pin "P$B3") (pinfunction "B3_P$B3") (pintype "passive"))
    )
    (net (code "53") (name "EXP_IN_OPT") (class "Default")
      (node (ref "D10") (pin "C") (pinfunction "C_C") (pintype "passive"))
      (node (ref "R13") (pin "1") (pinfunction "1_1") (pintype "passive"))
      (node (ref "U_OPTO_3") (pin "8") (pinfunction "COL1_8") (pintype "input"))
      (node (ref "U_STM32F779") (pin "200") (pinfunction "PE0_200") (pintype "bidirectional"))
    )
    (net (code "54") (name "EXP_IN_P") (class "Default")
      (node (ref "R10") (pin "2") (pinfunction "2_2") (pintype "passive"))
      (node (ref "R16") (pin "2") (pinfunction "2_2") (pintype "passive"))
      (node (ref "U_MAX488") (pin "8") (pinfunction "A_8") (pintype "input"))
      (node (ref "X_RXSM-DAPI") (pin "P$B4") (pinfunction "B4_P$B4") (pintype "passive"))
    )
    (net (code "55") (name "EXP_OUT") (class "Default")
      (node (ref "D6") (pin "C") (pinfunction "C_C") (pintype "passive"))
      (node (ref "R14") (pin "1") (pinfunction "1_1") (pintype "passive"))
      (node (ref "U_MAX488") (pin "3") (pinfunction "DI_3") (pintype "input"))
      (node (ref "U_OPTO_3") (pin "6") (pinfunction "COL2_6") (pintype "input"))
    )
    (net (code "56") (name "EXP_OUT_N") (class "Default")
      (node (ref "U_MAX488") (pin "6") (pinfunction "Z_6") (pintype "output"))
      (node (ref "X_RXSM-DAPI") (pin "P$A3") (pinfunction "A3_P$A3") (pintype "passive"))
    )
    (net (code "57") (name "EXP_OUT_OPT") (class "Default")
      (node (ref "U_OPTO_3") (pin "3") (pinfunction "A2_3") (pintype "bidirectional"))
      (node (ref "U_STM32F779") (pin "201") (pinfunction "PE1_201") (pintype "bidirectional"))
    )
    (net (code "58") (name "EXP_OUT_P") (class "Default")
      (node (ref "U_MAX488") (pin "5") (pinfunction "Y_5") (pintype "output"))
      (node (ref "X_RXSM-DAPI") (pin "P$A4") (pinfunction "A4_P$A4") (pintype "passive"))
    )
    (net (code "59") (name "FL_1_CS1") (class "Default")
      (node (ref "U_S70FL01GS_1") (pin "7") (pinfunction "CS1_7") (pintype "bidirectional"))
      (node (ref "U_STM32F779") (pin "104") (pinfunction "PB12_104") (pintype "bidirectional"))
    )
    (net (code "60") (name "FL_1_CS2") (class "Default")
      (node (ref "U_S70FL01GS_1") (pin "6") (pinfunction "CS2_6") (pintype "bidirectional"))
      (node (ref "U_STM32F779") (pin "102") (pinfunction "PH12_102") (pintype "bidirectional"))
    )
    (net (code "61") (name "FL_1_HLD") (class "Default")
      (node (ref "U_S70FL01GS_1") (pin "1") (pinfunction "HOLD_1") (pintype "bidirectional"))
      (node (ref "U_STM32F779") (pin "99") (pinfunction "PH9_99") (pintype "bidirectional"))
    )
    (net (code "62") (name "FL_1_RES") (class "Default")
      (node (ref "U_S70FL01GS_1") (pin "3") (pinfunction "RESET_3") (pintype "bidirectional"))
      (node (ref "U_STM32F779") (pin "101") (pinfunction "PH11_101") (pintype "bidirectional"))
    )
    (net (code "63") (name "FL_1_WP") (class "Default")
      (node (ref "U_S70FL01GS_1") (pin "9") (pinfunction "WP_9") (pintype "bidirectional"))
      (node (ref "U_STM32F779") (pin "100") (pinfunction "PH10_100") (pintype "bidirectional"))
    )
    (net (code "64") (name "FL_2_CS1") (class "Default")
      (node (ref "U_S70FL01GS_2") (pin "7") (pinfunction "CS1_7") (pintype "bidirectional"))
      (node (ref "U_STM32F779") (pin "112") (pinfunction "PD12_112") (pintype "bidirectional"))
    )
    (net (code "65") (name "FL_2_CS2") (class "Default")
      (node (ref "U_S70FL01GS_2") (pin "6") (pinfunction "CS2_6") (pintype "bidirectional"))
      (node (ref "U_STM32F779") (pin "111") (pinfunction "PD11_111") (pintype "bidirectional"))
    )
    (net (code "66") (name "FL_2_HLD") (class "Default")
      (node (ref "U_S70FL01GS_2") (pin "1") (pinfunction "HOLD_1") (pintype "bidirectional"))
      (node (ref "U_STM32F779") (pin "109") (pinfunction "PD9_109") (pintype "bidirectional"))
    )
    (net (code "67") (name "FL_2_RES") (class "Default")
      (node (ref "U_S70FL01GS_2") (pin "3") (pinfunction "RESET_3") (pintype "bidirectional"))
      (node (ref "U_STM32F779") (pin "110") (pinfunction "PD10_110") (pintype "bidirectional"))
    )
    (net (code "68") (name "FL_2_WP") (class "Default")
      (node (ref "U_S70FL01GS_2") (pin "9") (pinfunction "WP_9") (pintype "bidirectional"))
      (node (ref "U_STM32F779") (pin "108") (pinfunction "PD8_108") (pintype "bidirectional"))
    )
    (net (code "69") (name "GND") (class "Default")
      (node (ref "C1") (pin "2") (pinfunction "2_2") (pintype "passive"))
      (node (ref "C10") (pin "2") (pinfunction "2_2") (pintype "passive"))
      (node (ref "C11") (pin "2") (pinfunction "2_2") (pintype "passive"))
      (node (ref "C12") (pin "1") (pinfunction "1_1") (pintype "passive"))
      (node (ref "C14") (pin "2") (pinfunction "2_2") (pintype "passive"))
      (node (ref "C15") (pin "2") (pinfunction "2_2") (pintype "passive"))
      (node (ref "C16") (pin "1") (pinfunction "1_1") (pintype "passive"))
      (node (ref "C17") (pin "1") (pinfunction "1_1") (pintype "passive"))
      (node (ref "C18") (pin "2") (pinfunction "2_2") (pintype "passive"))
      (node (ref "C19") (pin "2") (pinfunction "2_2") (pintype "passive"))
      (node (ref "C2") (pin "2") (pinfunction "2_2") (pintype "passive"))
      (node (ref "C20") (pin "2") (pinfunction "2_2") (pintype "passive"))
      (node (ref "C21") (pin "1") (pinfunction "1_1") (pintype "passive"))
      (node (ref "C23") (pin "2") (pinfunction "2_2") (pintype "passive"))
      (node (ref "C24") (pin "2") (pinfunction "2_2") (pintype "passive"))
      (node (ref "C25") (pin "2") (pinfunction "2_2") (pintype "passive"))
      (node (ref "C26") (pin "2") (pinfunction "2_2") (pintype "passive"))
      (node (ref "C27") (pin "1") (pinfunction "1_1") (pintype "passive"))
      (node (ref "C28") (pin "2") (pinfunction "2_2") (pintype "passive"))
      (node (ref "C29") (pin "2") (pinfunction "2_2") (pintype "passive"))
      (node (ref "C3") (pin "2") (pinfunction "2_2") (pintype "passive"))
      (node (ref "C30") (pin "2") (pinfunction "2_2") (pintype "passive"))
      (node (ref "C31") (pin "2") (pinfunction "2_2") (pintype "passive"))
      (node (ref "C32") (pin "2") (pinfunction "2_2") (pintype "passive"))
      (node (ref "C33") (pin "2") (pinfunction "2_2") (pintype "passive"))
      (node (ref "C35") (pin "1") (pinfunction "1_1") (pintype "passive"))
      (node (ref "C36") (pin "1") (pinfunction "1_1") (pintype "passive"))
      (node (ref "C37") (pin "1") (pinfunction "1_1") (pintype "passive"))
      (node (ref "C39") (pin "-") (pinfunction "-_-") (pintype "passive"))
      (node (ref "C4") (pin "2") (pinfunction "2_2") (pintype "passive"))
      (node (ref "C40") (pin "-") (pinfunction "-_-") (pintype "passive"))
      (node (ref "C41") (pin "-") (pinfunction "-_-") (pintype "passive"))
      (node (ref "C46") (pin "2") (pinfunction "2_2") (pintype "passive"))
      (node (ref "C47") (pin "2") (pinfunction "2_2") (pintype "passive"))
      (node (ref "C48") (pin "2") (pinfunction "2_2") (pintype "passive"))
      (node (ref "C49") (pin "2") (pinfunction "2_2") (pintype "passive"))
      (node (ref "C5") (pin "2") (pinfunction "2_2") (pintype "passive"))
      (node (ref "C50") (pin "1") (pinfunction "1_1") (pintype "passive"))
      (node (ref "C52") (pin "1") (pinfunction "1_1") (pintype "passive"))
      (node (ref "C53") (pin "2") (pinfunction "2_2") (pintype "passive"))
      (node (ref "C54") (pin "2") (pinfunction "2_2") (pintype "passive"))
      (node (ref "C55") (pin "2") (pinfunction "2_2") (pintype "passive"))
      (node (ref "C56") (pin "2") (pinfunction "2_2") (pintype "passive"))
      (node (ref "C57") (pin "1") (pinfunction "1_1") (pintype "passive"))
      (node (ref "C59") (pin "2") (pinfunction "2_2") (pintype "passive"))
      (node (ref "C6") (pin "1") (pinfunction "1_1") (pintype "passive"))
      (node (ref "C8") (pin "2") (pinfunction "2_2") (pintype "passive"))
      (node (ref "C9") (pin "2") (pinfunction "2_2") (pintype "passive"))
      (node (ref "C_AVDD_PT1") (pin "2") (pinfunction "2_2") (pintype "passive"))
      (node (ref "C_AVDD_PT2") (pin "2") (pinfunction "2_2") (pintype "passive"))
      (node (ref "C_AVDD_PT3") (pin "2") (pinfunction "2_2") (pintype "passive"))
      (node (ref "C_DVDD_PT1") (pin "2") (pinfunction "2_2") (pintype "passive"))
      (node (ref "C_DVDD_PT2") (pin "2") (pinfunction "2_2") (pintype "passive"))
      (node (ref "C_DVDD_PT3") (pin "2") (pinfunction "2_2") (pintype "passive"))
      (node (ref "C_ICM1_PT1") (pin "1") (pinfunction "1_1") (pintype "passive"))
      (node (ref "C_ICM1_PT2") (pin "1") (pinfunction "1_1") (pintype "passive"))
      (node (ref "C_ICM1_PT3") (pin "1") (pinfunction "1_1") (pintype "passive"))
      (node (ref "C_ICM2_PT1") (pin "2") (pinfunction "2_2") (pintype "passive"))
      (node (ref "C_ICM2_PT2") (pin "2") (pinfunction "2_2") (pintype "passive"))
      (node (ref "C_ICM2_PT3") (pin "2") (pinfunction "2_2") (pintype "passive"))
      (node (ref "C_RCM1_PT1") (pin "1") (pinfunction "1_1") (pintype "passive"))
      (node (ref "C_RCM1_PT2") (pin "1") (pinfunction "1_1") (pintype "passive"))
      (node (ref "C_RCM1_PT3") (pin "1") (pinfunction "1_1") (pintype "passive"))
      (node (ref "C_RCM2_PT1") (pin "2") (pinfunction "2_2") (pintype "passive"))
      (node (ref "C_RCM2_PT2") (pin "2") (pinfunction "2_2") (pintype "passive"))
      (node (ref "C_RCM2_PT3") (pin "2") (pinfunction "2_2") (pintype "passive"))
      (node (ref "C_VREF_PT1") (pin "2") (pinfunction "2_2") (pintype "passive"))
      (node (ref "C_VREF_PT2") (pin "2") (pinfunction "2_2") (pintype "passive"))
      (node (ref "C_VREF_PT3") (pin "2") (pinfunction "2_2") (pintype "passive"))
      (node (ref "D1") (pin "A") (pinfunction "A_A") (pintype "passive"))
      (node (ref "D10") (pin "A") (pinfunction "A_A") (pintype "passive"))
      (node (ref "D11") (pin "A") (pinfunction "A_A") (pintype "passive"))
      (node (ref "D12") (pin "A") (pinfunction "A_A") (pintype "passive"))
      (node (ref "D2") (pin "A") (pinfunction "A_A") (pintype "passive"))
      (node (ref "D3") (pin "A") (pinfunction "A_A") (pintype "passive"))
      (node (ref "D4") (pin "A") (pinfunction "A_A") (pintype "passive"))
      (node (ref "D7") (pin "A") (pinfunction "A_A") (pintype "passive"))
      (node (ref "D8") (pin "A") (pinfunction "A_A") (pintype "passive"))
      (node (ref "D9") (pin "A") (pinfunction "A_A") (pintype "passive"))
      (node (ref "JP_MS") (pin "1") (pinfunction "1_1") (pintype "passive"))
      (node (ref "LED1") (pin "C") (pinfunction "C_C") (pintype "passive"))
      (node (ref "LED2") (pin "C") (pinfunction "C_C") (pintype "passive"))
      (node (ref "LED3") (pin "C") (pinfunction "C_C") (pintype "passive"))
      (node (ref "LED4") (pin "C") (pinfunction "C_C") (pintype "passive"))
      (node (ref "LED5") (pin "C") (pinfunction "C_C") (pintype "passive"))
      (node (ref "LED6") (pin "C") (pinfunction "C_C") (pintype "passive"))
      (node (ref "R12") (pin "1") (pinfunction "1_1") (pintype "passive"))
      (node (ref "R23") (pin "1") (pinfunction "1_1") (pintype "passive"))
      (node (ref "R27") (pin "2") (pinfunction "2_2") (pintype "passive"))
      (node (ref "R35") (pin "2") (pinfunction "2_2") (pintype "passive"))
      (node (ref "R42") (pin "2") (pinfunction "2_2") (pintype "passive"))
      (node (ref "R49") (pin "2") (pinfunction "2_2") (pintype "passive"))
      (node (ref "R56") (pin "2") (pinfunction "2_2") (pintype "passive"))
      (node (ref "R63") (pin "2") (pinfunction "2_2") (pintype "passive"))
      (node (ref "R7") (pin "2") (pinfunction "2_2") (pintype "passive"))
      (node (ref "RN_B_PT1") (pin "4") (pinfunction "1_4") (pintype "passive"))
      (node (ref "RN_B_PT1") (pin "5") (pinfunction "2_5") (pintype "passive"))
      (node (ref "RN_B_PT2") (pin "4") (pinfunction "1_4") (pintype "passive"))
      (node (ref "RN_B_PT2") (pin "5") (pinfunction "2_5") (pintype "passive"))
      (node (ref "RN_B_PT3") (pin "4") (pinfunction "1_4") (pintype "passive"))
      (node (ref "RN_B_PT3") (pin "5") (pinfunction "2_5") (pintype "passive"))
      (node (ref "R_R2_PT1") (pin "2") (pinfunction "2_2") (pintype "passive"))
      (node (ref "R_R2_PT2") (pin "2") (pinfunction "2_2") (pintype "passive"))
      (node (ref "R_R2_PT3") (pin "2") (pinfunction "2_2") (pintype "passive"))
      (node (ref "R_REF_PT1") (pin "1") (pinfunction "1_1") (pintype "passive"))
      (node (ref "R_REF_PT2") (pin "1") (pinfunction "1_1") (pintype "passive"))
      (node (ref "R_REF_PT3") (pin "1") (pinfunction "1_1") (pintype "passive"))
      (node (ref "SJ_MS") (pin "1") (pinfunction "1_1") (pintype "passive"))
      (node (ref "U$1") (pin "P$6") (pinfunction "6_P$6") (pintype "passive"))
      (node (ref "U$2") (pin "P$6") (pinfunction "6_P$6") (pintype "passive"))
      (node (ref "U$3") (pin "P$6") (pinfunction "6_P$6") (pintype "passive"))
      (node (ref "U$4") (pin "P$6") (pinfunction "6_P$6") (pintype "passive"))
      (node (ref "U$5") (pin "P$6") (pinfunction "6_P$6") (pintype "passive"))
      (node (ref "U$6") (pin "P$6") (pinfunction "6_P$6") (pintype "passive"))
      (node (ref "U_ADC_DMS1") (pin "13") (pinfunction "AVSS_13") (pintype "bidirectional"))
      (node (ref "U_ADC_DMS1") (pin "2") (pinfunction "DGND/DSS_2") (pintype "bidirectional"))
      (node (ref "U_ADC_DMS1") (pin "3") (pinfunction "CLK_3") (pintype "bidirectional"))
      (node (ref "U_ADC_DMS1") (pin "8") (pinfunction "VREFCOM_8") (pintype "bidirectional"))
      (node (ref "U_ADC_DMS2") (pin "13") (pinfunction "AVSS_13") (pintype "bidirectional"))
      (node (ref "U_ADC_DMS2") (pin "2") (pinfunction "DGND/DSS_2") (pintype "bidirectional"))
      (node (ref "U_ADC_DMS2") (pin "3") (pinfunction "CLK_3") (pintype "bidirectional"))
      (node (ref "U_ADC_DMS2") (pin "8") (pinfunction "VREFCOM_8") (pintype "bidirectional"))
      (node (ref "U_ADC_DMS3") (pin "13") (pinfunction "AVSS_13") (pintype "bidirectional"))
      (node (ref "U_ADC_DMS3") (pin "2") (pinfunction "DGND/DSS_2") (pintype "bidirectional"))
      (node (ref "U_ADC_DMS3") (pin "3") (pinfunction "CLK_3") (pintype "bidirectional"))
      (node (ref "U_ADC_DMS3") (pin "8") (pinfunction "VREFCOM_8") (pintype "bidirectional"))
      (node (ref "U_ADC_DMS4") (pin "13") (pinfunction "AVSS_13") (pintype "bidirectional"))
      (node (ref "U_ADC_DMS4") (pin "2") (pinfunction "DGND/DSS_2") (pintype "bidirectional"))
      (node (ref "U_ADC_DMS4") (pin "3") (pinfunction "CLK_3") (pintype "bidirectional"))
      (node (ref "U_ADC_DMS4") (pin "8") (pinfunction "VREFCOM_8") (pintype "bidirectional"))
      (node (ref "U_ADC_DMS5") (pin "13") (pinfunction "AVSS_13") (pintype "bidirectional"))
      (node (ref "U_ADC_DMS5") (pin "2") (pinfunction "DGND/DSS_2") (pintype "bidirectional"))
      (node (ref "U_ADC_DMS5") (pin "3") (pinfunction "CLK_3") (pintype "bidirectional"))
      (node (ref "U_ADC_DMS5") (pin "8") (pinfunction "VREFCOM_8") (pintype "bidirectional"))
      (node (ref "U_ADC_DMS6") (pin "13") (pinfunction "AVSS_13") (pintype "bidirectional"))
      (node (ref "U_ADC_DMS6") (pin "2") (pinfunction "DGND/DSS_2") (pintype "bidirectional"))
      (node (ref "U_ADC_DMS6") (pin "3") (pinfunction "CLK_3") (pintype "bidirectional"))
      (node (ref "U_ADC_DMS6") (pin "8") (pinfunction "VREFCOM_8") (pintype "bidirectional"))
      (node (ref "U_ADC_PT1") (pin "13") (pinfunction "AVSS_13") (pintype "bidirectional"))
      (node (ref "U_ADC_PT1") (pin "2") (pinfunction "DGND/DSS_2") (pintype "bidirectional"))
      (node (ref "U_ADC_PT1") (pin "3") (pinfunction "CLK_3") (pintype "bidirectional"))
      (node (ref "U_ADC_PT1") (pin "8") (pinfunction "VREFCOM_8") (pintype "bidirectional"))
      (node (ref "U_ADC_PT2") (pin "13") (pinfunction "AVSS_13") (pintype "bidirectional"))
      (node (ref "U_ADC_PT2") (pin "2") (pinfunction "DGND/DSS_2") (pintype "bidirectional"))
      (node (ref "U_ADC_PT2") (pin "3") (pinfunction "CLK_3") (pintype "bidirectional"))
      (node (ref "U_ADC_PT2") (pin "8") (pinfunction "VREFCOM_8") (pintype "bidirectional"))
      (node (ref "U_ADC_PT3") (pin "13") (pinfunction "AVSS_13") (pintype "bidirectional"))
      (node (ref "U_ADC_PT3") (pin "2") (pinfunction "DGND/DSS_2") (pintype "bidirectional"))
      (node (ref "U_ADC_PT3") (pin "3") (pinfunction "CLK_3") (pintype "bidirectional"))
      (node (ref "U_ADC_PT3") (pin "8") (pinfunction "VREFCOM_8") (pintype "bidirectional"))
      (node (ref "U_ADR366_3") (pin "2") (pinfunction "GND_2") (pintype "power_in"))
      (node (ref "U_CH340G") (pin "1") (pinfunction "GND_1") (pintype "bidirectional"))
      (node (ref "U_LT1528") (pin "3") (pinfunction "GND_3") (pintype "bidirectional"))
      (node (ref "U_LT1528") (pin "6") (pinfunction "GND_6") (pintype "bidirectional"))
      (node (ref "U_OPTO_1") (pin "5") (pinfunction "EMT2_5") (pintype "output"))
      (node (ref "U_OPTO_1") (pin "7") (pinfunction "EMT1_7") (pintype "output"))
      (node (ref "U_OPTO_2") (pin "5") (pinfunction "EMT2_5") (pintype "output"))
      (node (ref "U_OPTO_2") (pin "7") (pinfunction "EMT1_7") (pintype "output"))
      (node (ref "U_OPTO_3") (pin "7") (pinfunction "EMT1_7") (pintype "output"))
      (node (ref "U_S70FL01GS_1") (pin "10") (pinfunction "VSS_10") (pintype "bidirectional"))
      (node (ref "U_S70FL01GS_2") (pin "10") (pinfunction "VSS_10") (pintype "bidirectional"))
      (node (ref "U_STM32F779") (pin "114") (pinfunction "VSS_114") (pintype "bidirectional"))
      (node (ref "U_STM32F779") (pin "122") (pinfunction "VSSDSI_122") (pintype "bidirectional"))
      (node (ref "U_STM32F779") (pin "128") (pinfunction "VSSDSI2_128") (pintype "bidirectional"))
      (node (ref "U_STM32F779") (pin "136") (pinfunction "VSS_136") (pintype "bidirectional"))
      (node (ref "U_STM32F779") (pin "14") (pinfunction "VSS_14") (pintype "bidirectional"))
      (node (ref "U_STM32F779") (pin "149") (pinfunction "VSS_149") (pintype "bidirectional"))
      (node (ref "U_STM32F779") (pin "170") (pinfunction "VSS_170") (pintype "bidirectional"))
      (node (ref "U_STM32F779") (pin "184") (pinfunction "VSS_184") (pintype "bidirectional"))
      (node (ref "U_STM32F779") (pin "202") (pinfunction "VSS_202") (pintype "bidirectional"))
      (node (ref "U_STM32F779") (pin "25") (pinfunction "VSS_25") (pintype "bidirectional"))
      (node (ref "U_STM32F779") (pin "40") (pinfunction "VSSA_40") (pintype "bidirectional"))
      (node (ref "U_STM32F779") (pin "51") (pinfunction "VSS_51") (pintype "bidirectional"))
      (node (ref "U_STM32F779") (pin "60") (pinfunction "VSS_60") (pintype "bidirectional"))
      (node (ref "U_STM32F779") (pin "72") (pinfunction "VSS_72") (pintype "bidirectional"))
      (node (ref "U_STM32F779") (pin "82") (pinfunction "VSS_82") (pintype "bidirectional"))
      (node (ref "U_STM32F779") (pin "93") (pinfunction "VSS_93") (pintype "bidirectional"))
      (node (ref "U_TRACODCDC") (pin "5") (pinfunction "-VOUT_5") (pintype "passive"))
      (node (ref "X_MIRROR") (pin "P$A8") (pinfunction "A8_P$A8") (pintype "passive"))
      (node (ref "X_MIRROR") (pin "P$B10") (pinfunction "B10_P$B10") (pintype "passive"))
      (node (ref "X_MIRROR") (pin "P$B11") (pinfunction "B11_P$B11") (pintype "passive"))
      (node (ref "X_MIRROR") (pin "P$B12") (pinfunction "B12_P$B12") (pintype "passive"))
      (node (ref "X_MIRROR") (pin "P$B13") (pinfunction "B13_P$B13") (pintype "passive"))
      (node (ref "X_MIRROR") (pin "P$B8") (pinfunction "B8_P$B8") (pintype "passive"))
      (node (ref "X_MIRROR") (pin "P$B9") (pinfunction "B9_P$B9") (pintype "passive"))
      (node (ref "X_MIRROR1") (pin "P$A6") (pinfunction "A6_P$A6") (pintype "passive"))
      (node (ref "X_MIRROR1") (pin "P$B1") (pinfunction "B1_P$B1") (pintype "passive"))
      (node (ref "X_MIRROR1") (pin "P$B2") (pinfunction "B2_P$B2") (pintype "passive"))
      (node (ref "X_MIRROR1") (pin "P$B3") (pinfunction "B3_P$B3") (pintype "passive"))
      (node (ref "X_MIRROR1") (pin "P$B4") (pinfunction "B4_P$B4") (pintype "passive"))
      (node (ref "X_MIRROR1") (pin "P$B5") (pinfunction "B5_P$B5") (pintype "passive"))
      (node (ref "X_MIRROR1") (pin "P$B6") (pinfunction "B6_P$B6") (pintype "passive"))
      (node (ref "X_PROG") (pin "10") (pinfunction "10_10") (pintype "passive"))
      (node (ref "X_PROG") (pin "12") (pinfunction "12_12") (pintype "passive"))
      (node (ref "X_PROG") (pin "14") (pinfunction "14_14") (pintype "passive"))
      (node (ref "X_PROG") (pin "16") (pinfunction "16_16") (pintype "passive"))
      (node (ref "X_PROG") (pin "18") (pinfunction "18_18") (pintype "passive"))
      (node (ref "X_PROG") (pin "20") (pinfunction "20_20") (pintype "passive"))
      (node (ref "X_PROG") (pin "4") (pinfunction "4_4") (pintype "passive"))
      (node (ref "X_PROG") (pin "6") (pinfunction "6_6") (pintype "passive"))
      (node (ref "X_PROG") (pin "8") (pinfunction "8_8") (pintype "passive"))
      (node (ref "X_PT") (pin "P$BL1") (pinfunction "CASE_P$BL1") (pintype "passive"))
      (node (ref "X_PT") (pin "P$BL2") (pinfunction "CASE_P$BL2") (pintype "passive"))
      (node (ref "X_PT") (pin "P$BL3") (pinfunction "CASE_P$BL3") (pintype "passive"))
      (node (ref "X_PT") (pin "P$BL4") (pinfunction "CASE_P$BL4") (pintype "passive"))
      (node (ref "X_RXSM-DAPI") (pin "P$A10") (pinfunction "A10_P$A10") (pintype "passive"))
    )
    (net (code "70") (name "INTERSPU_RX") (class "Default")
      (node (ref "D11") (pin "C") (pinfunction "C_C") (pintype "passive"))
      (node (ref "U_STM32F779") (pin "166") (pinfunction "PD2_166") (pintype "bidirectional"))
      (node (ref "X_MIRROR") (pin "P$A9") (pinfunction "A9_P$A9") (pintype "passive"))
      (node (ref "X_MIRROR1") (pin "P$A4") (pinfunction "A4_P$A4") (pintype "passive"))
    )
    (net (code "71") (name "INTERSPU_TX") (class "Default")
      (node (ref "D12") (pin "C") (pinfunction "C_C") (pintype "passive"))
      (node (ref "U_STM32F779") (pin "163") (pinfunction "PC12_163") (pintype "bidirectional"))
      (node (ref "X_MIRROR") (pin "P$A10") (pinfunction "A10_P$A10") (pintype "passive"))
      (node (ref "X_MIRROR1") (pin "P$A5") (pinfunction "A5_P$A5") (pintype "passive"))
    )
    (net (code "72") (name "LED_1") (class "Default")
      (node (ref "RN10") (pin "1") (pinfunction "1_1") (pintype "passive"))
      (node (ref "U_STM32F779") (pin "24") (pinfunction "PF5_24") (pintype "bidirectional"))
    )
    (net (code "73") (name "LED_2") (class "Default")
      (node (ref "RN10") (pin "2") (pinfunction "1_2") (pintype "passive"))
      (node (ref "U_STM32F779") (pin "23") (pinfunction "PF4_23") (pintype "bidirectional"))
    )
    (net (code "74") (name "LED_3") (class "Default")
      (node (ref "RN10") (pin "3") (pinfunction "1_3") (pintype "passive"))
      (node (ref "U_STM32F779") (pin "22") (pinfunction "PF3_22") (pintype "bidirectional"))
    )
    (net (code "75") (name "LED_4") (class "Default")
      (node (ref "RN10") (pin "4") (pinfunction "1_4") (pintype "passive"))
      (node (ref "U_STM32F779") (pin "21") (pinfunction "PI14_21") (pintype "bidirectional"))
    )
    (net (code "76") (name "LO") (class "Default")
      (node (ref "U_OPTO_2") (pin "2") (pinfunction "C1_2") (pintype "bidirectional"))
      (node (ref "X_MIRROR") (pin "P$A5") (pinfunction "A5_P$A5") (pintype "passive"))
      (node (ref "X_MIRROR1") (pin "P$A9") (pinfunction "A9_P$A9") (pintype "passive"))
      (node (ref "X_RXSM-DAPI") (pin "P$A5") (pinfunction "A5_P$A5") (pintype "passive"))
    )
    (net (code "77") (name "LO_OPT") (class "Default")
      (node (ref "D7") (pin "C") (pinfunction "C_C") (pintype "passive"))
      (node (ref "RN12") (pin "6") (pinfunction "2_6") (pintype "passive"))
      (node (ref "U_OPTO_2") (pin "8") (pinfunction "COL1_8") (pintype "input"))
      (node (ref "U_STM32F779") (pin "208") (pinfunction "PI7_208") (pintype "bidirectional"))
    )
    (net (code "78") (name "MS_SEL") (class "Default")
      (node (ref "JP_MS") (pin "2") (pinfunction "2_2") (pintype "passive"))
      (node (ref "R29") (pin "1") (pinfunction "1_1") (pintype "passive"))
      (node (ref "SJ_MS") (pin "2") (pinfunction "2_2") (pintype "passive"))
      (node (ref "U_STM32F779") (pin "129") (pinfunction "PG2_129") (pintype "bidirectional"))
    )
    (net (code "79") (name "N$127") (class "Default")
      (node (ref "C47") (pin "1") (pinfunction "1_1") (pintype "passive"))
      (node (ref "R50") (pin "1") (pinfunction "1_1") (pintype "passive"))
      (node (ref "U_ADC_DMS5") (pin "1") (pinfunction "DVDD_1") (pintype "bidirectional"))
    )
    (net (code "80") (name "N$141") (class "Default")
      (node (ref "C54") (pin "1") (pinfunction "1_1") (pintype "passive"))
      (node (ref "R57") (pin "1") (pinfunction "1_1") (pintype "passive"))
      (node (ref "U_ADC_DMS6") (pin "1") (pinfunction "DVDD_1") (pintype "bidirectional"))
    )
    (net (code "81") (name "NRST") (class "Default")
      (node (ref "C18") (pin "1") (pinfunction "1_1") (pintype "passive"))
      (node (ref "JP1") (pin "1") (pinfunction "1_1") (pintype "passive"))
      (node (ref "R26") (pin "1") (pinfunction "1_1") (pintype "passive"))
      (node (ref "U_STM32F779") (pin "34") (pinfunction "NRST_34") (pintype "bidirectional"))
      (node (ref "X_PROG") (pin "15") (pinfunction "15_15") (pintype "passive"))
    )
    (net (code "82") (name "Net-(C44-Pad1)") (class "Default")
      (node (ref "C44") (pin "1") (pinfunction "1_1") (pintype "passive"))
      (node (ref "R10") (pin "1") (pinfunction "1_1") (pintype "passive"))
      (node (ref "R15") (pin "2") (pinfunction "2_2") (pintype "passive"))
    )
    (net (code "83") (name "Net-(LED5-PadA)") (class "Default")
      (node (ref "LED5") (pin "A") (pinfunction "A_A") (pintype "passive"))
      (node (ref "R18") (pin "1") (pinfunction "1_1") (pintype "passive"))
    )
    (net (code "84") (name "Net-(LED6-PadA)") (class "Default")
      (node (ref "LED6") (pin "A") (pinfunction "A_A") (pintype "passive"))
      (node (ref "R19") (pin "1") (pinfunction "1_1") (pintype "passive"))
    )
    (net (code "85") (name "Net-(LED7-PadA)") (class "Default")
      (node (ref "LED7") (pin "A") (pinfunction "A_A") (pintype "passive"))
      (node (ref "R20") (pin "1") (pinfunction "1_1") (pintype "passive"))
    )
    (net (code "86") (name "Net-(LED8-PadA)") (class "Default")
      (node (ref "LED8") (pin "A") (pinfunction "A_A") (pintype "passive"))
      (node (ref "R21") (pin "1") (pinfunction "1_1") (pintype "passive"))
    )
    (net (code "87") (name "Net-(R5-Pad2)") (class "Default")
      (node (ref "R5") (pin "2") (pinfunction "2_2") (pintype "passive"))
      (node (ref "R6") (pin "1") (pinfunction "1_1") (pintype "passive"))
      (node (ref "R7") (pin "1") (pinfunction "1_1") (pintype "passive"))
    )
    (net (code "88") (name "Net-(R22-Pad2)") (class "Default")
      (node (ref "R22") (pin "2") (pinfunction "2_2") (pintype "passive"))
      (node (ref "R24") (pin "1") (pinfunction "1_1") (pintype "passive"))
      (node (ref "R25") (pin "2") (pinfunction "2_2") (pintype "passive"))
    )
    (net (code "89") (name "Net-(R23-Pad2)") (class "Default")
      (node (ref "R23") (pin "2") (pinfunction "2_2") (pintype "passive"))
      (node (ref "R25") (pin "1") (pinfunction "1_1") (pintype "passive"))
    )
    (net (code "90") (name "Net-(R33-Pad2)") (class "Default")
      (node (ref "R33") (pin "2") (pinfunction "2_2") (pintype "passive"))
      (node (ref "R34") (pin "1") (pinfunction "1_1") (pintype "passive"))
      (node (ref "R35") (pin "1") (pinfunction "1_1") (pintype "passive"))
    )
    (net (code "91") (name "Net-(R40-Pad2)") (class "Default")
      (node (ref "R40") (pin "2") (pinfunction "2_2") (pintype "passive"))
      (node (ref "R41") (pin "1") (pinfunction "1_1") (pintype "passive"))
      (node (ref "R42") (pin "1") (pinfunction "1_1") (pintype "passive"))
    )
    (net (code "92") (name "Net-(R47-Pad2)") (class "Default")
      (node (ref "R47") (pin "2") (pinfunction "2_2") (pintype "passive"))
      (node (ref "R48") (pin "1") (pinfunction "1_1") (pintype "passive"))
      (node (ref "R49") (pin "1") (pinfunction "1_1") (pintype "passive"))
    )
    (net (code "93") (name "Net-(R54-Pad2)") (class "Default")
      (node (ref "R54") (pin "2") (pinfunction "2_2") (pintype "passive"))
      (node (ref "R55") (pin "1") (pinfunction "1_1") (pintype "passive"))
      (node (ref "R56") (pin "1") (pinfunction "1_1") (pintype "passive"))
    )
    (net (code "94") (name "Net-(R61-Pad2)") (class "Default")
      (node (ref "R61") (pin "2") (pinfunction "2_2") (pintype "passive"))
      (node (ref "R62") (pin "1") (pinfunction "1_1") (pintype "passive"))
      (node (ref "R63") (pin "1") (pinfunction "1_1") (pintype "passive"))
    )
    (net (code "95") (name "Net-(RN10A-2)") (class "Default")
      (node (ref "LED1") (pin "A") (pinfunction "A_A") (pintype "passive"))
      (node (ref "RN10") (pin "8") (pinfunction "2_8") (pintype "passive"))
    )
    (net (code "96") (name "Net-(RN10B-2)") (class "Default")
      (node (ref "LED2") (pin "A") (pinfunction "A_A") (pintype "passive"))
      (node (ref "RN10") (pin "7") (pinfunction "2_7") (pintype "passive"))
    )
    (net (code "97") (name "Net-(RN10C-2)") (class "Default")
      (node (ref "LED3") (pin "A") (pinfunction "A_A") (pintype "passive"))
      (node (ref "RN10") (pin "6") (pinfunction "2_6") (pintype "passive"))
    )
    (net (code "98") (name "Net-(RN10D-2)") (class "Default")
      (node (ref "LED4") (pin "A") (pinfunction "A_A") (pintype "passive"))
      (node (ref "RN10") (pin "5") (pinfunction "2_5") (pintype "passive"))
    )
    (net (code "99") (name "Net-(RN11A-2)") (class "Default")
      (node (ref "RN11") (pin "8") (pinfunction "2_8") (pintype "passive"))
      (node (ref "U_OPTO_2") (pin "1") (pinfunction "A1_1") (pintype "bidirectional"))
    )
    (net (code "100") (name "Net-(RN11B-2)") (class "Default")
      (node (ref "RN11") (pin "7") (pinfunction "2_7") (pintype "passive"))
      (node (ref "U_OPTO_2") (pin "3") (pinfunction "A2_3") (pintype "bidirectional"))
    )
    (net (code "101") (name "Net-(RN11C-2)") (class "Default")
      (node (ref "RN11") (pin "6") (pinfunction "2_6") (pintype "passive"))
      (node (ref "U_OPTO_1") (pin "1") (pinfunction "A1_1") (pintype "bidirectional"))
    )
    (net (code "102") (name "Net-(RN11D-2)") (class "Default")
      (node (ref "RN11") (pin "5") (pinfunction "2_5") (pintype "passive"))
      (node (ref "U_OPTO_1") (pin "3") (pinfunction "A2_3") (pintype "bidirectional"))
    )
    (net (code "103") (name "Net-(RN12D-2)") (class "Default")
      (node (ref "RN12") (pin "5") (pinfunction "2_5") (pintype "passive"))
      (node (ref "U_OPTO_2") (pin "6") (pinfunction "COL2_6") (pintype "input"))
    )
    (net (code "104") (name "Net-(RN_A_PT1B-1)") (class "Default")
      (node (ref "RN_A_PT1") (pin "2") (pinfunction "1_2") (pintype "passive"))
      (node (ref "U_ADC_PT1") (pin "20") (pinfunction "SCLK_20") (pintype "bidirectional"))
    )
    (net (code "105") (name "Net-(RN_A_PT1C-1)") (class "Default")
      (node (ref "RN_A_PT1") (pin "3") (pinfunction "1_3") (pintype "passive"))
      (node (ref "U_ADC_PT1") (pin "19") (pinfunction "DIN_19") (pintype "bidirectional"))
    )
    (net (code "106") (name "Net-(RN_A_PT1D-1)") (class "Default")
      (node (ref "RN_A_PT1") (pin "4") (pinfunction "1_4") (pintype "passive"))
      (node (ref "U_ADC_PT1") (pin "18") (pinfunction "DOUT/~{DRDY}_18") (pintype "bidirectional"))
    )
    (net (code "107") (name "Net-(RN_A_PT2B-1)") (class "Default")
      (node (ref "RN_A_PT2") (pin "2") (pinfunction "1_2") (pintype "passive"))
      (node (ref "U_ADC_PT2") (pin "20") (pinfunction "SCLK_20") (pintype "bidirectional"))
    )
    (net (code "108") (name "Net-(RN_A_PT2C-1)") (class "Default")
      (node (ref "RN_A_PT2") (pin "3") (pinfunction "1_3") (pintype "passive"))
      (node (ref "U_ADC_PT2") (pin "19") (pinfunction "DIN_19") (pintype "bidirectional"))
    )
    (net (code "109") (name "Net-(RN_A_PT2D-1)") (class "Default")
      (node (ref "RN_A_PT2") (pin "4") (pinfunction "1_4") (pintype "passive"))
      (node (ref "U_ADC_PT2") (pin "18") (pinfunction "DOUT/~{DRDY}_18") (pintype "bidirectional"))
    )
    (net (code "110") (name "Net-(RN_A_PT3B-1)") (class "Default")
      (node (ref "RN_A_PT3") (pin "2") (pinfunction "1_2") (pintype "passive"))
      (node (ref "U_ADC_PT3") (pin "20") (pinfunction "SCLK_20") (pintype "bidirectional"))
    )
    (net (code "111") (name "Net-(RN_A_PT3C-1)") (class "Default")
      (node (ref "RN_A_PT3") (pin "3") (pinfunction "1_3") (pintype "passive"))
      (node (ref "U_ADC_PT3") (pin "19") (pinfunction "DIN_19") (pintype "bidirectional"))
    )
    (net (code "112") (name "Net-(RN_A_PT3D-1)") (class "Default")
      (node (ref "RN_A_PT3") (pin "4") (pinfunction "1_4") (pintype "passive"))
      (node (ref "U_ADC_PT3") (pin "18") (pinfunction "DOUT/~{DRDY}_18") (pintype "bidirectional"))
    )
    (net (code "113") (name "Net-(RN_B_PT1B-1)") (class "Default")
      (node (ref "RN_B_PT1") (pin "2") (pinfunction "1_2") (pintype "passive"))
      (node (ref "U_ADC_PT1") (pin "16") (pinfunction "~{CS}_16") (pintype "bidirectional"))
    )
    (net (code "114") (name "Net-(RN_B_PT1C-1)") (class "Default")
      (node (ref "RN_B_PT1") (pin "3") (pinfunction "1_3") (pintype "passive"))
      (node (ref "U_ADC_PT1") (pin "15") (pinfunction "START_15") (pintype "bidirectional"))
    )
    (net (code "115") (name "Net-(RN_B_PT2B-1)") (class "Default")
      (node (ref "RN_B_PT2") (pin "2") (pinfunction "1_2") (pintype "passive"))
      (node (ref "U_ADC_PT2") (pin "16") (pinfunction "~{CS}_16") (pintype "bidirectional"))
    )
    (net (code "116") (name "Net-(RN_B_PT2C-1)") (class "Default")
      (node (ref "RN_B_PT2") (pin "3") (pinfunction "1_3") (pintype "passive"))
      (node (ref "U_ADC_PT2") (pin "15") (pinfunction "START_15") (pintype "bidirectional"))
    )
    (net (code "117") (name "Net-(RN_B_PT3B-1)") (class "Default")
      (node (ref "RN_B_PT3") (pin "2") (pinfunction "1_2") (pintype "passive"))
      (node (ref "U_ADC_PT3") (pin "16") (pinfunction "~{CS}_16") (pintype "bidirectional"))
    )
    (net (code "118") (name "Net-(RN_B_PT3C-1)") (class "Default")
      (node (ref "RN_B_PT3") (pin "3") (pinfunction "1_3") (pintype "passive"))
      (node (ref "U_ADC_PT3") (pin "15") (pinfunction "START_15") (pintype "bidirectional"))
    )
    (net (code "119") (name "Net-(RN_DMS1B-1)") (class "Default")
      (node (ref "RN_DMS1") (pin "2") (pinfunction "1_2") (pintype "passive"))
      (node (ref "U_ADC_DMS1") (pin "19") (pinfunction "DIN_19") (pintype "bidirectional"))
    )
    (net (code "120") (name "Net-(RN_DMS1C-1)") (class "Default")
      (node (ref "RN_DMS1") (pin "3") (pinfunction "1_3") (pintype "passive"))
      (node (ref "U_ADC_DMS1") (pin "18") (pinfunction "DOUT/~{DRDY}_18") (pintype "bidirectional"))
    )
    (net (code "121") (name "Net-(RN_DMS1D-1)") (class "Default")
      (node (ref "RN_DMS1") (pin "4") (pinfunction "1_4") (pintype "passive"))
      (node (ref "U_ADC_DMS1") (pin "17") (pinfunction "~{DRDY}_17") (pintype "bidirectional"))
    )
    (net (code "122") (name "Net-(RN_DMS2B-1)") (class "Default")
      (node (ref "RN_DMS2") (pin "2") (pinfunction "1_2") (pintype "passive"))
      (node (ref "U_ADC_DMS2") (pin "19") (pinfunction "DIN_19") (pintype "bidirectional"))
    )
    (net (code "123") (name "Net-(RN_DMS2C-1)") (class "Default")
      (node (ref "RN_DMS2") (pin "3") (pinfunction "1_3") (pintype "passive"))
      (node (ref "U_ADC_DMS2") (pin "18") (pinfunction "DOUT/~{DRDY}_18") (pintype "bidirectional"))
    )
    (net (code "124") (name "Net-(RN_DMS2D-1)") (class "Default")
      (node (ref "RN_DMS2") (pin "4") (pinfunction "1_4") (pintype "passive"))
      (node (ref "U_ADC_DMS2") (pin "17") (pinfunction "~{DRDY}_17") (pintype "bidirectional"))
    )
    (net (code "125") (name "Net-(RN_DMS3B-1)") (class "Default")
      (node (ref "RN_DMS3") (pin "2") (pinfunction "1_2") (pintype "passive"))
      (node (ref "U_ADC_DMS3") (pin "19") (pinfunction "DIN_19") (pintype "bidirectional"))
    )
    (net (code "126") (name "Net-(RN_DMS3C-1)") (class "Default")
      (node (ref "RN_DMS3") (pin "3") (pinfunction "1_3") (pintype "passive"))
      (node (ref "U_ADC_DMS3") (pin "18") (pinfunction "DOUT/~{DRDY}_18") (pintype "bidirectional"))
    )
    (net (code "127") (name "Net-(RN_DMS3D-1)") (class "Default")
      (node (ref "RN_DMS3") (pin "4") (pinfunction "1_4") (pintype "passive"))
      (node (ref "U_ADC_DMS3") (pin "17") (pinfunction "~{DRDY}_17") (pintype "bidirectional"))
    )
    (net (code "128") (name "Net-(RN_DMS4B-1)") (class "Default")
      (node (ref "RN_DMS4") (pin "2") (pinfunction "1_2") (pintype "passive"))
      (node (ref "U_ADC_DMS4") (pin "19") (pinfunction "DIN_19") (pintype "bidirectional"))
    )
    (net (code "129") (name "Net-(RN_DMS4C-1)") (class "Default")
      (node (ref "RN_DMS4") (pin "3") (pinfunction "1_3") (pintype "passive"))
      (node (ref "U_ADC_DMS4") (pin "18") (pinfunction "DOUT/~{DRDY}_18") (pintype "bidirectional"))
    )
    (net (code "130") (name "Net-(RN_DMS4D-1)") (class "Default")
      (node (ref "RN_DMS4") (pin "4") (pinfunction "1_4") (pintype "passive"))
      (node (ref "U_ADC_DMS4") (pin "17") (pinfunction "~{DRDY}_17") (pintype "bidirectional"))
    )
    (net (code "131") (name "Net-(RN_DMS5B-1)") (class "Default")
      (node (ref "RN_DMS5") (pin "2") (pinfunction "1_2") (pintype "passive"))
      (node (ref "U_ADC_DMS5") (pin "19") (pinfunction "DIN_19") (pintype "bidirectional"))
    )
    (net (code "132") (name "Net-(RN_DMS5C-1)") (class "Default")
      (node (ref "RN_DMS5") (pin "3") (pinfunction "1_3") (pintype "passive"))
      (node (ref "U_ADC_DMS5") (pin "18") (pinfunction "DOUT/~{DRDY}_18") (pintype "bidirectional"))
    )
    (net (code "133") (name "Net-(RN_DMS5D-1)") (class "Default")
      (node (ref "RN_DMS5") (pin "4") (pinfunction "1_4") (pintype "passive"))
      (node (ref "U_ADC_DMS5") (pin "17") (pinfunction "~{DRDY}_17") (pintype "bidirectional"))
    )
    (net (code "134") (name "Net-(RN_DMS6B-1)") (class "Default")
      (node (ref "RN_DMS6") (pin "2") (pinfunction "1_2") (pintype "passive"))
      (node (ref "U_ADC_DMS6") (pin "19") (pinfunction "DIN_19") (pintype "bidirectional"))
    )
    (net (code "135") (name "Net-(RN_DMS6C-1)") (class "Default")
      (node (ref "RN_DMS6") (pin "3") (pinfunction "1_3") (pintype "passive"))
      (node (ref "U_ADC_DMS6") (pin "18") (pinfunction "DOUT/~{DRDY}_18") (pintype "bidirectional"))
    )
    (net (code "136") (name "Net-(RN_DMS6D-1)") (class "Default")
      (node (ref "RN_DMS6") (pin "4") (pinfunction "1_4") (pintype "passive"))
      (node (ref "U_ADC_DMS6") (pin "17") (pinfunction "~{DRDY}_17") (pintype "bidirectional"))
    )
    (net (code "137") (name "Net-(U$1-4)") (class "Default")
      (node (ref "R32") (pin "2") (pinfunction "2_2") (pintype "passive"))
      (node (ref "U$1") (pin "P$4") (pinfunction "4_P$4") (pintype "passive"))
    )
    (net (code "138") (name "Net-(U$2-4)") (class "Default")
      (node (ref "R4") (pin "2") (pinfunction "2_2") (pintype "passive"))
      (node (ref "U$2") (pin "P$4") (pinfunction "4_P$4") (pintype "passive"))
    )
    (net (code "139") (name "Net-(U$3-4)") (class "Default")
      (node (ref "R39") (pin "2") (pinfunction "2_2") (pintype "passive"))
      (node (ref "U$3") (pin "P$4") (pinfunction "4_P$4") (pintype "passive"))
    )
    (net (code "140") (name "Net-(U$4-4)") (class "Default")
      (node (ref "R46") (pin "2") (pinfunction "2_2") (pintype "passive"))
      (node (ref "U$4") (pin "P$4") (pinfunction "4_P$4") (pintype "passive"))
    )
    (net (code "141") (name "Net-(U$5-4)") (class "Default")
      (node (ref "R53") (pin "2") (pinfunction "2_2") (pintype "passive"))
      (node (ref "U$5") (pin "P$4") (pinfunction "4_P$4") (pintype "passive"))
    )
    (net (code "142") (name "Net-(U$6-4)") (class "Default")
      (node (ref "R60") (pin "2") (pinfunction "2_2") (pintype "passive"))
      (node (ref "U$6") (pin "P$4") (pinfunction "4_P$4") (pintype "passive"))
    )
    (net (code "143") (name "Net-(U_ADC_DMS1-AIN0{slash}IEXC)") (class "Default")
      (node (ref "C6") (pin "2") (pinfunction "2_2") (pintype "passive"))
      (node (ref "C7") (pin "1") (pinfunction "1_1") (pintype "passive"))
      (node (ref "R4") (pin "1") (pinfunction "1_1") (pintype "passive"))
      (node (ref "U_ADC_DMS1") (pin "9") (pinfunction "AIN0/IEXC_9") (pintype "bidirectional"))
    )
    (net (code "144") (name "Net-(U_ADC_DMS1-AIN1{slash}IEXC)") (class "Default")
      (node (ref "C7") (pin "2") (pinfunction "2_2") (pintype "passive"))
      (node (ref "C8") (pin "1") (pinfunction "1_1") (pintype "passive"))
      (node (ref "R5") (pin "1") (pinfunction "1_1") (pintype "passive"))
      (node (ref "U_ADC_DMS1") (pin "10") (pinfunction "AIN1/IEXC_10") (pintype "bidirectional"))
    )
    (net (code "145") (name "Net-(U_ADC_DMS1-SCLK)") (class "Default")
      (node (ref "RN_DMS1") (pin "1") (pinfunction "1_1") (pintype "passive"))
      (node (ref "U_ADC_DMS1") (pin "20") (pinfunction "SCLK_20") (pintype "bidirectional"))
    )
    (net (code "146") (name "Net-(U_ADC_DMS1-START)") (class "Default")
      (node (ref "R2") (pin "1") (pinfunction "1_1") (pintype "passive"))
      (node (ref "U_ADC_DMS1") (pin "15") (pinfunction "START_15") (pintype "bidirectional"))
    )
    (net (code "147") (name "Net-(U_ADC_DMS1-VREFOUT)") (class "Default")
      (node (ref "C4") (pin "1") (pinfunction "1_1") (pintype "passive"))
      (node (ref "U_ADC_DMS1") (pin "7") (pinfunction "VREFOUT_7") (pintype "bidirectional"))
    )
    (net (code "148") (name "Net-(U_ADC_DMS1-~{CS})") (class "Default")
      (node (ref "R3") (pin "1") (pinfunction "1_1") (pintype "passive"))
      (node (ref "U_ADC_DMS1") (pin "16") (pinfunction "~{CS}_16") (pintype "bidirectional"))
    )
    (net (code "149") (name "Net-(U_ADC_DMS1-~{RESET})") (class "Default")
      (node (ref "R1") (pin "2") (pinfunction "2_2") (pintype "passive"))
      (node (ref "U_ADC_DMS1") (pin "4") (pinfunction "~{RESET}_4") (pintype "bidirectional"))
    )
    (net (code "150") (name "Net-(U_ADC_DMS2-AIN0{slash}IEXC)") (class "Default")
      (node (ref "C12") (pin "2") (pinfunction "2_2") (pintype "passive"))
      (node (ref "C13") (pin "1") (pinfunction "1_1") (pintype "passive"))
      (node (ref "R32") (pin "1") (pinfunction "1_1") (pintype "passive"))
      (node (ref "U_ADC_DMS2") (pin "9") (pinfunction "AIN0/IEXC_9") (pintype "bidirectional"))
    )
    (net (code "151") (name "Net-(U_ADC_DMS2-AIN1{slash}IEXC)") (class "Default")
      (node (ref "C13") (pin "2") (pinfunction "2_2") (pintype "passive"))
      (node (ref "C14") (pin "1") (pinfunction "1_1") (pintype "passive"))
      (node (ref "R33") (pin "1") (pinfunction "1_1") (pintype "passive"))
      (node (ref "U_ADC_DMS2") (pin "10") (pinfunction "AIN1/IEXC_10") (pintype "bidirectional"))
    )
    (net (code "152") (name "Net-(U_ADC_DMS2-SCLK)") (class "Default")
      (node (ref "RN_DMS2") (pin "1") (pinfunction "1_1") (pintype "passive"))
      (node (ref "U_ADC_DMS2") (pin "20") (pinfunction "SCLK_20") (pintype "bidirectional"))
    )
    (net (code "153") (name "Net-(U_ADC_DMS2-START)") (class "Default")
      (node (ref "R30") (pin "1") (pinfunction "1_1") (pintype "passive"))
      (node (ref "U_ADC_DMS2") (pin "15") (pinfunction "START_15") (pintype "bidirectional"))
    )
    (net (code "154") (name "Net-(U_ADC_DMS2-VREFOUT)") (class "Default")
      (node (ref "C11") (pin "1") (pinfunction "1_1") (pintype "passive"))
      (node (ref "U_ADC_DMS2") (pin "7") (pinfunction "VREFOUT_7") (pintype "bidirectional"))
    )
    (net (code "155") (name "Net-(U_ADC_DMS2-~{CS})") (class "Default")
      (node (ref "R31") (pin "1") (pinfunction "1_1") (pintype "passive"))
      (node (ref "U_ADC_DMS2") (pin "16") (pinfunction "~{CS}_16") (pintype "bidirectional"))
    )
    (net (code "156") (name "Net-(U_ADC_DMS2-~{RESET})") (class "Default")
      (node (ref "R8") (pin "2") (pinfunction "2_2") (pintype "passive"))
      (node (ref "U_ADC_DMS2") (pin "4") (pinfunction "~{RESET}_4") (pintype "bidirectional"))
    )
    (net (code "157") (name "Net-(U_ADC_DMS3-AIN0{slash}IEXC)") (class "Default")
      (node (ref "C21") (pin "2") (pinfunction "2_2") (pintype "passive"))
      (node (ref "C22") (pin "1") (pinfunction "1_1") (pintype "passive"))
      (node (ref "R39") (pin "1") (pinfunction "1_1") (pintype "passive"))
      (node (ref "U_ADC_DMS3") (pin "9") (pinfunction "AIN0/IEXC_9") (pintype "bidirectional"))
    )
    (net (code "158") (name "Net-(U_ADC_DMS3-AIN1{slash}IEXC)") (class "Default")
      (node (ref "C22") (pin "2") (pinfunction "2_2") (pintype "passive"))
      (node (ref "C23") (pin "1") (pinfunction "1_1") (pintype "passive"))
      (node (ref "R40") (pin "1") (pinfunction "1_1") (pintype "passive"))
      (node (ref "U_ADC_DMS3") (pin "10") (pinfunction "AIN1/IEXC_10") (pintype "bidirectional"))
    )
    (net (code "159") (name "Net-(U_ADC_DMS3-SCLK)") (class "Default")
      (node (ref "RN_DMS3") (pin "1") (pinfunction "1_1") (pintype "passive"))
      (node (ref "U_ADC_DMS3") (pin "20") (pinfunction "SCLK_20") (pintype "bidirectional"))
    )
    (net (code "160") (name "Net-(U_ADC_DMS3-START)") (class "Default")
      (node (ref "R37") (pin "1") (pinfunction "1_1") (pintype "passive"))
      (node (ref "U_ADC_DMS3") (pin "15") (pinfunction "START_15") (pintype "bidirectional"))
    )
    (net (code "161") (name "Net-(U_ADC_DMS3-VREFOUT)") (class "Default")
      (node (ref "C20") (pin "1") (pinfunction "1_1") (pintype "passive"))
      (node (ref "U_ADC_DMS3") (pin "7") (pinfunction "VREFOUT_7") (pintype "bidirectional"))
    )
    (net (code "162") (name "Net-(U_ADC_DMS3-~{CS})") (class "Default")
      (node (ref "R38") (pin "1") (pinfunction "1_1") (pintype "passive"))
      (node (ref "U_ADC_DMS3") (pin "16") (pinfunction "~{CS}_16") (pintype "bidirectional"))
    )
    (net (code "163") (name "Net-(U_ADC_DMS3-~{RESET})") (class "Default")
      (node (ref "R36") (pin "2") (pinfunction "2_2") (pintype "passive"))
      (node (ref "U_ADC_DMS3") (pin "4") (pinfunction "~{RESET}_4") (pintype "bidirectional"))
    )
    (net (code "164") (name "Net-(U_ADC_DMS4-AIN0{slash}IEXC)") (class "Default")
      (node (ref "C27") (pin "2") (pinfunction "2_2") (pintype "passive"))
      (node (ref "C45") (pin "1") (pinfunction "1_1") (pintype "passive"))
      (node (ref "R46") (pin "1") (pinfunction "1_1") (pintype "passive"))
      (node (ref "U_ADC_DMS4") (pin "9") (pinfunction "AIN0/IEXC_9") (pintype "bidirectional"))
    )
    (net (code "165") (name "Net-(U_ADC_DMS4-AIN1{slash}IEXC)") (class "Default")
      (node (ref "C45") (pin "2") (pinfunction "2_2") (pintype "passive"))
      (node (ref "C46") (pin "1") (pinfunction "1_1") (pintype "passive"))
      (node (ref "R47") (pin "1") (pinfunction "1_1") (pintype "passive"))
      (node (ref "U_ADC_DMS4") (pin "10") (pinfunction "AIN1/IEXC_10") (pintype "bidirectional"))
    )
    (net (code "166") (name "Net-(U_ADC_DMS4-SCLK)") (class "Default")
      (node (ref "RN_DMS4") (pin "1") (pinfunction "1_1") (pintype "passive"))
      (node (ref "U_ADC_DMS4") (pin "20") (pinfunction "SCLK_20") (pintype "bidirectional"))
    )
    (net (code "167") (name "Net-(U_ADC_DMS4-START)") (class "Default")
      (node (ref "R44") (pin "1") (pinfunction "1_1") (pintype "passive"))
      (node (ref "U_ADC_DMS4") (pin "15") (pinfunction "START_15") (pintype "bidirectional"))
    )
    (net (code "168") (name "Net-(U_ADC_DMS4-VREFOUT)") (class "Default")
      (node (ref "C26") (pin "1") (pinfunction "1_1") (pintype "passive"))
      (node (ref "U_ADC_DMS4") (pin "7") (pinfunction "VREFOUT_7") (pintype "bidirectional"))
    )
    (net (code "169") (name "Net-(U_ADC_DMS4-~{CS})") (class "Default")
      (node (ref "R45") (pin "1") (pinfunction "1_1") (pintype "passive"))
      (node (ref "U_ADC_DMS4") (pin "16") (pinfunction "~{CS}_16") (pintype "bidirectional"))
    )
    (net (code "170") (name "Net-(U_ADC_DMS4-~{RESET})") (class "Default")
      (node (ref "R43") (pin "2") (pinfunction "2_2") (pintype "passive"))
      (node (ref "U_ADC_DMS4") (pin "4") (pinfunction "~{RESET}_4") (pintype "bidirectional"))
    )
    (net (code "171") (name "Net-(U_ADC_DMS5-AIN0{slash}IEXC)") (class "Default")
      (node (ref "C50") (pin "2") (pinfunction "2_2") (pintype "passive"))
      (node (ref "C51") (pin "1") (pinfunction "1_1") (pintype "passive"))
      (node (ref "R53") (pin "1") (pinfunction "1_1") (pintype "passive"))
      (node (ref "U_ADC_DMS5") (pin "9") (pinfunction "AIN0/IEXC_9") (pintype "bidirectional"))
    )
    (net (code "172") (name "Net-(U_ADC_DMS5-AIN1{slash}IEXC)") (class "Default")
      (node (ref "C51") (pin "2") (pinfunction "2_2") (pintype "passive"))
      (node (ref "C53") (pin "1") (pinfunction "1_1") (pintype "passive"))
      (node (ref "R54") (pin "1") (pinfunction "1_1") (pintype "passive"))
      (node (ref "U_ADC_DMS5") (pin "10") (pinfunction "AIN1/IEXC_10") (pintype "bidirectional"))
    )
    (net (code "173") (name "Net-(U_ADC_DMS5-SCLK)") (class "Default")
      (node (ref "RN_DMS5") (pin "1") (pinfunction "1_1") (pintype "passive"))
      (node (ref "U_ADC_DMS5") (pin "20") (pinfunction "SCLK_20") (pintype "bidirectional"))
    )
    (net (code "174") (name "Net-(U_ADC_DMS5-START)") (class "Default")
      (node (ref "R51") (pin "1") (pinfunction "1_1") (pintype "passive"))
      (node (ref "U_ADC_DMS5") (pin "15") (pinfunction "START_15") (pintype "bidirectional"))
    )
    (net (code "175") (name "Net-(U_ADC_DMS5-VREFOUT)") (class "Default")
      (node (ref "C49") (pin "1") (pinfunction "1_1") (pintype "passive"))
      (node (ref "U_ADC_DMS5") (pin "7") (pinfunction "VREFOUT_7") (pintype "bidirectional"))
    )
    (net (code "176") (name "Net-(U_ADC_DMS5-~{CS})") (class "Default")
      (node (ref "R52") (pin "1") (pinfunction "1_1") (pintype "passive"))
      (node (ref "U_ADC_DMS5") (pin "16") (pinfunction "~{CS}_16") (pintype "bidirectional"))
    )
    (net (code "177") (name "Net-(U_ADC_DMS5-~{RESET})") (class "Default")
      (node (ref "R50") (pin "2") (pinfunction "2_2") (pintype "passive"))
      (node (ref "U_ADC_DMS5") (pin "4") (pinfunction "~{RESET}_4") (pintype "bidirectional"))
    )
    (net (code "178") (name "Net-(U_ADC_DMS6-AIN0{slash}IEXC)") (class "Default")
      (node (ref "C57") (pin "2") (pinfunction "2_2") (pintype "passive"))
      (node (ref "C58") (pin "1") (pinfunction "1_1") (pintype "passive"))
      (node (ref "R60") (pin "1") (pinfunction "1_1") (pintype "passive"))
      (node (ref "U_ADC_DMS6") (pin "9") (pinfunction "AIN0/IEXC_9") (pintype "bidirectional"))
    )
    (net (code "179") (name "Net-(U_ADC_DMS6-AIN1{slash}IEXC)") (class "Default")
      (node (ref "C58") (pin "2") (pinfunction "2_2") (pintype "passive"))
      (node (ref "C59") (pin "1") (pinfunction "1_1") (pintype "passive"))
      (node (ref "R61") (pin "1") (pinfunction "1_1") (pintype "passive"))
      (node (ref "U_ADC_DMS6") (pin "10") (pinfunction "AIN1/IEXC_10") (pintype "bidirectional"))
    )
    (net (code "180") (name "Net-(U_ADC_DMS6-SCLK)") (class "Default")
      (node (ref "RN_DMS6") (pin "1") (pinfunction "1_1") (pintype "passive"))
      (node (ref "U_ADC_DMS6") (pin "20") (pinfunction "SCLK_20") (pintype "bidirectional"))
    )
    (net (code "181") (name "Net-(U_ADC_DMS6-START)") (class "Default")
      (node (ref "R58") (pin "1") (pinfunction "1_1") (pintype "passive"))
      (node (ref "U_ADC_DMS6") (pin "15") (pinfunction "START_15") (pintype "bidirectional"))
    )
    (net (code "182") (name "Net-(U_ADC_DMS6-VREFOUT)") (class "Default")
      (node (ref "C56") (pin "1") (pinfunction "1_1") (pintype "passive"))
      (node (ref "U_ADC_DMS6") (pin "7") (pinfunction "VREFOUT_7") (pintype "bidirectional"))
    )
    (net (code "183") (name "Net-(U_ADC_DMS6-~{CS})") (class "Default")
      (node (ref "R59") (pin "1") (pinfunction "1_1") (pintype "passive"))
      (node (ref "U_ADC_DMS6") (pin "16") (pinfunction "~{CS}_16") (pintype "bidirectional"))
    )
    (net (code "184") (name "Net-(U_ADC_DMS6-~{RESET})") (class "Default")
      (node (ref "R57") (pin "2") (pinfunction "2_2") (pintype "passive"))
      (node (ref "U_ADC_DMS6") (pin "4") (pinfunction "~{RESET}_4") (pintype "bidirectional"))
    )
    (net (code "185") (name "Net-(U_ADC_PT1-AIN1{slash}IEXC)") (class "Default")
      (node (ref "C_ICM1_PT1") (pin "2") (pinfunction "2_2") (pintype "passive"))
      (node (ref "C_IDIFF_PT1") (pin "1") (pinfunction "1_1") (pintype "passive"))
      (node (ref "R_I1_PT1") (pin "1") (pinfunction "1_1") (pintype "passive"))
      (node (ref "U_ADC_PT1") (pin "10") (pinfunction "AIN1/IEXC_10") (pintype "bidirectional"))
    )
    (net (code "186") (name "Net-(U_ADC_PT1-AIN2{slash}IEXC{slash}GPIO2)") (class "Default")
      (node (ref "C_ICM2_PT1") (pin "1") (pinfunction "1_1") (pintype "passive"))
      (node (ref "C_IDIFF_PT1") (pin "2") (pinfunction "2_2") (pintype "passive"))
      (node (ref "R_I2_PT1") (pin "1") (pinfunction "1_1") (pintype "passive"))
      (node (ref "U_ADC_PT1") (pin "11") (pinfunction "AIN2/IEXC/GPIO2_11") (pintype "bidirectional"))
    )
    (net (code "187") (name "Net-(U_ADC_PT1-REFN0{slash}GPIO1)") (class "Default")
      (node (ref "C_RCM2_PT1") (pin "1") (pinfunction "1_1") (pintype "passive"))
      (node (ref "C_RDIFF_PT1") (pin "2") (pinfunction "2_2") (pintype "passive"))
      (node (ref "R_R2_PT1") (pin "1") (pinfunction "1_1") (pintype "passive"))
      (node (ref "U_ADC_PT1") (pin "6") (pinfunction "REFN0/GPIO1_6") (pintype "bidirectional"))
    )
    (net (code "188") (name "Net-(U_ADC_PT1-REFP0{slash}GPIO0)") (class "Default")
      (node (ref "C_RCM1_PT1") (pin "2") (pinfunction "2_2") (pintype "passive"))
      (node (ref "C_RDIFF_PT1") (pin "1") (pinfunction "1_1") (pintype "passive"))
      (node (ref "R_R1_PT1") (pin "1") (pinfunction "1_1") (pintype "passive"))
      (node (ref "U_ADC_PT1") (pin "5") (pinfunction "REFP0/GPIO0_5") (pintype "bidirectional"))
    )
    (net (code "189") (name "Net-(U_ADC_PT1-VREFOUT)") (class "Default")
      (node (ref "C_VREF_PT1") (pin "1") (pinfunction "1_1") (pintype "passive"))
      (node (ref "U_ADC_PT1") (pin "7") (pinfunction "VREFOUT_7") (pintype "bidirectional"))
    )
    (net (code "190") (name "Net-(U_ADC_PT1-~{DRDY})") (class "Default")
      (node (ref "RN_B_PT1") (pin "1") (pinfunction "1_1") (pintype "passive"))
      (node (ref "U_ADC_PT1") (pin "17") (pinfunction "~{DRDY}_17") (pintype "bidirectional"))
    )
    (net (code "191") (name "Net-(U_ADC_PT1-~{RESET})") (class "Default")
      (node (ref "RN_A_PT1") (pin "1") (pinfunction "1_1") (pintype "passive"))
      (node (ref "U_ADC_PT1") (pin "4") (pinfunction "~{RESET}_4") (pintype "bidirectional"))
    )
    (net (code "192") (name "Net-(U_ADC_PT2-AIN1{slash}IEXC)") (class "Default")
      (node (ref "C_ICM1_PT2") (pin "2") (pinfunction "2_2") (pintype "passive"))
      (node (ref "C_IDIFF_PT2") (pin "1") (pinfunction "1_1") (pintype "passive"))
      (node (ref "R_I1_PT2") (pin "1") (pinfunction "1_1") (pintype "passive"))
      (node (ref "U_ADC_PT2") (pin "10") (pinfunction "AIN1/IEXC_10") (pintype "bidirectional"))
    )
    (net (code "193") (name "Net-(U_ADC_PT2-AIN2{slash}IEXC{slash}GPIO2)") (class "Default")
      (node (ref "C_ICM2_PT2") (pin "1") (pinfunction "1_1") (pintype "passive"))
      (node (ref "C_IDIFF_PT2") (pin "2") (pinfunction "2_2") (pintype "passive"))
      (node (ref "R_I2_PT2") (pin "1") (pinfunction "1_1") (pintype "passive"))
      (node (ref "U_ADC_PT2") (pin "11") (pinfunction "AIN2/IEXC/GPIO2_11") (pintype "bidirectional"))
    )
    (net (code "194") (name "Net-(U_ADC_PT2-REFN0{slash}GPIO1)") (class "Default")
      (node (ref "C_RCM2_PT2") (pin "1") (pinfunction "1_1") (pintype "passive"))
      (node (ref "C_RDIFF_PT2") (pin "2") (pinfunction "2_2") (pintype "passive"))
      (node (ref "R_R2_PT2") (pin "1") (pinfunction "1_1") (pintype "passive"))
      (node (ref "U_ADC_PT2") (pin "6") (pinfunction "REFN0/GPIO1_6") (pintype "bidirectional"))
    )
    (net (code "195") (name "Net-(U_ADC_PT2-REFP0{slash}GPIO0)") (class "Default")
      (node (ref "C_RCM1_PT2") (pin "2") (pinfunction "2_2") (pintype "passive"))
      (node (ref "C_RDIFF_PT2") (pin "1") (pinfunction "1_1") (pintype "passive"))
      (node (ref "R_R1_PT2") (pin "1") (pinfunction "1_1") (pintype "passive"))
      (node (ref "U_ADC_PT2") (pin "5") (pinfunction "REFP0/GPIO0_5") (pintype "bidirectional"))
    )
    (net (code "196") (name "Net-(U_ADC_PT2-VREFOUT)") (class "Default")
      (node (ref "C_VREF_PT2") (pin "1") (pinfunction "1_1") (pintype "passive"))
      (node (ref "U_ADC_PT2") (pin "7") (pinfunction "VREFOUT_7") (pintype "bidirectional"))
    )
    (net (code "197") (name "Net-(U_ADC_PT2-~{DRDY})") (class "Default")
      (node (ref "RN_B_PT2") (pin "1") (pinfunction "1_1") (pintype "passive"))
      (node (ref "U_ADC_PT2") (pin "17") (pinfunction "~{DRDY}_17") (pintype "bidirectional"))
    )
    (net (code "198") (name "Net-(U_ADC_PT2-~{RESET})") (class "Default")
      (node (ref "RN_A_PT2") (pin "1") (pinfunction "1_1") (pintype "passive"))
      (node (ref "U_ADC_PT2") (pin "4") (pinfunction "~{RESET}_4") (pintype "bidirectional"))
    )
    (net (code "199") (name "Net-(U_ADC_PT3-AIN1{slash}IEXC)") (class "Default")
      (node (ref "C_ICM1_PT3") (pin "2") (pinfunction "2_2") (pintype "passive"))
      (node (ref "C_IDIFF_PT3") (pin "1") (pinfunction "1_1") (pintype "passive"))
      (node (ref "R_I1_PT3") (pin "1") (pinfunction "1_1") (pintype "passive"))
      (node (ref "U_ADC_PT3") (pin "10") (pinfunction "AIN1/IEXC_10") (pintype "bidirectional"))
    )
    (net (code "200") (name "Net-(U_ADC_PT3-AIN2{slash}IEXC{slash}GPIO2)") (class "Default")
      (node (ref "C_ICM2_PT3") (pin "1") (pinfunction "1_1") (pintype "passive"))
      (node (ref "C_IDIFF_PT3") (pin "2") (pinfunction "2_2") (pintype "passive"))
      (node (ref "R_I2_PT3") (pin "1") (pinfunction "1_1") (pintype "passive"))
      (node (ref "U_ADC_PT3") (pin "11") (pinfunction "AIN2/IEXC/GPIO2_11") (pintype "bidirectional"))
    )
    (net (code "201") (name "Net-(U_ADC_PT3-REFN0{slash}GPIO1)") (class "Default")
      (node (ref "C_RCM2_PT3") (pin "1") (pinfunction "1_1") (pintype "passive"))
      (node (ref "C_RDIFF_PT3") (pin "2") (pinfunction "2_2") (pintype "passive"))
      (node (ref "R_R2_PT3") (pin "1") (pinfunction "1_1") (pintype "passive"))
      (node (ref "U_ADC_PT3") (pin "6") (pinfunction "REFN0/GPIO1_6") (pintype "bidirectional"))
    )
    (net (code "202") (name "Net-(U_ADC_PT3-REFP0{slash}GPIO0)") (class "Default")
      (node (ref "C_RCM1_PT3") (pin "2") (pinfunction "2_2") (pintype "passive"))
      (node (ref "C_RDIFF_PT3") (pin "1") (pinfunction "1_1") (pintype "passive"))
      (node (ref "R_R1_PT3") (pin "1") (pinfunction "1_1") (pintype "passive"))
      (node (ref "U_ADC_PT3") (pin "5") (pinfunction "REFP0/GPIO0_5") (pintype "bidirectional"))
    )
    (net (code "203") (name "Net-(U_ADC_PT3-VREFOUT)") (class "Default")
      (node (ref "C_VREF_PT3") (pin "1") (pinfunction "1_1") (pintype "passive"))
      (node (ref "U_ADC_PT3") (pin "7") (pinfunction "VREFOUT_7") (pintype "bidirectional"))
    )
    (net (code "204") (name "Net-(U_ADC_PT3-~{DRDY})") (class "Default")
      (node (ref "RN_B_PT3") (pin "1") (pinfunction "1_1") (pintype "passive"))
      (node (ref "U_ADC_PT3") (pin "17") (pinfunction "~{DRDY}_17") (pintype "bidirectional"))
    )
    (net (code "205") (name "Net-(U_ADC_PT3-~{RESET})") (class "Default")
      (node (ref "RN_A_PT3") (pin "1") (pinfunction "1_1") (pintype "passive"))
      (node (ref "U_ADC_PT3") (pin "4") (pinfunction "~{RESET}_4") (pintype "bidirectional"))
    )
    (net (code "206") (name "Net-(U_ADR366_3-TRIM)") (class "Default")
      (node (ref "R22") (pin "1") (pinfunction "1_1") (pintype "passive"))
      (node (ref "U_ADR366_3") (pin "5") (pinfunction "TRIM_5") (pintype "passive"))
    )
    (net (code "207") (name "Net-(U_CH340G-XI)") (class "Default")
      (node (ref "C1") (pin "1") (pinfunction "1_1") (pintype "passive"))
      (node (ref "Q1") (pin "1") (pinfunction "1_1") (pintype "passive"))
      (node (ref "U_CH340G") (pin "7") (pinfunction "XI_7") (pintype "bidirectional"))
    )
    (net (code "208") (name "Net-(U_CH340G-XO)") (class "Default")
      (node (ref "C2") (pin "1") (pinfunction "1_1") (pintype "passive"))
      (node (ref "Q1") (pin "2") (pinfunction "2_2") (pintype "passive"))
      (node (ref "U_CH340G") (pin "8") (pinfunction "XO_8") (pintype "bidirectional"))
    )
    (net (code "209") (name "Net-(U_OPTO_3-C1)") (class "Default")
      (node (ref "R11") (pin "2") (pinfunction "2_2") (pintype "passive"))
      (node (ref "U_OPTO_3") (pin "2") (pinfunction "C1_2") (pintype "bidirectional"))
    )
    (net (code "210") (name "Net-(U_OPTO_3-C2)") (class "Default")
      (node (ref "R12") (pin "2") (pinfunction "2_2") (pintype "passive"))
      (node (ref "U_OPTO_3") (pin "4") (pinfunction "C2_4") (pintype "bidirectional"))
    )
    (net (code "211") (name "Net-(U_STM32F779-BOOT0)") (class "Default")
      (node (ref "R27") (pin "1") (pinfunction "1_1") (pintype "passive"))
      (node (ref "R28") (pin "2") (pinfunction "2_2") (pintype "passive"))
      (node (ref "U_STM32F779") (pin "197") (pinfunction "BOOT0_197") (pintype "bidirectional"))
    )
    (net (code "212") (name "Net-(U_STM32F779-VCAPDSI)") (class "Default")
      (node (ref "U_STM32F779") (pin "119") (pinfunction "VCAPDSI_119") (pintype "bidirectional"))
      (node (ref "U_STM32F779") (pin "125") (pinfunction "VDD12DSI_125") (pintype "bidirectional"))
    )
    (net (code "213") (name "Net-(U_STM32F779-VCAP_1)") (class "Default")
      (node (ref "C17") (pin "2") (pinfunction "2_2") (pintype "passive"))
      (node (ref "U_STM32F779") (pin "92") (pinfunction "VCAP_1_92") (pintype "bidirectional"))
    )
    (net (code "214") (name "Net-(U_STM32F779-VCAP_2)") (class "Default")
      (node (ref "C16") (pin "2") (pinfunction "2_2") (pintype "passive"))
      (node (ref "U_STM32F779") (pin "148") (pinfunction "VCAP_2_148") (pintype "bidirectional"))
    )
    (net (code "215") (name "OUT_PT_1") (class "Default")
      (node (ref "U_STM32F779") (pin "62") (pinfunction "PB1_62") (pintype "bidirectional"))
    )
    (net (code "216") (name "OUT_PT_2") (class "Default")
      (node (ref "U_STM32F779") (pin "53") (pinfunction "PA4_53") (pintype "bidirectional"))
    )
    (net (code "217") (name "OUT_PT_3") (class "Default")
      (node (ref "U_STM32F779") (pin "61") (pinfunction "PB0_61") (pintype "bidirectional"))
    )
    (net (code "218") (name "PRD_ON") (class "Default")
      (node (ref "R9") (pin "1") (pinfunction "1_1") (pintype "passive"))
      (node (ref "U_STM32F779") (pin "203") (pinfunction "PDR_ON_203") (pintype "bidirectional"))
    )
    (net (code "219") (name "PT11") (class "Default")
      (node (ref "R_I1_PT1") (pin "2") (pinfunction "2_2") (pintype "passive"))
      (node (ref "U_ADC_PT1") (pin "9") (pinfunction "AIN0/IEXC_9") (pintype "bidirectional"))
      (node (ref "X_PT") (pin "P$B3") (pinfunction "B3_P$B3") (pintype "passive"))
    )
    (net (code "220") (name "PT12") (class "Default")
      (node (ref "R_I2_PT1") (pin "2") (pinfunction "2_2") (pintype "passive"))
      (node (ref "U_ADC_PT1") (pin "12") (pinfunction "AIN3/IEXC/GPIO3_12") (pintype "bidirectional"))
      (node (ref "X_PT") (pin "P$B2") (pinfunction "B2_P$B2") (pintype "passive"))
    )
    (net (code "221") (name "PT13") (class "Default")
      (node (ref "R_R1_PT1") (pin "2") (pinfunction "2_2") (pintype "passive"))
      (node (ref "R_REF_PT1") (pin "2") (pinfunction "2_2") (pintype "passive"))
      (node (ref "X_PT") (pin "P$B1") (pinfunction "B1_P$B1") (pintype "passive"))
    )
    (net (code "222") (name "PT21") (class "Default")
      (node (ref "R_I1_PT2") (pin "2") (pinfunction "2_2") (pintype "passive"))
      (node (ref "U_ADC_PT2") (pin "9") (pinfunction "AIN0/IEXC_9") (pintype "bidirectional"))
      (node (ref "X_PT") (pin "P$B5") (pinfunction "B5_P$B5") (pintype "passive"))
    )
    (net (code "223") (name "PT22") (class "Default")
      (node (ref "R_I2_PT2") (pin "2") (pinfunction "2_2") (pintype "passive"))
      (node (ref "U_ADC_PT2") (pin "12") (pinfunction "AIN3/IEXC/GPIO3_12") (pintype "bidirectional"))
      (node (ref "X_PT") (pin "P$B4") (pinfunction "B4_P$B4") (pintype "passive"))
    )
    (net (code "224") (name "PT23") (class "Default")
      (node (ref "R_R1_PT2") (pin "2") (pinfunction "2_2") (pintype "passive"))
      (node (ref "R_REF_PT2") (pin "2") (pinfunction "2_2") (pintype "passive"))
      (node (ref "X_PT") (pin "P$B6") (pinfunction "B6_P$B6") (pintype "passive"))
    )
    (net (code "225") (name "PT31") (class "Default")
      (node (ref "R_I1_PT3") (pin "2") (pinfunction "2_2") (pintype "passive"))
      (node (ref "U_ADC_PT3") (pin "9") (pinfunction "AIN0/IEXC_9") (pintype "bidirectional"))
      (node (ref "X_PT") (pin "P$A1") (pinfunction "A1_P$A1") (pintype "passive"))
    )
    (net (code "226") (name "PT32") (class "Default")
      (node (ref "R_I2_PT3") (pin "2") (pinfunction "2_2") (pintype "passive"))
      (node (ref "U_ADC_PT3") (pin "12") (pinfunction "AIN3/IEXC/GPIO3_12") (pintype "bidirectional"))
      (node (ref "X_PT") (pin "P$A2") (pinfunction "A2_P$A2") (pintype "passive"))
    )
    (net (code "227") (name "PT33") (class "Default")
      (node (ref "R_R1_PT3") (pin "2") (pinfunction "2_2") (pintype "passive"))
      (node (ref "R_REF_PT3") (pin "2") (pinfunction "2_2") (pintype "passive"))
      (node (ref "X_PT") (pin "P$A3") (pinfunction "A3_P$A3") (pintype "passive"))
    )
    (net (code "228") (name "PT_DIN") (class "Default")
      (node (ref "RN_A_PT1") (pin "6") (pinfunction "2_6") (pintype "passive"))
      (node (ref "RN_A_PT2") (pin "6") (pinfunction "2_6") (pintype "passive"))
      (node (ref "RN_A_PT3") (pin "6") (pinfunction "2_6") (pintype "passive"))
    )
    (net (code "229") (name "PT_DOUT") (class "Default")
      (node (ref "RN_A_PT1") (pin "5") (pinfunction "2_5") (pintype "passive"))
      (node (ref "RN_A_PT2") (pin "5") (pinfunction "2_5") (pintype "passive"))
      (node (ref "RN_A_PT3") (pin "5") (pinfunction "2_5") (pintype "passive"))
    )
    (net (code "230") (name "PT_SCLK") (class "Default")
      (node (ref "RN_A_PT1") (pin "7") (pinfunction "2_7") (pintype "passive"))
      (node (ref "RN_A_PT2") (pin "7") (pinfunction "2_7") (pintype "passive"))
      (node (ref "RN_A_PT3") (pin "7") (pinfunction "2_7") (pintype "passive"))
    )
    (net (code "231") (name "SODS") (class "Default")
      (node (ref "U_OPTO_1") (pin "2") (pinfunction "C1_2") (pintype "bidirectional"))
      (node (ref "X_MIRROR") (pin "P$A7") (pinfunction "A7_P$A7") (pintype "passive"))
      (node (ref "X_MIRROR1") (pin "P$A7") (pinfunction "A7_P$A7") (pintype "passive"))
      (node (ref "X_RXSM-DAPI") (pin "P$B6") (pinfunction "B6_P$B6") (pintype "passive"))
    )
    (net (code "232") (name "SODS_OPT") (class "Default")
      (node (ref "D8") (pin "C") (pinfunction "C_C") (pintype "passive"))
      (node (ref "RN12") (pin "8") (pinfunction "2_8") (pintype "passive"))
      (node (ref "U_OPTO_1") (pin "8") (pinfunction "COL1_8") (pintype "input"))
      (node (ref "U_STM32F779") (pin "206") (pinfunction "PI5_206") (pintype "bidirectional"))
    )
    (net (code "233") (name "SOE") (class "Default")
      (node (ref "U_OPTO_1") (pin "4") (pinfunction "C2_4") (pintype "bidirectional"))
      (node (ref "X_MIRROR") (pin "P$A6") (pinfunction "A6_P$A6") (pintype "passive"))
      (node (ref "X_MIRROR1") (pin "P$A8") (pinfunction "A8_P$A8") (pintype "passive"))
      (node (ref "X_RXSM-DAPI") (pin "P$B5") (pinfunction "B5_P$B5") (pintype "passive"))
    )
    (net (code "234") (name "SOE_OPT") (class "Default")
      (node (ref "D9") (pin "C") (pinfunction "C_C") (pintype "passive"))
      (node (ref "RN12") (pin "7") (pinfunction "2_7") (pintype "passive"))
      (node (ref "U_OPTO_1") (pin "6") (pinfunction "COL2_6") (pintype "input"))
      (node (ref "U_STM32F779") (pin "207") (pinfunction "PI6_207") (pintype "bidirectional"))
    )
    (net (code "235") (name "SPI2_MISO") (class "Default")
      (node (ref "U_S70FL01GS_2") (pin "8") (pinfunction "SO_8") (pintype "bidirectional"))
      (node (ref "U_STM32F779") (pin "106") (pinfunction "PB14_106") (pintype "bidirectional"))
    )
    (net (code "236") (name "SPI2_MOSI") (class "Default")
      (node (ref "U_S70FL01GS_2") (pin "15") (pinfunction "SI_15") (pintype "bidirectional"))
      (node (ref "U_STM32F779") (pin "107") (pinfunction "PB15_107") (pintype "bidirectional"))
    )
    (net (code "237") (name "SPI2_SCK") (class "Default")
      (node (ref "U_S70FL01GS_2") (pin "16") (pinfunction "SCK_16") (pintype "bidirectional"))
      (node (ref "U_STM32F779") (pin "105") (pinfunction "PB13_105") (pintype "bidirectional"))
    )
    (net (code "238") (name "SPI3_CS") (class "Default")
      (node (ref "U_STM32F779") (pin "66") (pinfunction "PJ1_66") (pintype "bidirectional"))
    )
    (net (code "239") (name "SPI3_CS2") (class "Default")
      (node (ref "U_STM32F779") (pin "18") (pinfunction "PF2_18") (pintype "bidirectional"))
    )
    (net (code "240") (name "SPI3_MISO") (class "Default")
      (node (ref "U_STM32F779") (pin "162") (pinfunction "PC11_162") (pintype "bidirectional"))
    )
    (net (code "241") (name "SPI3_MOSI") (class "Default")
      (node (ref "U_STM32F779") (pin "63") (pinfunction "PB2_63") (pintype "bidirectional"))
    )
    (net (code "242") (name "SPI3_SCK") (class "Default")
      (node (ref "U_STM32F779") (pin "161") (pinfunction "PC10_161") (pintype "bidirectional"))
    )
    (net (code "243") (name "SPI4_CS") (class "Default")
      (node (ref "U_STM32F779") (pin "48") (pinfunction "PH4_48") (pintype "bidirectional"))
    )
    (net (code "244") (name "SPI4_CS2") (class "Default")
      (node (ref "U_STM32F779") (pin "19") (pinfunction "PI12_19") (pintype "bidirectional"))
    )
    (net (code "245") (name "SPI4_MISO") (class "Default")
      (node (ref "U_STM32F779") (pin "4") (pinfunction "PE5_4") (pintype "bidirectional"))
    )
    (net (code "246") (name "SPI4_MOSI") (class "Default")
      (node (ref "U_STM32F779") (pin "5") (pinfunction "PE6_5") (pintype "bidirectional"))
    )
    (net (code "247") (name "SPI4_SCK") (class "Default")
      (node (ref "U_STM32F779") (pin "1") (pinfunction "PE2_1") (pintype "bidirectional"))
    )
    (net (code "248") (name "SPI5_CS") (class "Default")
      (node (ref "U_STM32F779") (pin "74") (pinfunction "PF13_74") (pintype "bidirectional"))
    )
    (net (code "249") (name "SPI5_CS2") (class "Default")
      (node (ref "U_STM32F779") (pin "20") (pinfunction "PI13_20") (pintype "bidirectional"))
    )
    (net (code "250") (name "SPI5_MISO") (class "Default")
      (node (ref "U_STM32F779") (pin "29") (pinfunction "PF8_29") (pintype "bidirectional"))
    )
    (net (code "251") (name "SPI5_MOSI") (class "Default")
      (node (ref "U_STM32F779") (pin "70") (pinfunction "PF11_70") (pintype "bidirectional"))
    )
    (net (code "252") (name "SPI5_SCK") (class "Default")
      (node (ref "U_STM32F779") (pin "28") (pinfunction "PF7_28") (pintype "bidirectional"))
    )
    (net (code "253") (name "SPI6_MISO") (class "Default")
      (node (ref "U_S70FL01GS_1") (pin "8") (pinfunction "SO_8") (pintype "bidirectional"))
      (node (ref "U_STM32F779") (pin "55") (pinfunction "PA6_55") (pintype "bidirectional"))
    )
    (net (code "254") (name "SPI6_MOSI") (class "Default")
      (node (ref "U_S70FL01GS_1") (pin "15") (pinfunction "SI_15") (pintype "bidirectional"))
      (node (ref "U_STM32F779") (pin "56") (pinfunction "PA7_56") (pintype "bidirectional"))
    )
    (net (code "255") (name "SPI6_SCK") (class "Default")
      (node (ref "U_S70FL01GS_1") (pin "16") (pinfunction "SCK_16") (pintype "bidirectional"))
      (node (ref "U_STM32F779") (pin "54") (pinfunction "PA5_54") (pintype "bidirectional"))
    )
    (net (code "256") (name "TCK") (class "Default")
      (node (ref "U_STM32F779") (pin "159") (pinfunction "PA14_159") (pintype "bidirectional"))
      (node (ref "X_PROG") (pin "9") (pinfunction "9_9") (pintype "passive"))
    )
    (net (code "257") (name "TDI") (class "Default")
      (node (ref "U_STM32F779") (pin "160") (pinfunction "PA15_160") (pintype "bidirectional"))
      (node (ref "X_PROG") (pin "5") (pinfunction "5_5") (pintype "passive"))
    )
    (net (code "258") (name "TDO") (class "Default")
      (node (ref "U_STM32F779") (pin "192") (pinfunction "PB3_192") (pintype "bidirectional"))
      (node (ref "X_PROG") (pin "13") (pinfunction "13_13") (pintype "passive"))
    )
    (net (code "259") (name "TMS") (class "Default")
      (node (ref "U_STM32F779") (pin "147") (pinfunction "PA13_147") (pintype "bidirectional"))
      (node (ref "X_PROG") (pin "7") (pinfunction "7_7") (pintype "passive"))
    )
    (net (code "260") (name "TRST") (class "Default")
      (node (ref "JP1") (pin "2") (pinfunction "2_2") (pintype "passive"))
      (node (ref "U_STM32F779") (pin "193") (pinfunction "PB4_193") (pintype "bidirectional"))
      (node (ref "X_PROG") (pin "3") (pinfunction "3_3") (pintype "passive"))
    )
    (net (code "261") (name "unconnected-(U_ADC_DMS1-AIN2{slash}IEXC{slash}GPIO2-Pad11)") (class "Default")
      (node (ref "U_ADC_DMS1") (pin "11") (pinfunction "AIN2/IEXC/GPIO2_11") (pintype "bidirectional"))
    )
    (net (code "262") (name "unconnected-(U_ADC_DMS1-AIN3{slash}IEXC{slash}GPIO3-Pad12)") (class "Default")
      (node (ref "U_ADC_DMS1") (pin "12") (pinfunction "AIN3/IEXC/GPIO3_12") (pintype "bidirectional"))
    )
    (net (code "263") (name "unconnected-(U_ADC_DMS1-REFN0{slash}GPIO1-Pad6)") (class "Default")
      (node (ref "U_ADC_DMS1") (pin "6") (pinfunction "REFN0/GPIO1_6") (pintype "bidirectional"))
    )
    (net (code "264") (name "unconnected-(U_ADC_DMS1-REFP0{slash}GPIO0-Pad5)") (class "Default")
      (node (ref "U_ADC_DMS1") (pin "5") (pinfunction "REFP0/GPIO0_5") (pintype "bidirectional"))
    )
    (net (code "265") (name "unconnected-(U_ADC_DMS2-AIN2{slash}IEXC{slash}GPIO2-Pad11)") (class "Default")
      (node (ref "U_ADC_DMS2") (pin "11") (pinfunction "AIN2/IEXC/GPIO2_11") (pintype "bidirectional"))
    )
    (net (code "266") (name "unconnected-(U_ADC_DMS2-AIN3{slash}IEXC{slash}GPIO3-Pad12)") (class "Default")
      (node (ref "U_ADC_DMS2") (pin "12") (pinfunction "AIN3/IEXC/GPIO3_12") (pintype "bidirectional"))
    )
    (net (code "267") (name "unconnected-(U_ADC_DMS2-REFN0{slash}GPIO1-Pad6)") (class "Default")
      (node (ref "U_ADC_DMS2") (pin "6") (pinfunction "REFN0/GPIO1_6") (pintype "bidirectional"))
    )
    (net (code "268") (name "unconnected-(U_ADC_DMS2-REFP0{slash}GPIO0-Pad5)") (class "Default")
      (node (ref "U_ADC_DMS2") (pin "5") (pinfunction "REFP0/GPIO0_5") (pintype "bidirectional"))
    )
    (net (code "269") (name "unconnected-(U_ADC_DMS3-AIN2{slash}IEXC{slash}GPIO2-Pad11)") (class "Default")
      (node (ref "U_ADC_DMS3") (pin "11") (pinfunction "AIN2/IEXC/GPIO2_11") (pintype "bidirectional"))
    )
    (net (code "270") (name "unconnected-(U_ADC_DMS3-AIN3{slash}IEXC{slash}GPIO3-Pad12)") (class "Default")
      (node (ref "U_ADC_DMS3") (pin "12") (pinfunction "AIN3/IEXC/GPIO3_12") (pintype "bidirectional"))
    )
    (net (code "271") (name "unconnected-(U_ADC_DMS3-REFN0{slash}GPIO1-Pad6)") (class "Default")
      (node (ref "U_ADC_DMS3") (pin "6") (pinfunction "REFN0/GPIO1_6") (pintype "bidirectional"))
    )
    (net (code "272") (name "unconnected-(U_ADC_DMS3-REFP0{slash}GPIO0-Pad5)") (class "Default")
      (node (ref "U_ADC_DMS3") (pin "5") (pinfunction "REFP0/GPIO0_5") (pintype "bidirectional"))
    )
    (net (code "273") (name "unconnected-(U_ADC_DMS4-AIN2{slash}IEXC{slash}GPIO2-Pad11)") (class "Default")
      (node (ref "U_ADC_DMS4") (pin "11") (pinfunction "AIN2/IEXC/GPIO2_11") (pintype "bidirectional"))
    )
    (net (code "274") (name "unconnected-(U_ADC_DMS4-AIN3{slash}IEXC{slash}GPIO3-Pad12)") (class "Default")
      (node (ref "U_ADC_DMS4") (pin "12") (pinfunction "AIN3/IEXC/GPIO3_12") (pintype "bidirectional"))
    )
    (net (code "275") (name "unconnected-(U_ADC_DMS4-REFN0{slash}GPIO1-Pad6)") (class "Default")
      (node (ref "U_ADC_DMS4") (pin "6") (pinfunction "REFN0/GPIO1_6") (pintype "bidirectional"))
    )
    (net (code "276") (name "unconnected-(U_ADC_DMS4-REFP0{slash}GPIO0-Pad5)") (class "Default")
      (node (ref "U_ADC_DMS4") (pin "5") (pinfunction "REFP0/GPIO0_5") (pintype "bidirectional"))
    )
    (net (code "277") (name "unconnected-(U_ADC_DMS5-AIN2{slash}IEXC{slash}GPIO2-Pad11)") (class "Default")
      (node (ref "U_ADC_DMS5") (pin "11") (pinfunction "AIN2/IEXC/GPIO2_11") (pintype "bidirectional"))
    )
    (net (code "278") (name "unconnected-(U_ADC_DMS5-AIN3{slash}IEXC{slash}GPIO3-Pad12)") (class "Default")
      (node (ref "U_ADC_DMS5") (pin "12") (pinfunction "AIN3/IEXC/GPIO3_12") (pintype "bidirectional"))
    )
    (net (code "279") (name "unconnected-(U_ADC_DMS5-REFN0{slash}GPIO1-Pad6)") (class "Default")
      (node (ref "U_ADC_DMS5") (pin "6") (pinfunction "REFN0/GPIO1_6") (pintype "bidirectional"))
    )
    (net (code "280") (name "unconnected-(U_ADC_DMS5-REFP0{slash}GPIO0-Pad5)") (class "Default")
      (node (ref "U_ADC_DMS5") (pin "5") (pinfunction "REFP0/GPIO0_5") (pintype "bidirectional"))
    )
    (net (code "281") (name "unconnected-(U_ADC_DMS6-AIN2{slash}IEXC{slash}GPIO2-Pad11)") (class "Default")
      (node (ref "U_ADC_DMS6") (pin "11") (pinfunction "AIN2/IEXC/GPIO2_11") (pintype "bidirectional"))
    )
    (net (code "282") (name "unconnected-(U_ADC_DMS6-AIN3{slash}IEXC{slash}GPIO3-Pad12)") (class "Default")
      (node (ref "U_ADC_DMS6") (pin "12") (pinfunction "AIN3/IEXC/GPIO3_12") (pintype "bidirectional"))
    )
    (net (code "283") (name "unconnected-(U_ADC_DMS6-REFN0{slash}GPIO1-Pad6)") (class "Default")
      (node (ref "U_ADC_DMS6") (pin "6") (pinfunction "REFN0/GPIO1_6") (pintype "bidirectional"))
    )
    (net (code "284") (name "unconnected-(U_ADC_DMS6-REFP0{slash}GPIO0-Pad5)") (class "Default")
      (node (ref "U_ADC_DMS6") (pin "5") (pinfunction "REFP0/GPIO0_5") (pintype "bidirectional"))
    )
    (net (code "285") (name "unconnected-(U_CH340G-CTS-Pad9)") (class "Default")
      (node (ref "U_CH340G") (pin "9") (pinfunction "CTS_9") (pintype "bidirectional"))
    )
    (net (code "286") (name "unconnected-(U_CH340G-DCD-Pad12)") (class "Default")
      (node (ref "U_CH340G") (pin "12") (pinfunction "DCD_12") (pintype "bidirectional"))
    )
    (net (code "287") (name "unconnected-(U_CH340G-DSR-Pad10)") (class "Default")
      (node (ref "U_CH340G") (pin "10") (pinfunction "DSR_10") (pintype "bidirectional"))
    )
    (net (code "288") (name "unconnected-(U_CH340G-DTR-Pad13)") (class "Default")
      (node (ref "U_CH340G") (pin "13") (pinfunction "DTR_13") (pintype "bidirectional"))
    )
    (net (code "289") (name "unconnected-(U_CH340G-RI-Pad11)") (class "Default")
      (node (ref "U_CH340G") (pin "11") (pinfunction "RI_11") (pintype "bidirectional"))
    )
    (net (code "290") (name "unconnected-(U_CH340G-RS232-Pad15)") (class "Default")
      (node (ref "U_CH340G") (pin "15") (pinfunction "RS232_15") (pintype "bidirectional"))
    )
    (net (code "291") (name "unconnected-(U_CH340G-RTS-Pad14)") (class "Default")
      (node (ref "U_CH340G") (pin "14") (pinfunction "RTS_14") (pintype "bidirectional"))
    )
    (net (code "292") (name "unconnected-(U_CH340G-V3-Pad4)") (class "Default")
      (node (ref "U_CH340G") (pin "4") (pinfunction "V3_4") (pintype "bidirectional"))
    )
    (net (code "293") (name "unconnected-(U_OPTO_2-C2-Pad4)") (class "Default")
      (node (ref "U_OPTO_2") (pin "4") (pinfunction "C2_4") (pintype "bidirectional"))
    )
    (net (code "294") (name "unconnected-(U_STM32F779-DSI_CKN-Pad124)") (class "Default")
      (node (ref "U_STM32F779") (pin "124") (pinfunction "DSI_CKN_124") (pintype "bidirectional"))
    )
    (net (code "295") (name "unconnected-(U_STM32F779-DSI_CKP-Pad123)") (class "Default")
      (node (ref "U_STM32F779") (pin "123") (pinfunction "DSI_CKP_123") (pintype "bidirectional"))
    )
    (net (code "296") (name "unconnected-(U_STM32F779-DSI_D0N-Pad121)") (class "Default")
      (node (ref "U_STM32F779") (pin "121") (pinfunction "DSI_D0N_121") (pintype "bidirectional"))
    )
    (net (code "297") (name "unconnected-(U_STM32F779-DSI_D0P-Pad120)") (class "Default")
      (node (ref "U_STM32F779") (pin "120") (pinfunction "DSI_D0P_120") (pintype "bidirectional"))
    )
    (net (code "298") (name "unconnected-(U_STM32F779-DSI_D1N-Pad127)") (class "Default")
      (node (ref "U_STM32F779") (pin "127") (pinfunction "DSI_D1N_127") (pintype "bidirectional"))
    )
    (net (code "299") (name "unconnected-(U_STM32F779-DSI_D1P-Pad126)") (class "Default")
      (node (ref "U_STM32F779") (pin "126") (pinfunction "DSI_D1P_126") (pintype "bidirectional"))
    )
    (net (code "300") (name "unconnected-(U_STM32F779-PA8-Pad142)") (class "Default")
      (node (ref "U_STM32F779") (pin "142") (pinfunction "PA8_142") (pintype "bidirectional"))
    )
    (net (code "301") (name "unconnected-(U_STM32F779-PA9-Pad143)") (class "Default")
      (node (ref "U_STM32F779") (pin "143") (pinfunction "PA9_143") (pintype "bidirectional"))
    )
    (net (code "302") (name "unconnected-(U_STM32F779-PA10-Pad144)") (class "Default")
      (node (ref "U_STM32F779") (pin "144") (pinfunction "PA10_144") (pintype "bidirectional"))
    )
    (net (code "303") (name "unconnected-(U_STM32F779-PA11-Pad145)") (class "Default")
      (node (ref "U_STM32F779") (pin "145") (pinfunction "PA11_145") (pintype "bidirectional"))
    )
    (net (code "304") (name "unconnected-(U_STM32F779-PA12-Pad146)") (class "Default")
      (node (ref "U_STM32F779") (pin "146") (pinfunction "PA12_146") (pintype "bidirectional"))
    )
    (net (code "305") (name "unconnected-(U_STM32F779-PB5-Pad194)") (class "Default")
      (node (ref "U_STM32F779") (pin "194") (pinfunction "PB5_194") (pintype "bidirectional"))
    )
    (net (code "306") (name "unconnected-(U_STM32F779-PB6-Pad195)") (class "Default")
      (node (ref "U_STM32F779") (pin "195") (pinfunction "PB6_195") (pintype "bidirectional"))
    )
    (net (code "307") (name "unconnected-(U_STM32F779-PB7-Pad196)") (class "Default")
      (node (ref "U_STM32F779") (pin "196") (pinfunction "PB7_196") (pintype "bidirectional"))
    )
    (net (code "308") (name "unconnected-(U_STM32F779-PB8-Pad198)") (class "Default")
      (node (ref "U_STM32F779") (pin "198") (pinfunction "PB8_198") (pintype "bidirectional"))
    )
    (net (code "309") (name "unconnected-(U_STM32F779-PB9-Pad199)") (class "Default")
      (node (ref "U_STM32F779") (pin "199") (pinfunction "PB9_199") (pintype "bidirectional"))
    )
    (net (code "310") (name "unconnected-(U_STM32F779-PB10-Pad90)") (class "Default")
      (node (ref "U_STM32F779") (pin "90") (pinfunction "PB10_90") (pintype "bidirectional"))
    )
    (net (code "311") (name "unconnected-(U_STM32F779-PB11-Pad91)") (class "Default")
      (node (ref "U_STM32F779") (pin "91") (pinfunction "PB11_91") (pintype "bidirectional"))
    )
    (net (code "312") (name "unconnected-(U_STM32F779-PC1-Pad36)") (class "Default")
      (node (ref "U_STM32F779") (pin "36") (pinfunction "PC1_36") (pintype "bidirectional"))
    )
    (net (code "313") (name "unconnected-(U_STM32F779-PC4-Pad57)") (class "Default")
      (node (ref "U_STM32F779") (pin "57") (pinfunction "PC4_57") (pintype "bidirectional"))
    )
    (net (code "314") (name "unconnected-(U_STM32F779-PC5-Pad58)") (class "Default")
      (node (ref "U_STM32F779") (pin "58") (pinfunction "PC5_58") (pintype "bidirectional"))
    )
    (net (code "315") (name "unconnected-(U_STM32F779-PC6-Pad138)") (class "Default")
      (node (ref "U_STM32F779") (pin "138") (pinfunction "PC6_138") (pintype "bidirectional"))
    )
    (net (code "316") (name "unconnected-(U_STM32F779-PC7-Pad139)") (class "Default")
      (node (ref "U_STM32F779") (pin "139") (pinfunction "PC7_139") (pintype "bidirectional"))
    )
    (net (code "317") (name "unconnected-(U_STM32F779-PC8-Pad140)") (class "Default")
      (node (ref "U_STM32F779") (pin "140") (pinfunction "PC8_140") (pintype "bidirectional"))
    )
    (net (code "318") (name "unconnected-(U_STM32F779-PC9-Pad141)") (class "Default")
      (node (ref "U_STM32F779") (pin "141") (pinfunction "PC9_141") (pintype "bidirectional"))
    )
    (net (code "319") (name "unconnected-(U_STM32F779-PC13-Pad8)") (class "Default")
      (node (ref "U_STM32F779") (pin "8") (pinfunction "PC13_8") (pintype "bidirectional"))
    )
    (net (code "320") (name "unconnected-(U_STM32F779-PC14-Pad9)") (class "Default")
      (node (ref "U_STM32F779") (pin "9") (pinfunction "PC14_9") (pintype "bidirectional"))
    )
    (net (code "321") (name "unconnected-(U_STM32F779-PC15-Pad10)") (class "Default")
      (node (ref "U_STM32F779") (pin "10") (pinfunction "PC15_10") (pintype "bidirectional"))
    )
    (net (code "322") (name "unconnected-(U_STM32F779-PD0-Pad164)") (class "Default")
      (node (ref "U_STM32F779") (pin "164") (pinfunction "PD0_164") (pintype "bidirectional"))
    )
    (net (code "323") (name "unconnected-(U_STM32F779-PD1-Pad165)") (class "Default")
      (node (ref "U_STM32F779") (pin "165") (pinfunction "PD1_165") (pintype "bidirectional"))
    )
    (net (code "324") (name "unconnected-(U_STM32F779-PD3-Pad167)") (class "Default")
      (node (ref "U_STM32F779") (pin "167") (pinfunction "PD3_167") (pintype "bidirectional"))
    )
    (net (code "325") (name "unconnected-(U_STM32F779-PD4-Pad168)") (class "Default")
      (node (ref "U_STM32F779") (pin "168") (pinfunction "PD4_168") (pintype "bidirectional"))
    )
    (net (code "326") (name "unconnected-(U_STM32F779-PD5-Pad169)") (class "Default")
      (node (ref "U_STM32F779") (pin "169") (pinfunction "PD5_169") (pintype "bidirectional"))
    )
    (net (code "327") (name "unconnected-(U_STM32F779-PD6-Pad172)") (class "Default")
      (node (ref "U_STM32F779") (pin "172") (pinfunction "PD6_172") (pintype "bidirectional"))
    )
    (net (code "328") (name "unconnected-(U_STM32F779-PD7-Pad173)") (class "Default")
      (node (ref "U_STM32F779") (pin "173") (pinfunction "PD7_173") (pintype "bidirectional"))
    )
    (net (code "329") (name "unconnected-(U_STM32F779-PD13-Pad113)") (class "Default")
      (node (ref "U_STM32F779") (pin "113") (pinfunction "PD13_113") (pintype "bidirectional"))
    )
    (net (code "330") (name "unconnected-(U_STM32F779-PD14-Pad116)") (class "Default")
      (node (ref "U_STM32F779") (pin "116") (pinfunction "PD14_116") (pintype "bidirectional"))
    )
    (net (code "331") (name "unconnected-(U_STM32F779-PD15-Pad117)") (class "Default")
      (node (ref "U_STM32F779") (pin "117") (pinfunction "PD15_117") (pintype "bidirectional"))
    )
    (net (code "332") (name "unconnected-(U_STM32F779-PE3-Pad2)") (class "Default")
      (node (ref "U_STM32F779") (pin "2") (pinfunction "PE3_2") (pintype "bidirectional"))
    )
    (net (code "333") (name "unconnected-(U_STM32F779-PE4-Pad3)") (class "Default")
      (node (ref "U_STM32F779") (pin "3") (pinfunction "PE4_3") (pintype "bidirectional"))
    )
    (net (code "334") (name "unconnected-(U_STM32F779-PE7-Pad79)") (class "Default")
      (node (ref "U_STM32F779") (pin "79") (pinfunction "PE7_79") (pintype "bidirectional"))
    )
    (net (code "335") (name "unconnected-(U_STM32F779-PE8-Pad80)") (class "Default")
      (node (ref "U_STM32F779") (pin "80") (pinfunction "PE8_80") (pintype "bidirectional"))
    )
    (net (code "336") (name "unconnected-(U_STM32F779-PE9-Pad81)") (class "Default")
      (node (ref "U_STM32F779") (pin "81") (pinfunction "PE9_81") (pintype "bidirectional"))
    )
    (net (code "337") (name "unconnected-(U_STM32F779-PE10-Pad84)") (class "Default")
      (node (ref "U_STM32F779") (pin "84") (pinfunction "PE10_84") (pintype "bidirectional"))
    )
    (net (code "338") (name "unconnected-(U_STM32F779-PE11-Pad85)") (class "Default")
      (node (ref "U_STM32F779") (pin "85") (pinfunction "PE11_85") (pintype "bidirectional"))
    )
    (net (code "339") (name "unconnected-(U_STM32F779-PE12-Pad86)") (class "Default")
      (node (ref "U_STM32F779") (pin "86") (pinfunction "PE12_86") (pintype "bidirectional"))
    )
    (net (code "340") (name "unconnected-(U_STM32F779-PE13-Pad87)") (class "Default")
      (node (ref "U_STM32F779") (pin "87") (pinfunction "PE13_87") (pintype "bidirectional"))
    )
    (net (code "341") (name "unconnected-(U_STM32F779-PE14-Pad88)") (class "Default")
      (node (ref "U_STM32F779") (pin "88") (pinfunction "PE14_88") (pintype "bidirectional"))
    )
    (net (code "342") (name "unconnected-(U_STM32F779-PE15-Pad89)") (class "Default")
      (node (ref "U_STM32F779") (pin "89") (pinfunction "PE15_89") (pintype "bidirectional"))
    )
    (net (code "343") (name "unconnected-(U_STM32F779-PF0-Pad16)") (class "Default")
      (node (ref "U_STM32F779") (pin "16") (pinfunction "PF0_16") (pintype "bidirectional"))
    )
    (net (code "344") (name "unconnected-(U_STM32F779-PF1-Pad17)") (class "Default")
      (node (ref "U_STM32F779") (pin "17") (pinfunction "PF1_17") (pintype "bidirectional"))
    )
    (net (code "345") (name "unconnected-(U_STM32F779-PF6-Pad27)") (class "Default")
      (node (ref "U_STM32F779") (pin "27") (pinfunction "PF6_27") (pintype "bidirectional"))
    )
    (net (code "346") (name "unconnected-(U_STM32F779-PG0-Pad77)") (class "Default")
      (node (ref "U_STM32F779") (pin "77") (pinfunction "PG0_77") (pintype "bidirectional"))
    )
    (net (code "347") (name "unconnected-(U_STM32F779-PG1-Pad78)") (class "Default")
      (node (ref "U_STM32F779") (pin "78") (pinfunction "PG1_78") (pintype "bidirectional"))
    )
    (net (code "348") (name "unconnected-(U_STM32F779-PG3-Pad130)") (class "Default")
      (node (ref "U_STM32F779") (pin "130") (pinfunction "PG3_130") (pintype "bidirectional"))
    )
    (net (code "349") (name "unconnected-(U_STM32F779-PG4-Pad131)") (class "Default")
      (node (ref "U_STM32F779") (pin "131") (pinfunction "PG4_131") (pintype "bidirectional"))
    )
    (net (code "350") (name "unconnected-(U_STM32F779-PG5-Pad132)") (class "Default")
      (node (ref "U_STM32F779") (pin "132") (pinfunction "PG5_132") (pintype "bidirectional"))
    )
    (net (code "351") (name "unconnected-(U_STM32F779-PG6-Pad133)") (class "Default")
      (node (ref "U_STM32F779") (pin "133") (pinfunction "PG6_133") (pintype "bidirectional"))
    )
    (net (code "352") (name "unconnected-(U_STM32F779-PG7-Pad134)") (class "Default")
      (node (ref "U_STM32F779") (pin "134") (pinfunction "PG7_134") (pintype "bidirectional"))
    )
    (net (code "353") (name "unconnected-(U_STM32F779-PG8-Pad135)") (class "Default")
      (node (ref "U_STM32F779") (pin "135") (pinfunction "PG8_135") (pintype "bidirectional"))
    )
    (net (code "354") (name "unconnected-(U_STM32F779-PG9-Pad178)") (class "Default")
      (node (ref "U_STM32F779") (pin "178") (pinfunction "PG9_178") (pintype "bidirectional"))
    )
    (net (code "355") (name "unconnected-(U_STM32F779-PG10-Pad179)") (class "Default")
      (node (ref "U_STM32F779") (pin "179") (pinfunction "PG10_179") (pintype "bidirectional"))
    )
    (net (code "356") (name "unconnected-(U_STM32F779-PG11-Pad180)") (class "Default")
      (node (ref "U_STM32F779") (pin "180") (pinfunction "PG11_180") (pintype "bidirectional"))
    )
    (net (code "357") (name "unconnected-(U_STM32F779-PG12-Pad181)") (class "Default")
      (node (ref "U_STM32F779") (pin "181") (pinfunction "PG12_181") (pintype "bidirectional"))
    )
    (net (code "358") (name "unconnected-(U_STM32F779-PG13-Pad182)") (class "Default")
      (node (ref "U_STM32F779") (pin "182") (pinfunction "PG13_182") (pintype "bidirectional"))
    )
    (net (code "359") (name "unconnected-(U_STM32F779-PG14-Pad183)") (class "Default")
      (node (ref "U_STM32F779") (pin "183") (pinfunction "PG14_183") (pintype "bidirectional"))
    )
    (net (code "360") (name "unconnected-(U_STM32F779-PG15-Pad191)") (class "Default")
      (node (ref "U_STM32F779") (pin "191") (pinfunction "PG15_191") (pintype "bidirectional"))
    )
    (net (code "361") (name "unconnected-(U_STM32F779-PH2-Pad46)") (class "Default")
      (node (ref "U_STM32F779") (pin "46") (pinfunction "PH2_46") (pintype "bidirectional"))
    )
    (net (code "362") (name "unconnected-(U_STM32F779-PH6-Pad96)") (class "Default")
      (node (ref "U_STM32F779") (pin "96") (pinfunction "PH6_96") (pintype "bidirectional"))
    )
    (net (code "363") (name "unconnected-(U_STM32F779-PH7-Pad97)") (class "Default")
      (node (ref "U_STM32F779") (pin "97") (pinfunction "PH7_97") (pintype "bidirectional"))
    )
    (net (code "364") (name "unconnected-(U_STM32F779-PH8-Pad98)") (class "Default")
      (node (ref "U_STM32F779") (pin "98") (pinfunction "PH8_98") (pintype "bidirectional"))
    )
    (net (code "365") (name "unconnected-(U_STM32F779-PH13-Pad151)") (class "Default")
      (node (ref "U_STM32F779") (pin "151") (pinfunction "PH13_151") (pintype "bidirectional"))
    )
    (net (code "366") (name "unconnected-(U_STM32F779-PH14-Pad152)") (class "Default")
      (node (ref "U_STM32F779") (pin "152") (pinfunction "PH14_152") (pintype "bidirectional"))
    )
    (net (code "367") (name "unconnected-(U_STM32F779-PH15-Pad153)") (class "Default")
      (node (ref "U_STM32F779") (pin "153") (pinfunction "PH15_153") (pintype "bidirectional"))
    )
    (net (code "368") (name "unconnected-(U_STM32F779-PI0-Pad154)") (class "Default")
      (node (ref "U_STM32F779") (pin "154") (pinfunction "PI0_154") (pintype "bidirectional"))
    )
    (net (code "369") (name "unconnected-(U_STM32F779-PI1-Pad155)") (class "Default")
      (node (ref "U_STM32F779") (pin "155") (pinfunction "PI1_155") (pintype "bidirectional"))
    )
    (net (code "370") (name "unconnected-(U_STM32F779-PI2-Pad156)") (class "Default")
      (node (ref "U_STM32F779") (pin "156") (pinfunction "PI2_156") (pintype "bidirectional"))
    )
    (net (code "371") (name "unconnected-(U_STM32F779-PI3-Pad157)") (class "Default")
      (node (ref "U_STM32F779") (pin "157") (pinfunction "PI3_157") (pintype "bidirectional"))
    )
    (net (code "372") (name "unconnected-(U_STM32F779-PI4-Pad205)") (class "Default")
      (node (ref "U_STM32F779") (pin "205") (pinfunction "PI4_205") (pintype "bidirectional"))
    )
    (net (code "373") (name "unconnected-(U_STM32F779-PI8-Pad7)") (class "Default")
      (node (ref "U_STM32F779") (pin "7") (pinfunction "PI8_7") (pintype "bidirectional"))
    )
    (net (code "374") (name "unconnected-(U_STM32F779-PI10-Pad12)") (class "Default")
      (node (ref "U_STM32F779") (pin "12") (pinfunction "PI10_12") (pintype "bidirectional"))
    )
    (net (code "375") (name "unconnected-(U_STM32F779-PI11-Pad13)") (class "Default")
      (node (ref "U_STM32F779") (pin "13") (pinfunction "PI11_13") (pintype "bidirectional"))
    )
    (net (code "376") (name "unconnected-(U_STM32F779-PI15-Pad64)") (class "Default")
      (node (ref "U_STM32F779") (pin "64") (pinfunction "PI15_64") (pintype "bidirectional"))
    )
    (net (code "377") (name "unconnected-(U_STM32F779-PJ4-Pad69)") (class "Default")
      (node (ref "U_STM32F779") (pin "69") (pinfunction "PJ4_69") (pintype "bidirectional"))
    )
    (net (code "378") (name "unconnected-(U_STM32F779-PJ5-Pad95)") (class "Default")
      (node (ref "U_STM32F779") (pin "95") (pinfunction "PJ5_95") (pintype "bidirectional"))
    )
    (net (code "379") (name "unconnected-(U_STM32F779-PJ12-Pad174)") (class "Default")
      (node (ref "U_STM32F779") (pin "174") (pinfunction "PJ12_174") (pintype "bidirectional"))
    )
    (net (code "380") (name "unconnected-(U_STM32F779-PJ13-Pad175)") (class "Default")
      (node (ref "U_STM32F779") (pin "175") (pinfunction "PJ13_175") (pintype "bidirectional"))
    )
    (net (code "381") (name "unconnected-(U_STM32F779-PJ14-Pad176)") (class "Default")
      (node (ref "U_STM32F779") (pin "176") (pinfunction "PJ14_176") (pintype "bidirectional"))
    )
    (net (code "382") (name "unconnected-(U_STM32F779-PJ15-Pad177)") (class "Default")
      (node (ref "U_STM32F779") (pin "177") (pinfunction "PJ15_177") (pintype "bidirectional"))
    )
    (net (code "383") (name "unconnected-(U_STM32F779-PK3-Pad186)") (class "Default")
      (node (ref "U_STM32F779") (pin "186") (pinfunction "PK3_186") (pintype "bidirectional"))
    )
    (net (code "384") (name "unconnected-(U_STM32F779-PK4-Pad187)") (class "Default")
      (node (ref "U_STM32F779") (pin "187") (pinfunction "PK4_187") (pintype "bidirectional"))
    )
    (net (code "385") (name "unconnected-(U_STM32F779-PK5-Pad188)") (class "Default")
      (node (ref "U_STM32F779") (pin "188") (pinfunction "PK5_188") (pintype "bidirectional"))
    )
    (net (code "386") (name "unconnected-(U_STM32F779-PK6-Pad189)") (class "Default")
      (node (ref "U_STM32F779") (pin "189") (pinfunction "PK6_189") (pintype "bidirectional"))
    )
    (net (code "387") (name "unconnected-(U_STM32F779-PK7-Pad190)") (class "Default")
      (node (ref "U_STM32F779") (pin "190") (pinfunction "PK7_190") (pintype "bidirectional"))
    )
    (net (code "388") (name "unconnected-(U_TRACODCDC-RMT_ON_OFF-Pad6)") (class "Default")
      (node (ref "U_TRACODCDC") (pin "6") (pinfunction "RMT_ON_OFF_6") (pintype "input"))
    )
    (net (code "389") (name "unconnected-(U_TRACODCDC-TRIM-Pad4)") (class "Default")
      (node (ref "U_TRACODCDC") (pin "4") (pinfunction "TRIM_4") (pintype "input"))
    )
    (net (code "390") (name "unconnected-(X1-A10-PadP$A10)") (class "Default")
      (node (ref "X1") (pin "P$A10") (pinfunction "A10_P$A10") (pintype "passive"))
    )
    (net (code "391") (name "unconnected-(X1-B10-PadP$B10)") (class "Default")
      (node (ref "X1") (pin "P$B10") (pinfunction "B10_P$B10") (pintype "passive"))
    )
    (net (code "392") (name "unconnected-(X_MIRROR-A11-PadP$A11)") (class "Default")
      (node (ref "X_MIRROR") (pin "P$A11") (pinfunction "A11_P$A11") (pintype "passive"))
    )
    (net (code "393") (name "unconnected-(X_MIRROR-A12-PadP$A12)") (class "Default")
      (node (ref "X_MIRROR") (pin "P$A12") (pinfunction "A12_P$A12") (pintype "passive"))
    )
    (net (code "394") (name "unconnected-(X_MIRROR-A13-PadP$A13)") (class "Default")
      (node (ref "X_MIRROR") (pin "P$A13") (pinfunction "A13_P$A13") (pintype "passive"))
    )
    (net (code "395") (name "unconnected-(X_MIRROR1-A1-PadP$A1)") (class "Default")
      (node (ref "X_MIRROR1") (pin "P$A1") (pinfunction "A1_P$A1") (pintype "passive"))
    )
    (net (code "396") (name "unconnected-(X_MIRROR1-A2-PadP$A2)") (class "Default")
      (node (ref "X_MIRROR1") (pin "P$A2") (pinfunction "A2_P$A2") (pintype "passive"))
    )
    (net (code "397") (name "unconnected-(X_MIRROR1-A3-PadP$A3)") (class "Default")
      (node (ref "X_MIRROR1") (pin "P$A3") (pinfunction "A3_P$A3") (pintype "passive"))
    )
    (net (code "398") (name "unconnected-(X_PROG-Pad2)") (class "Default")
      (node (ref "X_PROG") (pin "2") (pinfunction "2_2") (pintype "passive"))
    )
    (net (code "399") (name "unconnected-(X_PROG-Pad11)") (class "Default")
      (node (ref "X_PROG") (pin "11") (pinfunction "11_11") (pintype "passive"))
    )
    (net (code "400") (name "unconnected-(X_PROG-Pad17)") (class "Default")
      (node (ref "X_PROG") (pin "17") (pinfunction "17_17") (pintype "passive"))
    )
    (net (code "401") (name "unconnected-(X_PROG-Pad19)") (class "Default")
      (node (ref "X_PROG") (pin "19") (pinfunction "19_19") (pintype "passive"))
    )
    (net (code "402") (name "unconnected-(X_PT-A4-PadP$A4)") (class "Default")
      (node (ref "X_PT") (pin "P$A4") (pinfunction "A4_P$A4") (pintype "passive"))
    )
    (net (code "403") (name "unconnected-(X_PT-A5-PadP$A5)") (class "Default")
      (node (ref "X_PT") (pin "P$A5") (pinfunction "A5_P$A5") (pintype "passive"))
    )
    (net (code "404") (name "unconnected-(X_PT-A6-PadP$A6)") (class "Default")
      (node (ref "X_PT") (pin "P$A6") (pinfunction "A6_P$A6") (pintype "passive"))
    )
    (net (code "405") (name "unconnected-(X_RXSM-DAPI-A7-PadP$A7)") (class "Default")
      (node (ref "X_RXSM-DAPI") (pin "P$A7") (pinfunction "A7_P$A7") (pintype "passive"))
    )
    (net (code "406") (name "unconnected-(X_RXSM-DAPI-A8-PadP$A8)") (class "Default")
      (node (ref "X_RXSM-DAPI") (pin "P$A8") (pinfunction "A8_P$A8") (pintype "passive"))
    )
    (net (code "407") (name "unconnected-(X_RXSM-DAPI-B7-PadP$B7)") (class "Default")
      (node (ref "X_RXSM-DAPI") (pin "P$B7") (pinfunction "B7_P$B7") (pintype "passive"))
    )
    (net (code "408") (name "unconnected-(X_RXSM-DAPI-B8-PadP$B8)") (class "Default")
      (node (ref "X_RXSM-DAPI") (pin "P$B8") (pinfunction "B8_P$B8") (pintype "passive"))
    )
    (net (code "409") (name "~{CS}_DMS1") (class "Default")
      (node (ref "R3") (pin "2") (pinfunction "2_2") (pintype "passive"))
    )
    (net (code "410") (name "~{CS}_DMS2") (class "Default")
      (node (ref "R31") (pin "2") (pinfunction "2_2") (pintype "passive"))
    )
    (net (code "411") (name "~{CS}_DMS3") (class "Default")
      (node (ref "R38") (pin "2") (pinfunction "2_2") (pintype "passive"))
    )
    (net (code "412") (name "~{CS}_DMS4") (class "Default")
      (node (ref "R45") (pin "2") (pinfunction "2_2") (pintype "passive"))
    )
    (net (code "413") (name "~{CS}_DMS5") (class "Default")
      (node (ref "R52") (pin "2") (pinfunction "2_2") (pintype "passive"))
    )
    (net (code "414") (name "~{CS}_DMS6") (class "Default")
      (node (ref "R59") (pin "2") (pinfunction "2_2") (pintype "passive"))
    )
    (net (code "415") (name "~{CS}_PT1") (class "Default")
      (node (ref "RN_B_PT1") (pin "7") (pinfunction "2_7") (pintype "passive"))
    )
    (net (code "416") (name "~{CS}_PT2") (class "Default")
      (node (ref "RN_B_PT2") (pin "7") (pinfunction "2_7") (pintype "passive"))
    )
    (net (code "417") (name "~{CS}_PT3") (class "Default")
      (node (ref "RN_B_PT3") (pin "7") (pinfunction "2_7") (pintype "passive"))
    )
    (net (code "418") (name "~{DRDY}_DMS1") (class "Default")
      (node (ref "RN_DMS1") (pin "5") (pinfunction "2_5") (pintype "passive"))
    )
    (net (code "419") (name "~{DRDY}_DMS2") (class "Default")
      (node (ref "RN_DMS2") (pin "5") (pinfunction "2_5") (pintype "passive"))
    )
    (net (code "420") (name "~{DRDY}_DMS3") (class "Default")
      (node (ref "RN_DMS3") (pin "5") (pinfunction "2_5") (pintype "passive"))
    )
    (net (code "421") (name "~{DRDY}_DMS4") (class "Default")
      (node (ref "RN_DMS4") (pin "5") (pinfunction "2_5") (pintype "passive"))
    )
    (net (code "422") (name "~{DRDY}_DMS5") (class "Default")
      (node (ref "RN_DMS5") (pin "5") (pinfunction "2_5") (pintype "passive"))
    )
    (net (code "423") (name "~{DRDY}_DMS6") (class "Default")
      (node (ref "RN_DMS6") (pin "5") (pinfunction "2_5") (pintype "passive"))
    )
    (net (code "424") (name "~{DRDY}_PT1") (class "Default")
      (node (ref "RN_B_PT1") (pin "8") (pinfunction "2_8") (pintype "passive"))
    )
    (net (code "425") (name "~{DRDY}_PT2") (class "Default")
      (node (ref "RN_B_PT2") (pin "8") (pinfunction "2_8") (pintype "passive"))
    )
    (net (code "426") (name "~{DRDY}_PT3") (class "Default")
      (node (ref "RN_B_PT3") (pin "8") (pinfunction "2_8") (pintype "passive"))
    )
  )
)
